# pcie-host.net
KiCad netlist of a schematic drawn in EAGLE
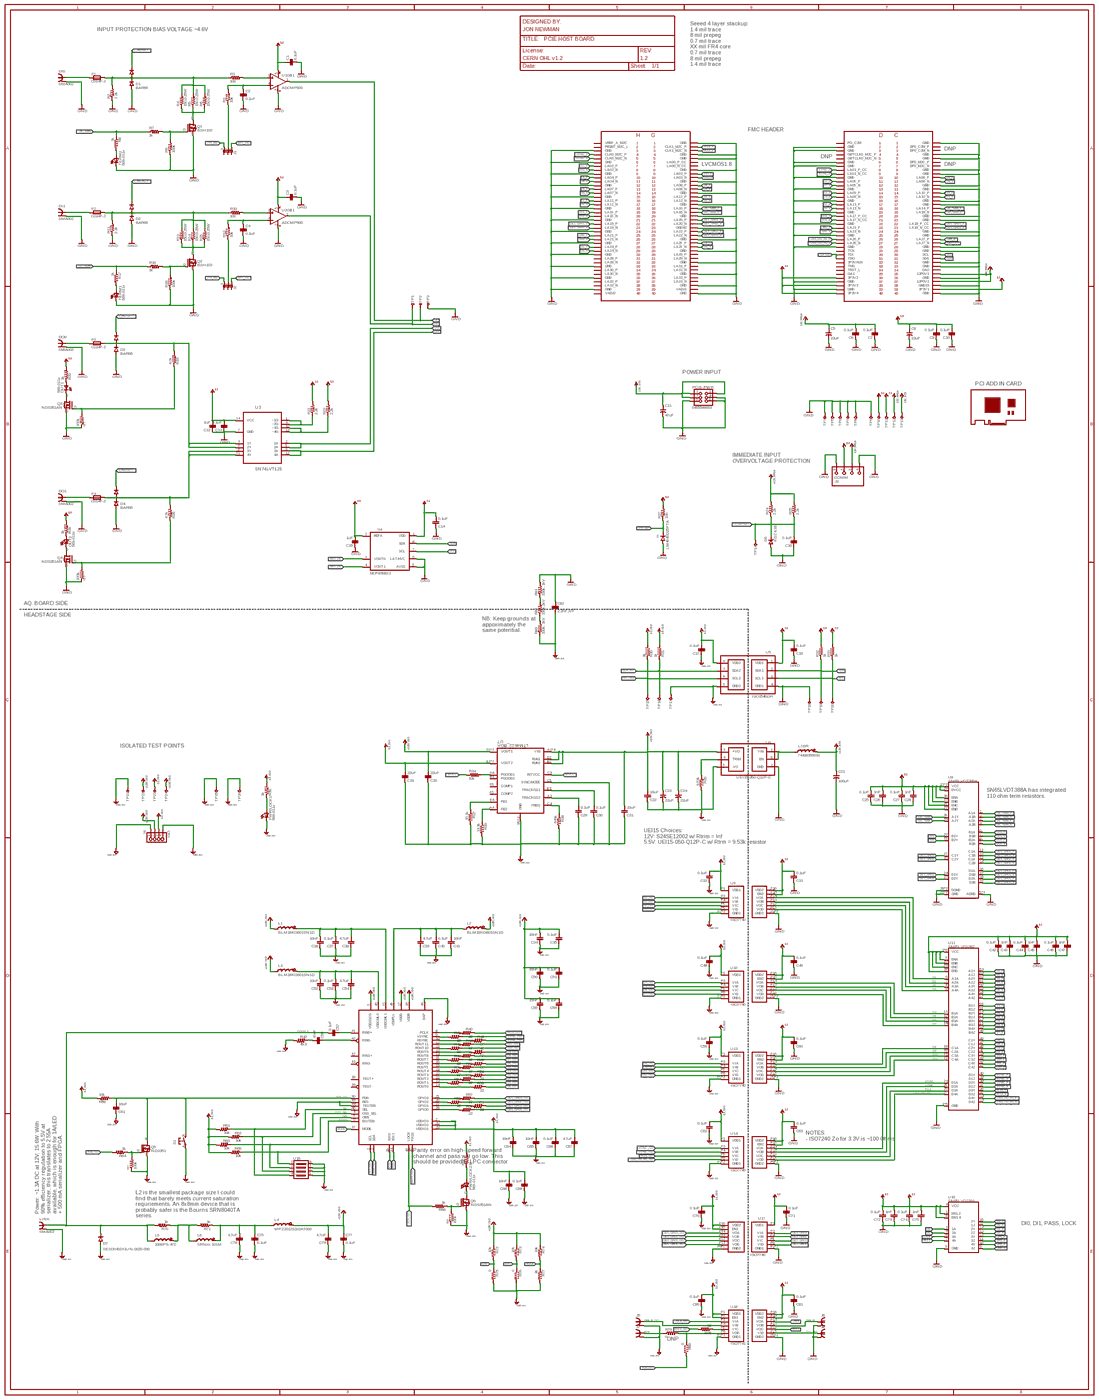
[diagram p0: schematic, sheet 1, overview]
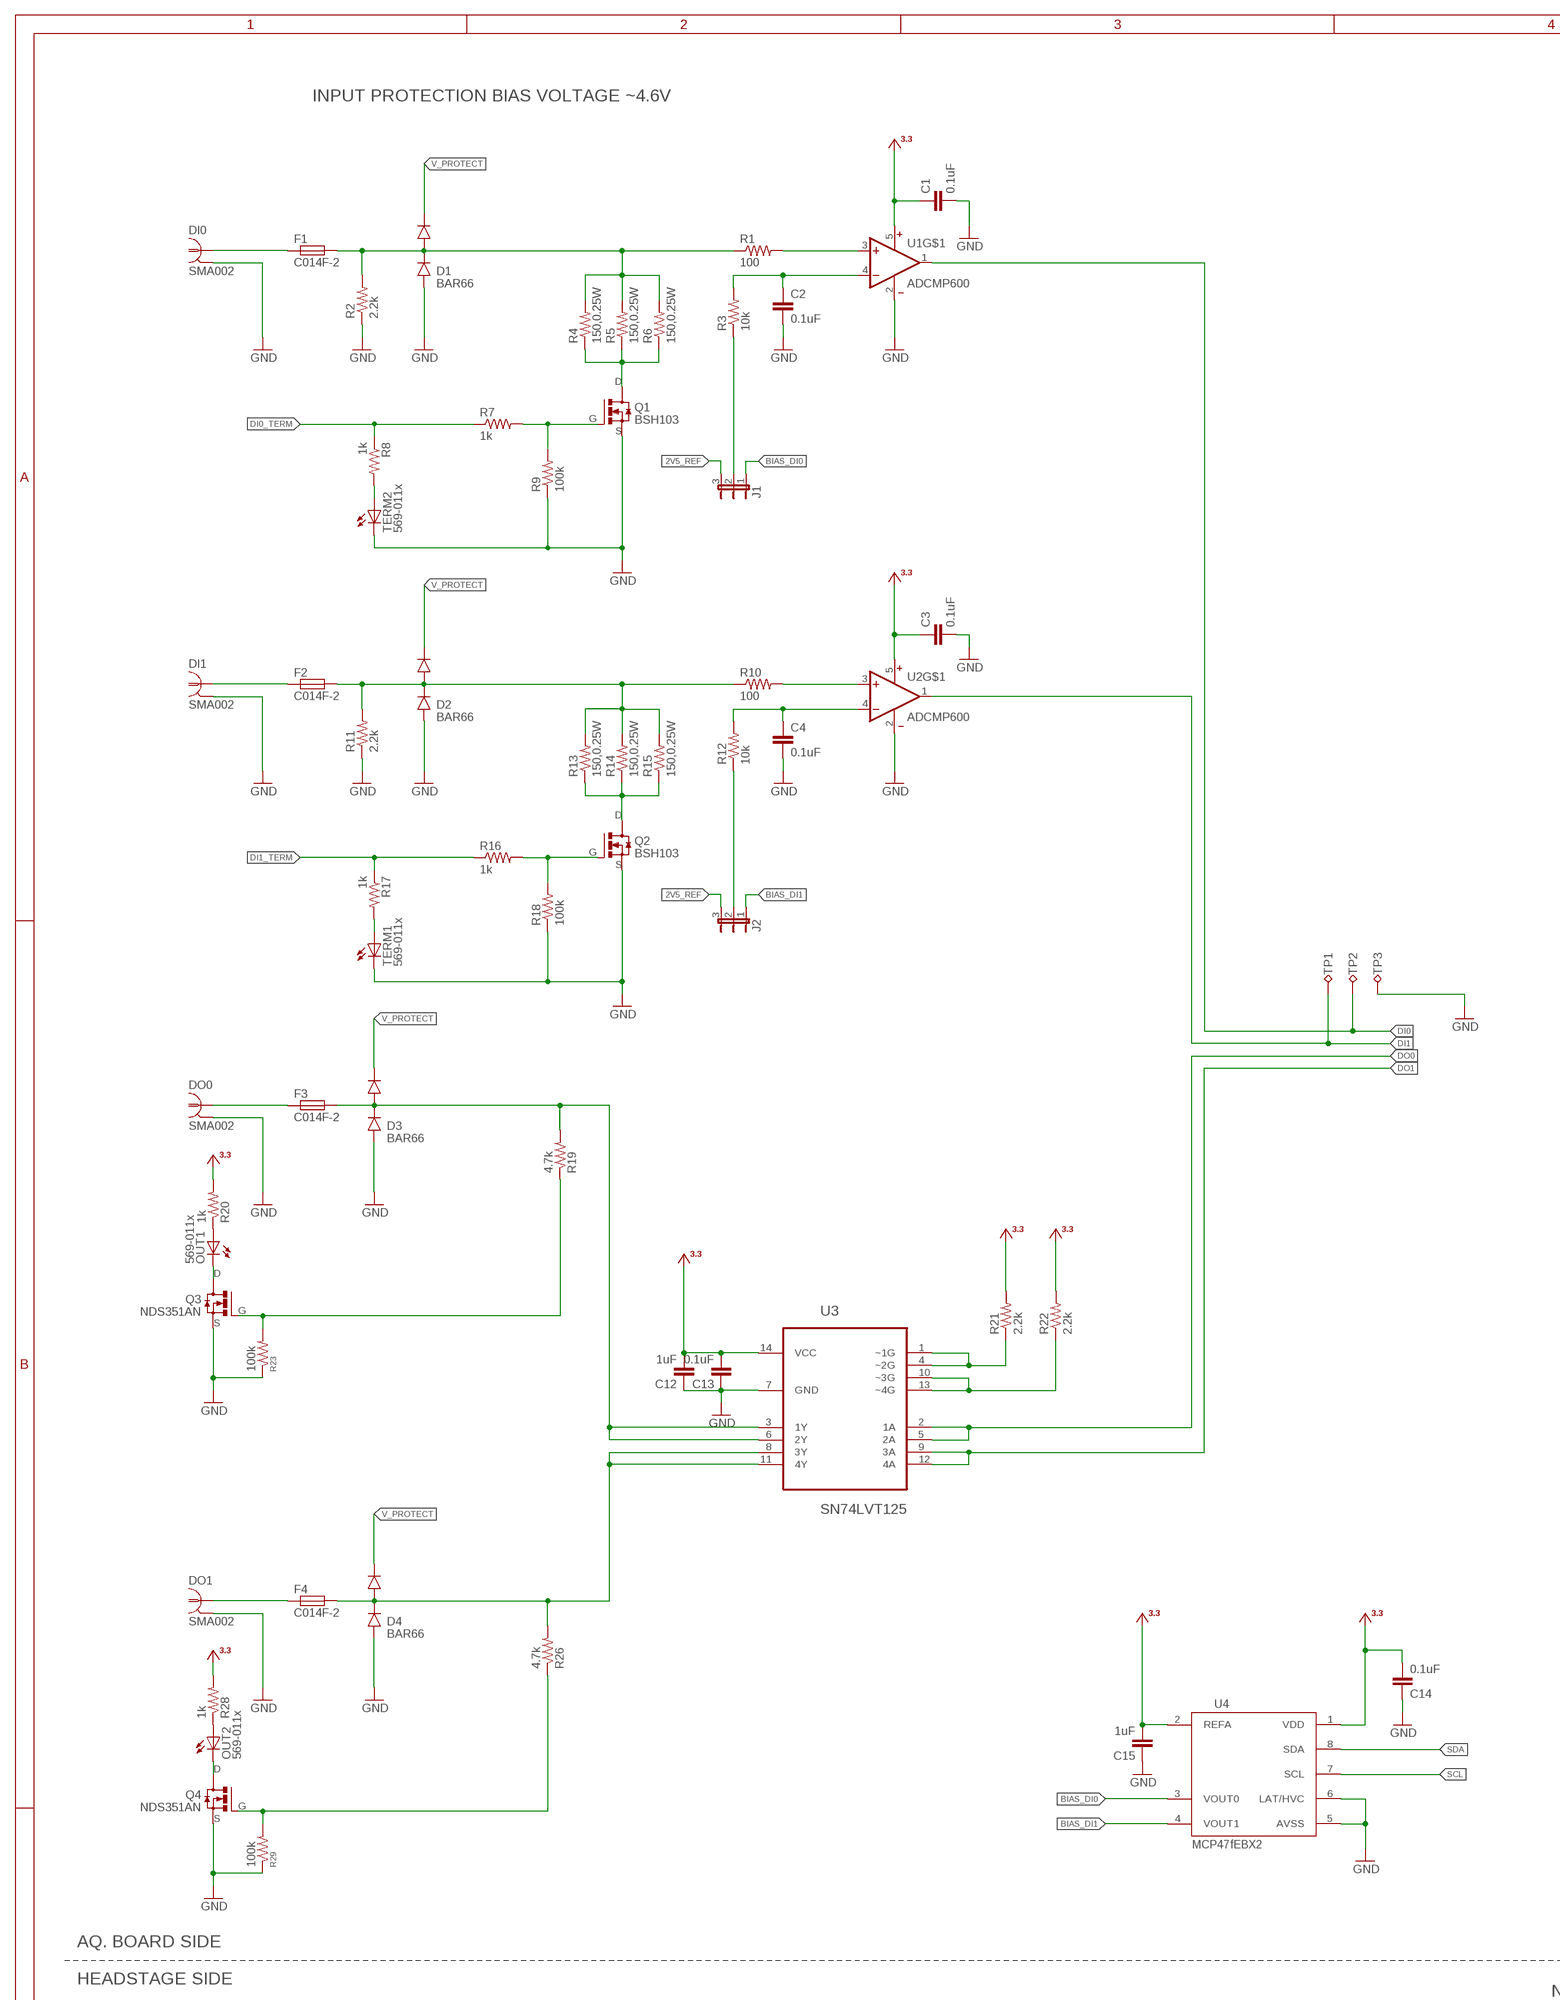
[diagram p1: schematic, sheet 1, part 1 of 4]
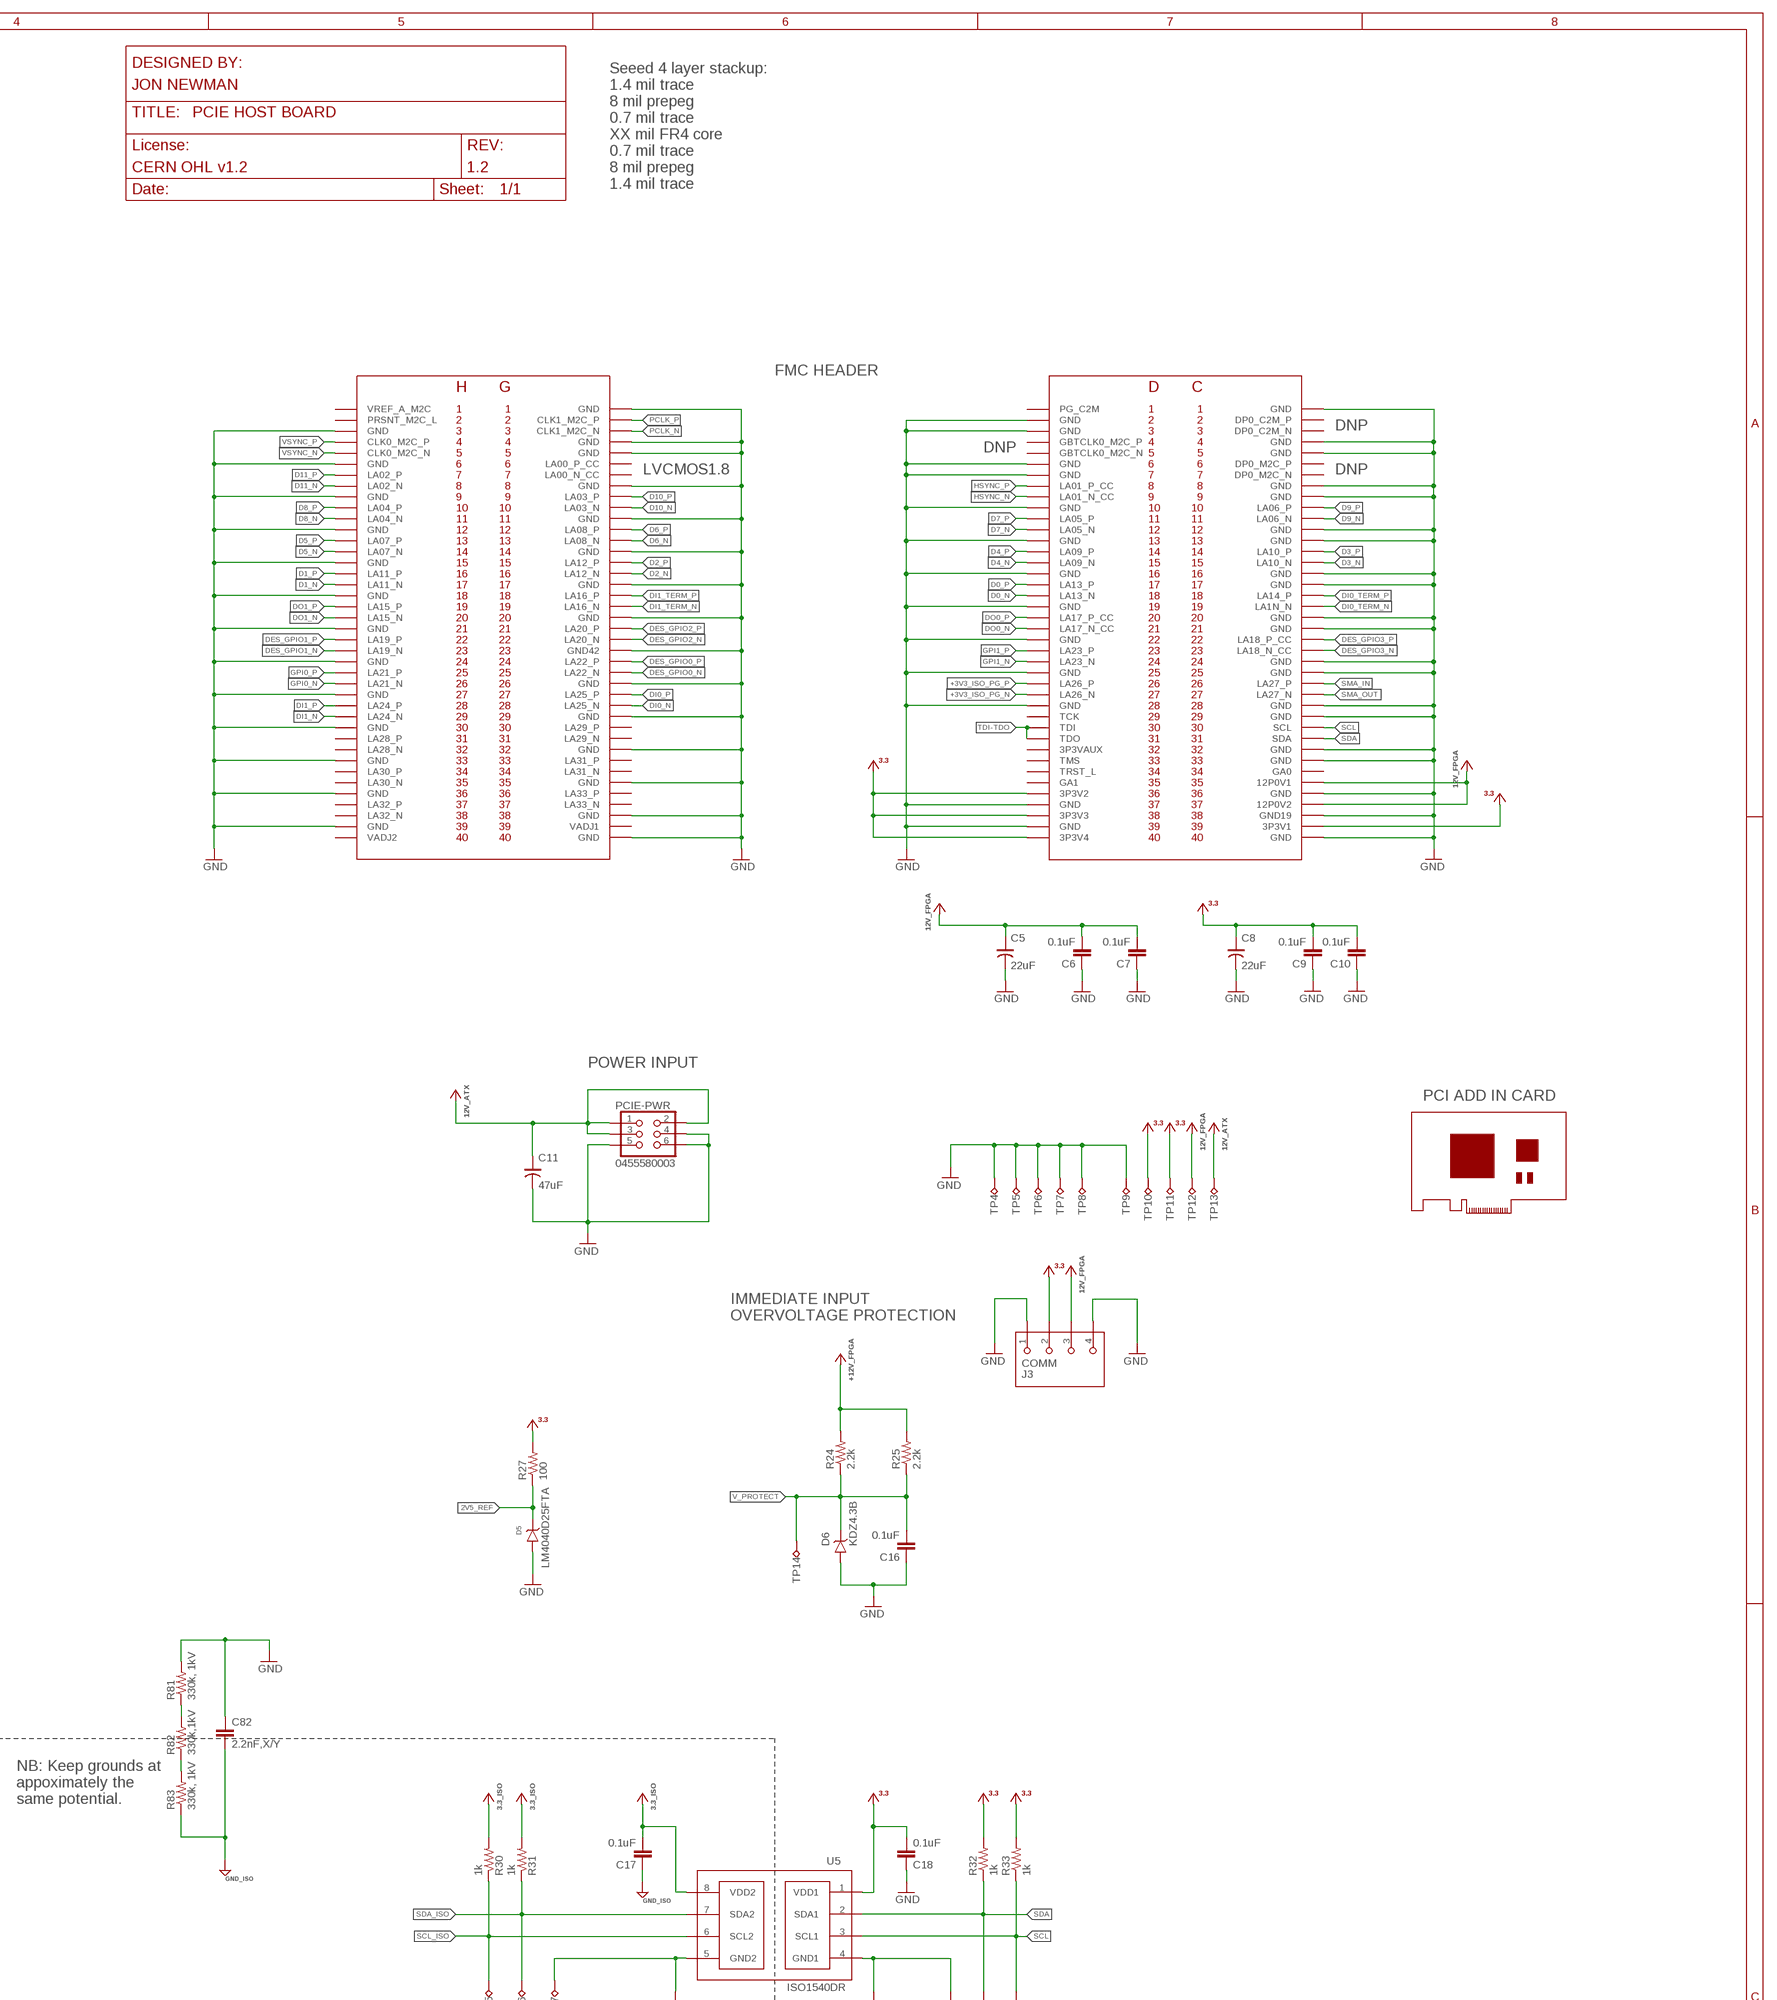
[diagram p2: schematic, sheet 1, part 2 of 4]
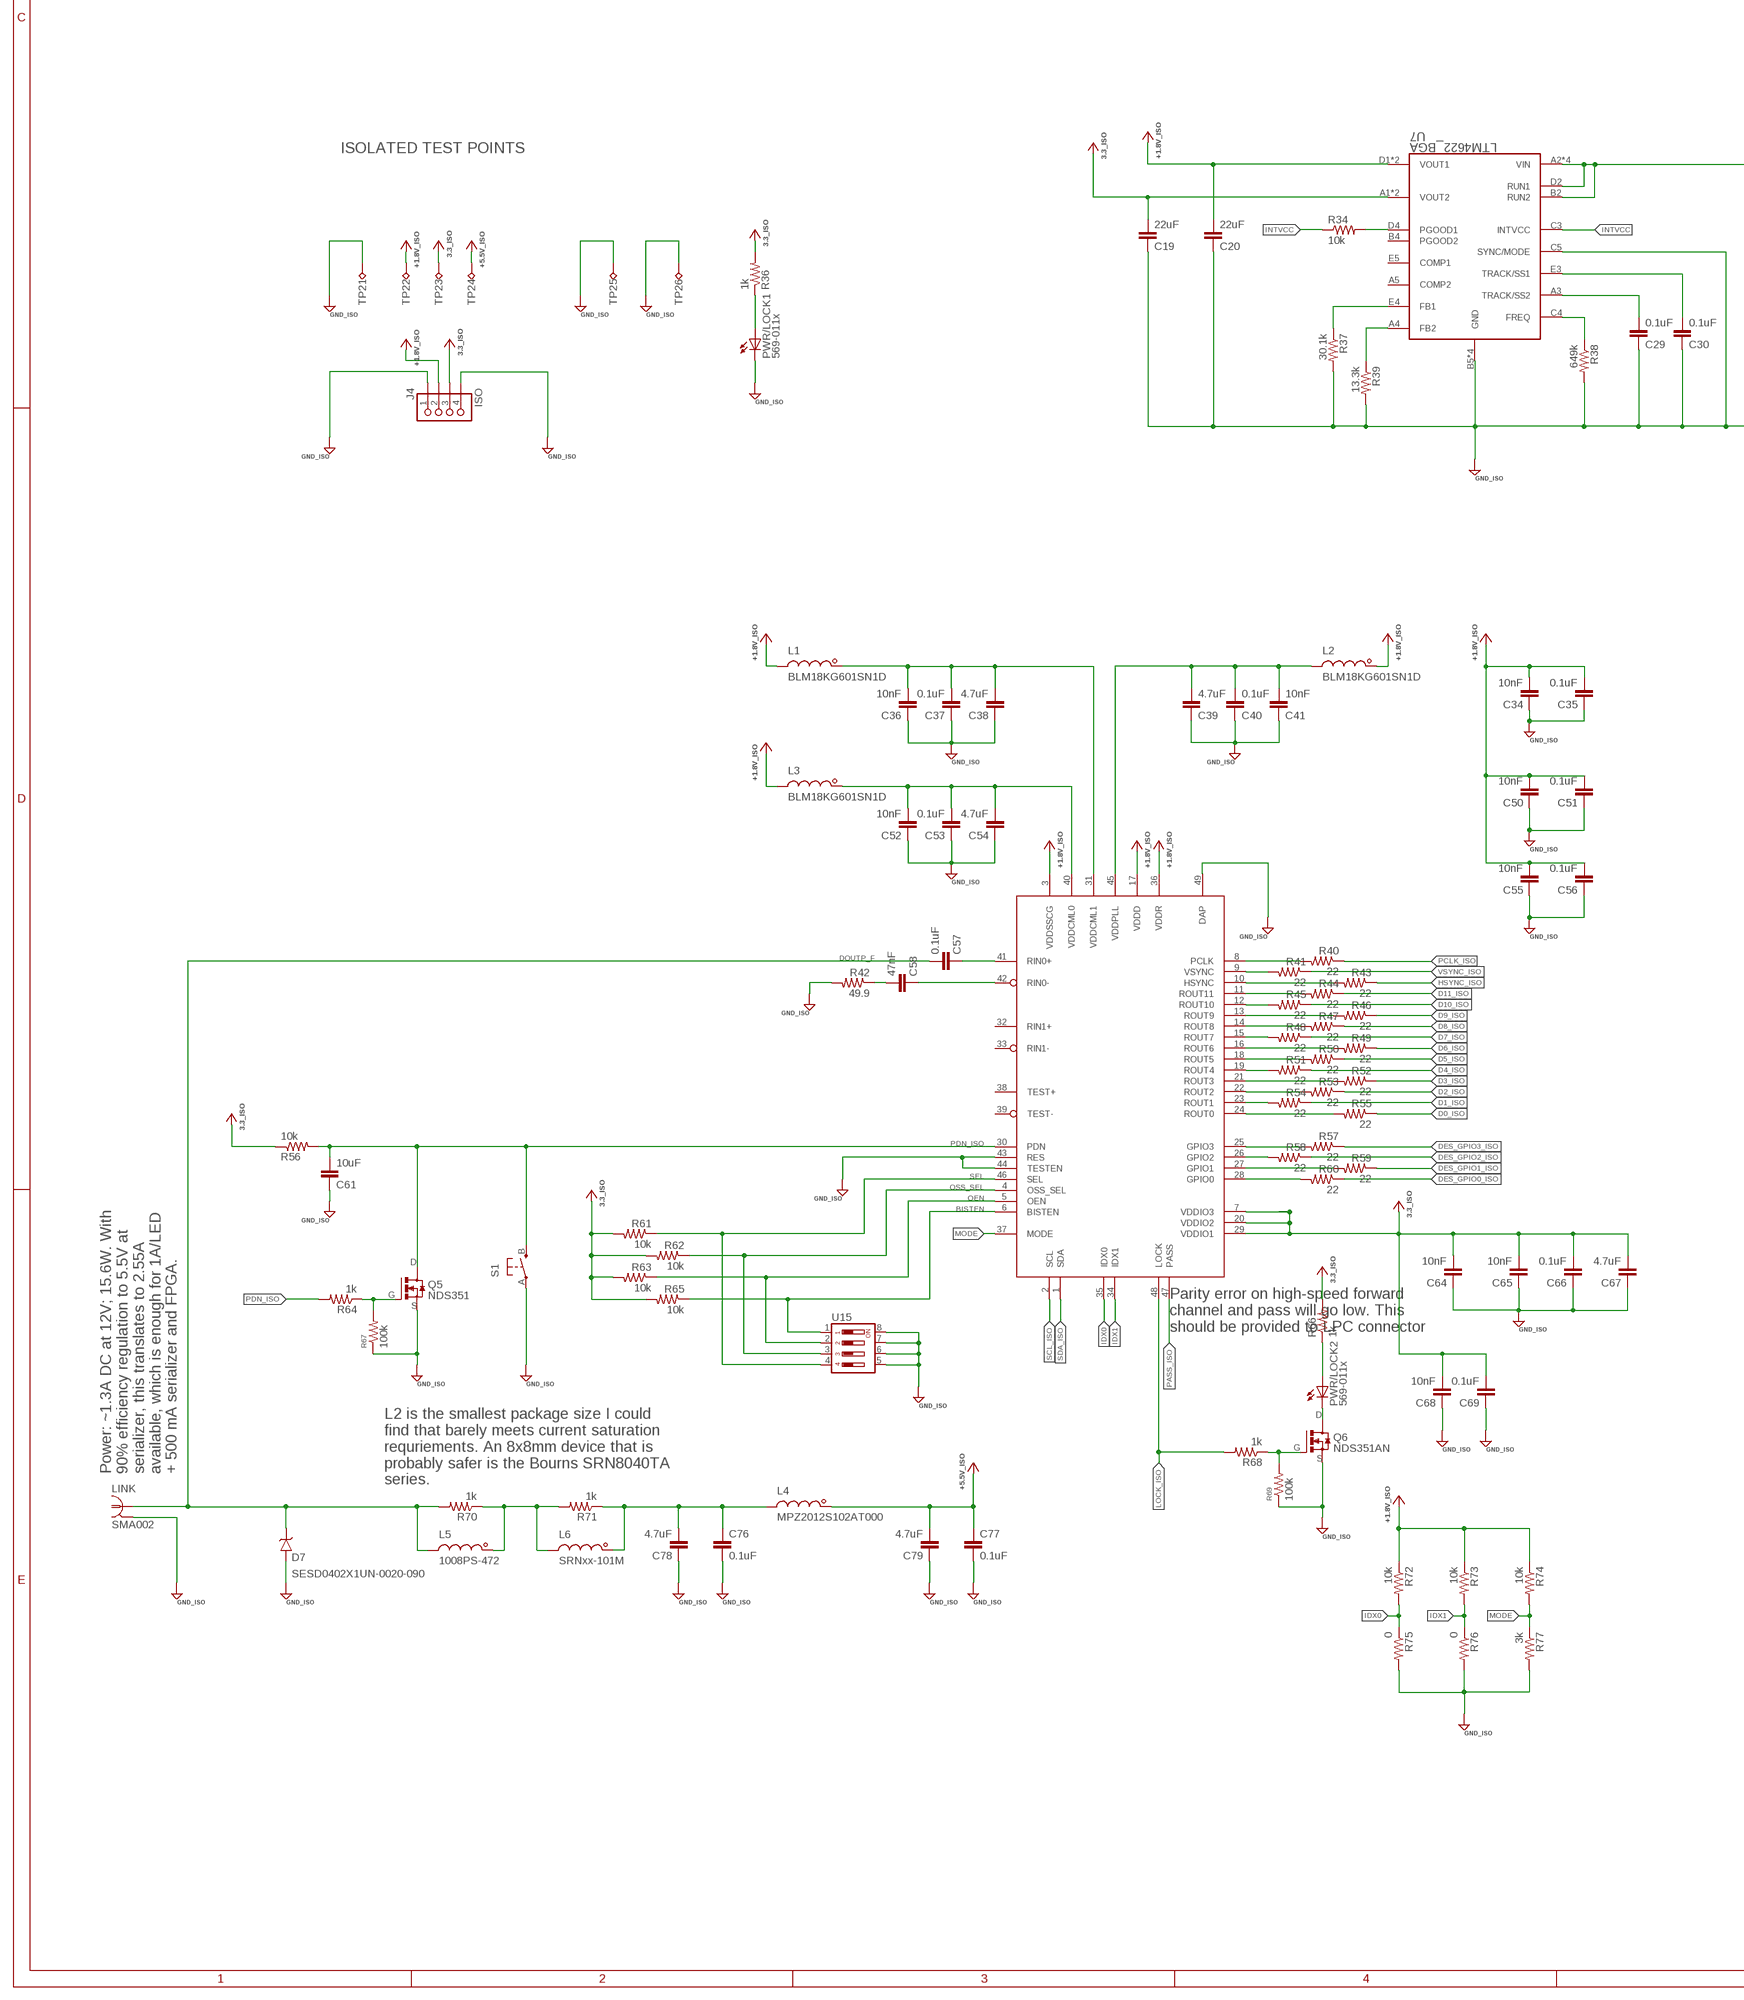
[diagram p3: schematic, sheet 1, part 3 of 4]
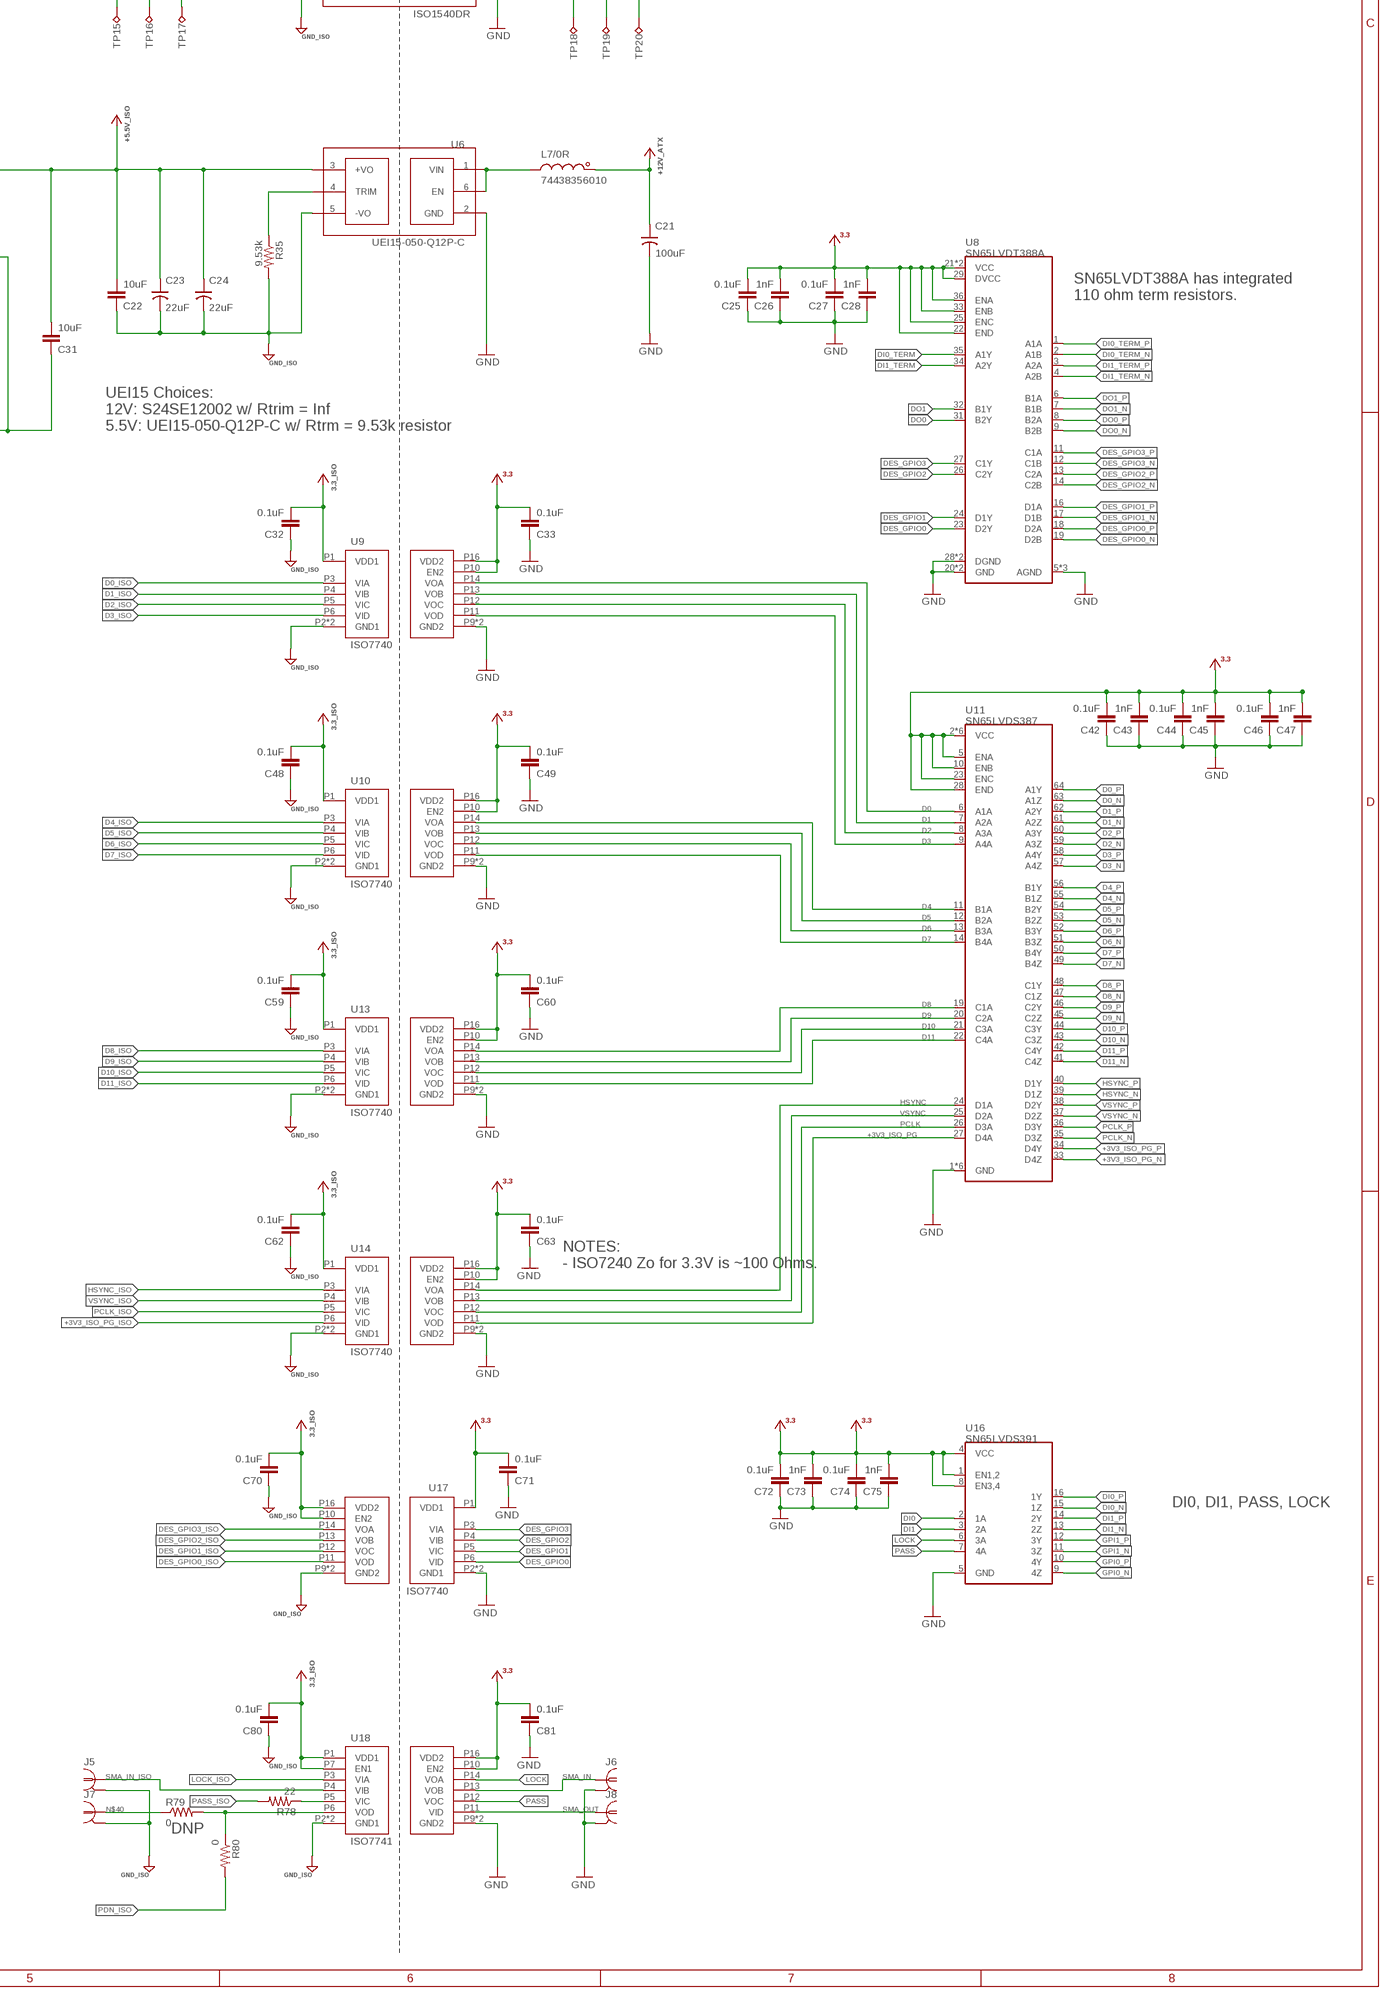
[diagram p4: schematic, sheet 1, part 4 of 4]

(export (version "E")
  (design (tool "Eeschema 10.0.6"))
  (components
    (comp (ref "C1")
      (value "0.1uF")
      (footprint "eagle-import:0603")
      (libsource (lib "eagle-import") (part "jonnew_C_0603"))
    )
    (comp (ref "C2")
      (value "0.1uF")
      (footprint "eagle-import:0603")
      (libsource (lib "eagle-import") (part "jonnew_C_0603"))
    )
    (comp (ref "C3")
      (value "0.1uF")
      (footprint "eagle-import:0603")
      (libsource (lib "eagle-import") (part "jonnew_C_0603"))
    )
    (comp (ref "C4")
      (value "0.1uF")
      (footprint "eagle-import:0603")
      (libsource (lib "eagle-import") (part "jonnew_C_0603"))
    )
    (comp (ref "C5")
      (value "22uF")
      (footprint "eagle-import:1210-POL")
      (libsource (lib "eagle-import") (part "C-POL_1210"))
    )
    (comp (ref "C6")
      (value "0.1uF")
      (footprint "eagle-import:0603")
      (libsource (lib "eagle-import") (part "jonnew_C_0603"))
    )
    (comp (ref "C7")
      (value "0.1uF")
      (footprint "eagle-import:0603")
      (libsource (lib "eagle-import") (part "jonnew_C_0603"))
    )
    (comp (ref "C8")
      (value "22uF")
      (footprint "eagle-import:1210-POL")
      (libsource (lib "eagle-import") (part "C-POL_1210"))
    )
    (comp (ref "C9")
      (value "0.1uF")
      (footprint "eagle-import:0603")
      (libsource (lib "eagle-import") (part "jonnew_C_0603"))
    )
    (comp (ref "C10")
      (value "0.1uF")
      (footprint "eagle-import:0603")
      (libsource (lib "eagle-import") (part "jonnew_C_0603"))
    )
    (comp (ref "C11")
      (value "47uF")
      (footprint "eagle-import:153CLV-0807")
      (libsource (lib "eagle-import") (part "C-POL_0807"))
    )
    (comp (ref "C12")
      (value "1uF")
      (footprint "eagle-import:0805")
      (fields (field (name "PARTNO") "C2012X5R1Cxxxxxxx"))
      (libsource (lib "eagle-import") (part "jonnew_C_0805"))
    )
    (comp (ref "C13")
      (value "0.1uF")
      (footprint "eagle-import:0603")
      (libsource (lib "eagle-import") (part "C_0603"))
    )
    (comp (ref "C14")
      (value "0.1uF")
      (footprint "eagle-import:0603")
      (libsource (lib "eagle-import") (part "C_0603"))
    )
    (comp (ref "C15")
      (value "1uF")
      (footprint "eagle-import:0805")
      (fields (field (name "PARTNO") "C2012X5R1Cxxxxxxx"))
      (libsource (lib "eagle-import") (part "jonnew_C_0805"))
    )
    (comp (ref "C16")
      (value "0.1uF")
      (footprint "eagle-import:0603")
      (libsource (lib "eagle-import") (part "jonnew_C_0603"))
    )
    (comp (ref "C17")
      (value "0.1uF")
      (footprint "eagle-import:0603")
      (libsource (lib "eagle-import") (part "jonnew_C_0603"))
    )
    (comp (ref "C18")
      (value "0.1uF")
      (footprint "eagle-import:0603")
      (libsource (lib "eagle-import") (part "jonnew_C_0603"))
    )
    (comp (ref "C19")
      (value "22uF")
      (footprint "eagle-import:1206")
      (libsource (lib "eagle-import") (part "jonnew_C_1206"))
    )
    (comp (ref "C20")
      (value "22uF")
      (footprint "eagle-import:1206")
      (libsource (lib "eagle-import") (part "jonnew_C_1206"))
    )
    (comp (ref "C21")
      (value "100uF")
      (footprint "eagle-import:153CLV-0807")
      (libsource (lib "eagle-import") (part "C-POL_0807"))
    )
    (comp (ref "C22")
      (value "10uF")
      (footprint "eagle-import:1206")
      (libsource (lib "eagle-import") (part "jonnew_C_1206"))
    )
    (comp (ref "C23")
      (value "22uF")
      (footprint "eagle-import:1210-POL")
      (libsource (lib "eagle-import") (part "C-POL_1210"))
    )
    (comp (ref "C24")
      (value "22uF")
      (footprint "eagle-import:1210-POL")
      (libsource (lib "eagle-import") (part "C-POL_1210"))
    )
    (comp (ref "C25")
      (value "0.1uF")
      (footprint "eagle-import:0603")
      (libsource (lib "eagle-import") (part "jonnew_C_0603"))
    )
    (comp (ref "C26")
      (value "1nF")
      (footprint "eagle-import:0402")
      (libsource (lib "eagle-import") (part "jonnew_C_0402"))
    )
    (comp (ref "C27")
      (value "0.1uF")
      (footprint "eagle-import:0603")
      (libsource (lib "eagle-import") (part "jonnew_C_0603"))
    )
    (comp (ref "C28")
      (value "1nF")
      (footprint "eagle-import:0402")
      (libsource (lib "eagle-import") (part "jonnew_C_0402"))
    )
    (comp (ref "C29")
      (value "0.1uF")
      (footprint "eagle-import:0603")
      (libsource (lib "eagle-import") (part "jonnew_C_0603"))
    )
    (comp (ref "C30")
      (value "0.1uF")
      (footprint "eagle-import:0603")
      (libsource (lib "eagle-import") (part "jonnew_C_0603"))
    )
    (comp (ref "C31")
      (value "10uF")
      (footprint "eagle-import:1206")
      (libsource (lib "eagle-import") (part "jonnew_C_1206"))
    )
    (comp (ref "C32")
      (value "0.1uF")
      (footprint "eagle-import:0603")
      (libsource (lib "eagle-import") (part "jonnew_C_0603"))
    )
    (comp (ref "C33")
      (value "0.1uF")
      (footprint "eagle-import:0603")
      (libsource (lib "eagle-import") (part "jonnew_C_0603"))
    )
    (comp (ref "C34")
      (value "10nF")
      (footprint "eagle-import:0402")
      (libsource (lib "eagle-import") (part "jonnew_C_0402"))
    )
    (comp (ref "C35")
      (value "0.1uF")
      (footprint "eagle-import:0402")
      (libsource (lib "eagle-import") (part "jonnew_C_0402"))
    )
    (comp (ref "C36")
      (value "10nF")
      (footprint "eagle-import:0402")
      (libsource (lib "eagle-import") (part "jonnew_C_0402"))
    )
    (comp (ref "C37")
      (value "0.1uF")
      (footprint "eagle-import:0402")
      (libsource (lib "eagle-import") (part "jonnew_C_0402"))
    )
    (comp (ref "C38")
      (value "4.7uF")
      (footprint "eagle-import:1206")
      (libsource (lib "eagle-import") (part "jonnew_C_1206"))
    )
    (comp (ref "C39")
      (value "4.7uF")
      (footprint "eagle-import:1206")
      (libsource (lib "eagle-import") (part "jonnew_C_1206"))
    )
    (comp (ref "C40")
      (value "0.1uF")
      (footprint "eagle-import:0402")
      (libsource (lib "eagle-import") (part "jonnew_C_0402"))
    )
    (comp (ref "C41")
      (value "10nF")
      (footprint "eagle-import:0402")
      (libsource (lib "eagle-import") (part "jonnew_C_0402"))
    )
    (comp (ref "C42")
      (value "0.1uF")
      (footprint "eagle-import:0603")
      (libsource (lib "eagle-import") (part "jonnew_C_0603"))
    )
    (comp (ref "C43")
      (value "1nF")
      (footprint "eagle-import:0402")
      (libsource (lib "eagle-import") (part "jonnew_C_0402"))
    )
    (comp (ref "C44")
      (value "0.1uF")
      (footprint "eagle-import:0603")
      (libsource (lib "eagle-import") (part "jonnew_C_0603"))
    )
    (comp (ref "C45")
      (value "1nF")
      (footprint "eagle-import:0402")
      (libsource (lib "eagle-import") (part "jonnew_C_0402"))
    )
    (comp (ref "C46")
      (value "0.1uF")
      (footprint "eagle-import:0603")
      (libsource (lib "eagle-import") (part "jonnew_C_0603"))
    )
    (comp (ref "C47")
      (value "1nF")
      (footprint "eagle-import:0402")
      (libsource (lib "eagle-import") (part "jonnew_C_0402"))
    )
    (comp (ref "C48")
      (value "0.1uF")
      (footprint "eagle-import:0603")
      (libsource (lib "eagle-import") (part "jonnew_C_0603"))
    )
    (comp (ref "C49")
      (value "0.1uF")
      (footprint "eagle-import:0603")
      (libsource (lib "eagle-import") (part "jonnew_C_0603"))
    )
    (comp (ref "C50")
      (value "10nF")
      (footprint "eagle-import:0402")
      (libsource (lib "eagle-import") (part "jonnew_C_0402"))
    )
    (comp (ref "C51")
      (value "0.1uF")
      (footprint "eagle-import:0402")
      (libsource (lib "eagle-import") (part "jonnew_C_0402"))
    )
    (comp (ref "C52")
      (value "10nF")
      (footprint "eagle-import:0402")
      (libsource (lib "eagle-import") (part "jonnew_C_0402"))
    )
    (comp (ref "C53")
      (value "0.1uF")
      (footprint "eagle-import:0402")
      (libsource (lib "eagle-import") (part "jonnew_C_0402"))
    )
    (comp (ref "C54")
      (value "4.7uF")
      (footprint "eagle-import:1206")
      (libsource (lib "eagle-import") (part "jonnew_C_1206"))
    )
    (comp (ref "C55")
      (value "10nF")
      (footprint "eagle-import:0402")
      (libsource (lib "eagle-import") (part "jonnew_C_0402"))
    )
    (comp (ref "C56")
      (value "0.1uF")
      (footprint "eagle-import:0402")
      (libsource (lib "eagle-import") (part "jonnew_C_0402"))
    )
    (comp (ref "C57")
      (value "0.1uF")
      (footprint "eagle-import:0402")
      (libsource (lib "eagle-import") (part "jonnew_C_0402"))
    )
    (comp (ref "C58")
      (value "47nF")
      (footprint "eagle-import:0402")
      (libsource (lib "eagle-import") (part "jonnew_C_0402"))
    )
    (comp (ref "C59")
      (value "0.1uF")
      (footprint "eagle-import:0603")
      (libsource (lib "eagle-import") (part "jonnew_C_0603"))
    )
    (comp (ref "C60")
      (value "0.1uF")
      (footprint "eagle-import:0603")
      (libsource (lib "eagle-import") (part "jonnew_C_0603"))
    )
    (comp (ref "C61")
      (value "10uF")
      (footprint "eagle-import:1206")
      (libsource (lib "eagle-import") (part "jonnew_C_1206"))
    )
    (comp (ref "C62")
      (value "0.1uF")
      (footprint "eagle-import:0603")
      (libsource (lib "eagle-import") (part "jonnew_C_0603"))
    )
    (comp (ref "C63")
      (value "0.1uF")
      (footprint "eagle-import:0603")
      (libsource (lib "eagle-import") (part "jonnew_C_0603"))
    )
    (comp (ref "C64")
      (value "10nF")
      (footprint "eagle-import:0402")
      (libsource (lib "eagle-import") (part "jonnew_C_0402"))
    )
    (comp (ref "C65")
      (value "10nF")
      (footprint "eagle-import:0402")
      (libsource (lib "eagle-import") (part "jonnew_C_0402"))
    )
    (comp (ref "C66")
      (value "0.1uF")
      (footprint "eagle-import:0402")
      (libsource (lib "eagle-import") (part "jonnew_C_0402"))
    )
    (comp (ref "C67")
      (value "4.7uF")
      (footprint "eagle-import:1206")
      (libsource (lib "eagle-import") (part "jonnew_C_1206"))
    )
    (comp (ref "C68")
      (value "10nF")
      (footprint "eagle-import:0402")
      (libsource (lib "eagle-import") (part "jonnew_C_0402"))
    )
    (comp (ref "C69")
      (value "0.1uF")
      (footprint "eagle-import:0402")
      (libsource (lib "eagle-import") (part "jonnew_C_0402"))
    )
    (comp (ref "C70")
      (value "0.1uF")
      (footprint "eagle-import:0603")
      (libsource (lib "eagle-import") (part "jonnew_C_0603"))
    )
    (comp (ref "C71")
      (value "0.1uF")
      (footprint "eagle-import:0603")
      (libsource (lib "eagle-import") (part "jonnew_C_0603"))
    )
    (comp (ref "C72")
      (value "0.1uF")
      (footprint "eagle-import:0603")
      (libsource (lib "eagle-import") (part "jonnew_C_0603"))
    )
    (comp (ref "C73")
      (value "1nF")
      (footprint "eagle-import:0402")
      (libsource (lib "eagle-import") (part "jonnew_C_0402"))
    )
    (comp (ref "C74")
      (value "0.1uF")
      (footprint "eagle-import:0603")
      (libsource (lib "eagle-import") (part "jonnew_C_0603"))
    )
    (comp (ref "C75")
      (value "1nF")
      (footprint "eagle-import:0402")
      (libsource (lib "eagle-import") (part "jonnew_C_0402"))
    )
    (comp (ref "C76")
      (value "0.1uF")
      (footprint "eagle-import:0603")
      (libsource (lib "eagle-import") (part "jonnew_C_0603"))
    )
    (comp (ref "C77")
      (value "0.1uF")
      (footprint "eagle-import:0603")
      (libsource (lib "eagle-import") (part "jonnew_C_0603"))
    )
    (comp (ref "C78")
      (value "4.7uF")
      (footprint "eagle-import:1206")
      (libsource (lib "eagle-import") (part "jonnew_C_1206"))
    )
    (comp (ref "C79")
      (value "4.7uF")
      (footprint "eagle-import:1206")
      (libsource (lib "eagle-import") (part "jonnew_C_1206"))
    )
    (comp (ref "C80")
      (value "0.1uF")
      (footprint "eagle-import:0603")
      (libsource (lib "eagle-import") (part "jonnew_C_0603"))
    )
    (comp (ref "C81")
      (value "0.1uF")
      (footprint "eagle-import:0603")
      (libsource (lib "eagle-import") (part "jonnew_C_0603"))
    )
    (comp (ref "C82")
      (value "2.2nF,X/Y")
      (footprint "eagle-import:C900")
      (libsource (lib "eagle-import") (part "C_C900"))
    )
    (comp (ref "D1")
      (value "BAR66")
      (footprint "eagle-import:SOT23")
      (libsource (lib "eagle-import") (part "DIODE2_SOT23"))
    )
    (comp (ref "D2")
      (value "BAR66")
      (footprint "eagle-import:SOT23")
      (libsource (lib "eagle-import") (part "DIODE2_SOT23"))
    )
    (comp (ref "D3")
      (value "BAR66")
      (footprint "eagle-import:SOT23")
      (libsource (lib "eagle-import") (part "DIODE2_SOT23"))
    )
    (comp (ref "D4")
      (value "BAR66")
      (footprint "eagle-import:SOT23")
      (libsource (lib "eagle-import") (part "DIODE2_SOT23"))
    )
    (comp (ref "D5")
      (value "LM4040D25FTA")
      (footprint "eagle-import:SOT23")
      (libsource (lib "eagle-import") (part "Z-DIODE_SOT23"))
    )
    (comp (ref "D6")
      (value "KDZ4.3B")
      (footprint "eagle-import:SOD123")
      (libsource (lib "eagle-import") (part "Z-DIODE_SOD123"))
    )
    (comp (ref "D7")
      (value "SESD0402X1UN-0020-090")
      (footprint "eagle-import:0402P-DFN")
      (libsource (lib "eagle-import") (part "Z-DIODE_0402P-DFN"))
    )
    (comp (ref "DI0")
      (value "SMA002")
      (footprint "eagle-import:SMA_JACK_CONREVSMA002-G")
      (libsource (lib "eagle-import") (part "COAX_CONREVSMA002-G"))
    )
    (comp (ref "DI1")
      (value "SMA002")
      (footprint "eagle-import:SMA_JACK_CONREVSMA002-G")
      (libsource (lib "eagle-import") (part "COAX_CONREVSMA002-G"))
    )
    (comp (ref "DO0")
      (value "SMA002")
      (footprint "eagle-import:SMA_JACK_CONREVSMA002-G")
      (libsource (lib "eagle-import") (part "COAX_CONREVSMA002-G"))
    )
    (comp (ref "DO1")
      (value "SMA002")
      (footprint "eagle-import:SMA_JACK_CONREVSMA002-G")
      (libsource (lib "eagle-import") (part "COAX_CONREVSMA002-G"))
    )
    (comp (ref "F1")
      (value "C014F-2")
      (footprint "eagle-import:1812")
      (libsource (lib "eagle-import") (part "FUSE_1812"))
    )
    (comp (ref "F2")
      (value "C014F-2")
      (footprint "eagle-import:1812")
      (libsource (lib "eagle-import") (part "FUSE_1812"))
    )
    (comp (ref "F3")
      (value "C014F-2")
      (footprint "eagle-import:1812")
      (libsource (lib "eagle-import") (part "FUSE_1812"))
    )
    (comp (ref "F4")
      (value "C014F-2")
      (footprint "eagle-import:1812")
      (libsource (lib "eagle-import") (part "FUSE_1812"))
    )
    (comp (ref "FMC_LPC")
      (value "FMC_LPC_160_PIN")
      (footprint "eagle-import:FMC_LPC_MALE_WITH_SP601_BSILK")
      (libsource (lib "eagle-import") (part "FMC_LPC_160_PIN"))
    )
    (comp (ref "J1")
      (value "JP3E")
      (footprint "eagle-import:JP3")
      (libsource (lib "eagle-import") (part "JP3E"))
    )
    (comp (ref "J2")
      (value "JP3E")
      (footprint "eagle-import:JP3")
      (libsource (lib "eagle-import") (part "JP3E"))
    )
    (comp (ref "J3")
      (value "COMM")
      (footprint "eagle-import:SCREW4")
      (libsource (lib "eagle-import") (part "SCREW4"))
    )
    (comp (ref "J4")
      (value "ISO")
      (footprint "eagle-import:1X04")
      (libsource (lib "eagle-import") (part "PINHD-1X4"))
    )
    (comp (ref "J5")
      (value "COAX_SMA-VERT-SMA")
      (footprint "eagle-import:SMA_VERT")
      (libsource (lib "eagle-import") (part "COAX_SMA-VERT-SMA"))
    )
    (comp (ref "J6")
      (value "COAX_SMA-VERT-SMA")
      (footprint "eagle-import:SMA_VERT")
      (libsource (lib "eagle-import") (part "COAX_SMA-VERT-SMA"))
    )
    (comp (ref "J7")
      (value "COAX_SMA-VERT-SMA")
      (footprint "eagle-import:SMA_VERT")
      (libsource (lib "eagle-import") (part "COAX_SMA-VERT-SMA"))
    )
    (comp (ref "J8")
      (value "COAX_SMA-VERT-SMA")
      (footprint "eagle-import:SMA_VERT")
      (libsource (lib "eagle-import") (part "COAX_SMA-VERT-SMA"))
    )
    (comp (ref "L1")
      (value "BLM18KG601SN1D")
      (footprint "eagle-import:0603")
      (libsource (lib "eagle-import") (part "L_0603"))
    )
    (comp (ref "L2")
      (value "BLM18KG601SN1D")
      (footprint "eagle-import:0603")
      (libsource (lib "eagle-import") (part "L_0603"))
    )
    (comp (ref "L3")
      (value "BLM18KG601SN1D")
      (footprint "eagle-import:0603")
      (libsource (lib "eagle-import") (part "L_0603"))
    )
    (comp (ref "L4")
      (value "MPZ2012S102AT000")
      (footprint "eagle-import:0805")
      (libsource (lib "eagle-import") (part "L_0805"))
    )
    (comp (ref "L5")
      (value "1008PS-472")
      (footprint "eagle-import:1008PS")
      (libsource (lib "eagle-import") (part "L_1008PS"))
    )
    (comp (ref "L6")
      (value "SRNxx-101M")
      (footprint "eagle-import:SRN6045TA")
      (libsource (lib "eagle-import") (part "L_SRN6045TA"))
    )
    (comp (ref "L7/0R")
      (value "74438356010")
      (footprint "eagle-import:4020")
      (libsource (lib "eagle-import") (part "L_4020"))
    )
    (comp (ref "LINK")
      (value "SMA002")
      (footprint "eagle-import:SMA_JACK_CONREVSMA002-G")
      (libsource (lib "eagle-import") (part "COAX_CONREVSMA002-G"))
    )
    (comp (ref "OUT")
      (value "569-011x")
      (footprint "eagle-import:569-011X-X00_LED_ARRAY")
      (libsource (lib "eagle-import") (part "LED_2X_VERTICAL"))
    )
    (comp (ref "PCIE-PWR")
      (value "0455580003")
      (footprint "eagle-import:PCIE-POWER-6PIN")
      (libsource (lib "eagle-import") (part "PINHD-2X3_PCIE-PWR"))
    )
    (comp (ref "PWR/LOCK")
      (value "569-011x")
      (footprint "eagle-import:569-011X-X00_LED_ARRAY")
      (libsource (lib "eagle-import") (part "LED_2X_VERTICAL"))
    )
    (comp (ref "Q1")
      (value "BSH103")
      (footprint "eagle-import:SOT23-GSD")
      (libsource (lib "eagle-import") (part "N-MOSFET_SOT23-GSD"))
    )
    (comp (ref "Q2")
      (value "BSH103")
      (footprint "eagle-import:SOT23-GSD")
      (libsource (lib "eagle-import") (part "N-MOSFET_SOT23-GSD"))
    )
    (comp (ref "Q3")
      (value "NDS351AN")
      (footprint "eagle-import:SOT23-GSD")
      (libsource (lib "eagle-import") (part "N-MOSFET_SOT23-GSD"))
    )
    (comp (ref "Q4")
      (value "NDS351AN")
      (footprint "eagle-import:SOT23-GSD")
      (libsource (lib "eagle-import") (part "N-MOSFET_SOT23-GSD"))
    )
    (comp (ref "Q5")
      (value "NDS351")
      (footprint "eagle-import:SOT23-GSD")
      (libsource (lib "eagle-import") (part "N-MOSFET_SOT23-GSD"))
    )
    (comp (ref "Q6")
      (value "NDS351AN")
      (footprint "eagle-import:SOT23-GSD")
      (libsource (lib "eagle-import") (part "N-MOSFET_SOT23-GSD"))
    )
    (comp (ref "R1")
      (value "100")
      (footprint "eagle-import:0603")
      (fields (field (name "MPN") "ERJ-3EKFxxxxV"))
      (libsource (lib "eagle-import") (part "jonnew_R_0603"))
    )
    (comp (ref "R2")
      (value "2.2k")
      (footprint "eagle-import:0603")
      (fields (field (name "MPN") "ERJ-3EKFxxxxV"))
      (libsource (lib "eagle-import") (part "jonnew_R_0603"))
    )
    (comp (ref "R3")
      (value "10k")
      (footprint "eagle-import:0603")
      (fields (field (name "MPN") "ERJ-3EKFxxxxV"))
      (libsource (lib "eagle-import") (part "jonnew_R_0603"))
    )
    (comp (ref "R4")
      (value "150,0.25W")
      (footprint "eagle-import:1206")
      (libsource (lib "eagle-import") (part "jonnew_R_1206"))
    )
    (comp (ref "R5")
      (value "150,0.25W")
      (footprint "eagle-import:1206")
      (libsource (lib "eagle-import") (part "jonnew_R_1206"))
    )
    (comp (ref "R6")
      (value "150,0.25W")
      (footprint "eagle-import:1206")
      (libsource (lib "eagle-import") (part "jonnew_R_1206"))
    )
    (comp (ref "R7")
      (value "1k")
      (footprint "eagle-import:0603")
      (fields (field (name "MPN") "ERJ-3EKFxxxxV"))
      (libsource (lib "eagle-import") (part "jonnew_R_0603"))
    )
    (comp (ref "R8")
      (value "1k")
      (footprint "eagle-import:0603")
      (fields (field (name "MPN") "ERJ-3EKFxxxxV"))
      (libsource (lib "eagle-import") (part "jonnew_R_0603"))
    )
    (comp (ref "R9")
      (value "100k")
      (footprint "eagle-import:0603")
      (fields (field (name "MPN") "ERJ-3EKFxxxxV"))
      (libsource (lib "eagle-import") (part "jonnew_R_0603"))
    )
    (comp (ref "R10")
      (value "100")
      (footprint "eagle-import:0603")
      (fields (field (name "MPN") "ERJ-3EKFxxxxV"))
      (libsource (lib "eagle-import") (part "jonnew_R_0603"))
    )
    (comp (ref "R11")
      (value "2.2k")
      (footprint "eagle-import:0603")
      (fields (field (name "MPN") "ERJ-3EKFxxxxV"))
      (libsource (lib "eagle-import") (part "jonnew_R_0603"))
    )
    (comp (ref "R12")
      (value "10k")
      (footprint "eagle-import:0603")
      (fields (field (name "MPN") "ERJ-3EKFxxxxV"))
      (libsource (lib "eagle-import") (part "jonnew_R_0603"))
    )
    (comp (ref "R13")
      (value "150,0.25W")
      (footprint "eagle-import:1206")
      (libsource (lib "eagle-import") (part "jonnew_R_1206"))
    )
    (comp (ref "R14")
      (value "150,0.25W")
      (footprint "eagle-import:1206")
      (libsource (lib "eagle-import") (part "jonnew_R_1206"))
    )
    (comp (ref "R15")
      (value "150,0.25W")
      (footprint "eagle-import:1206")
      (libsource (lib "eagle-import") (part "jonnew_R_1206"))
    )
    (comp (ref "R16")
      (value "1k")
      (footprint "eagle-import:0603")
      (fields (field (name "MPN") "ERJ-3EKFxxxxV"))
      (libsource (lib "eagle-import") (part "jonnew_R_0603"))
    )
    (comp (ref "R17")
      (value "1k")
      (footprint "eagle-import:0603")
      (libsource (lib "eagle-import") (part "R_0603"))
    )
    (comp (ref "R18")
      (value "100k")
      (footprint "eagle-import:0603")
      (fields (field (name "MPN") "ERJ-3EKFxxxxV"))
      (libsource (lib "eagle-import") (part "jonnew_R_0603"))
    )
    (comp (ref "R19")
      (value "4.7k")
      (footprint "eagle-import:0603")
      (fields (field (name "MPN") "ERJ-3EKFxxxxV"))
      (libsource (lib "eagle-import") (part "cyclops_R_0603"))
    )
    (comp (ref "R20")
      (value "1k")
      (footprint "eagle-import:0603")
      (fields (field (name "MPN") "ERJ-3EKFxxxxV"))
      (libsource (lib "eagle-import") (part "cyclops_R_0603"))
    )
    (comp (ref "R21")
      (value "2.2k")
      (footprint "eagle-import:0603")
      (fields (field (name "MPN") "ERJ-3EKFxxxxV"))
      (libsource (lib "eagle-import") (part "jonnew_R_0603"))
    )
    (comp (ref "R22")
      (value "2.2k")
      (footprint "eagle-import:0603")
      (fields (field (name "MPN") "ERJ-3EKFxxxxV"))
      (libsource (lib "eagle-import") (part "jonnew_R_0603"))
    )
    (comp (ref "R23")
      (value "100k")
      (footprint "eagle-import:0603")
      (fields (field (name "MPN") "ERJ-3EKFxxxxV"))
      (libsource (lib "eagle-import") (part "cyclops_R_0603"))
    )
    (comp (ref "R24")
      (value "2.2k")
      (footprint "eagle-import:0603")
      (fields (field (name "MPN") "ERJ-3EKFxxxxV"))
      (libsource (lib "eagle-import") (part "jonnew_R_0603"))
    )
    (comp (ref "R25")
      (value "2.2k")
      (footprint "eagle-import:0603")
      (fields (field (name "MPN") "ERJ-3EKFxxxxV"))
      (libsource (lib "eagle-import") (part "jonnew_R_0603"))
    )
    (comp (ref "R26")
      (value "4.7k")
      (footprint "eagle-import:0603")
      (fields (field (name "MPN") "ERJ-3EKFxxxxV"))
      (libsource (lib "eagle-import") (part "cyclops_R_0603"))
    )
    (comp (ref "R27")
      (value "100")
      (footprint "eagle-import:0603")
      (fields (field (name "MPN") "ERJ-3EKFxxxxV"))
      (libsource (lib "eagle-import") (part "jonnew_R_0603"))
    )
    (comp (ref "R28")
      (value "1k")
      (footprint "eagle-import:0603")
      (fields (field (name "MPN") "ERJ-3EKFxxxxV"))
      (libsource (lib "eagle-import") (part "cyclops_R_0603"))
    )
    (comp (ref "R29")
      (value "100k")
      (footprint "eagle-import:0603")
      (fields (field (name "MPN") "ERJ-3EKFxxxxV"))
      (libsource (lib "eagle-import") (part "cyclops_R_0603"))
    )
    (comp (ref "R30")
      (value "1k")
      (footprint "eagle-import:0603")
      (fields (field (name "MPN") "ERJ-3EKFxxxxV"))
      (libsource (lib "eagle-import") (part "jonnew_R_0603"))
    )
    (comp (ref "R31")
      (value "1k")
      (footprint "eagle-import:0603")
      (fields (field (name "MPN") "ERJ-3EKFxxxxV"))
      (libsource (lib "eagle-import") (part "jonnew_R_0603"))
    )
    (comp (ref "R32")
      (value "1k")
      (footprint "eagle-import:0603")
      (fields (field (name "MPN") "ERJ-3EKFxxxxV"))
      (libsource (lib "eagle-import") (part "jonnew_R_0603"))
    )
    (comp (ref "R33")
      (value "1k")
      (footprint "eagle-import:0603")
      (fields (field (name "MPN") "ERJ-3EKFxxxxV"))
      (libsource (lib "eagle-import") (part "jonnew_R_0603"))
    )
    (comp (ref "R34")
      (value "10k")
      (footprint "eagle-import:0603")
      (fields (field (name "MPN") "ERJ-3EKFxxxxV"))
      (libsource (lib "eagle-import") (part "jonnew_R_0603"))
    )
    (comp (ref "R35")
      (value "9.53k")
      (footprint "eagle-import:0603")
      (fields (field (name "MPN") "ERJ-3EKFxxxxV"))
      (libsource (lib "eagle-import") (part "jonnew_R_0603"))
    )
    (comp (ref "R36")
      (value "1k")
      (footprint "eagle-import:0603")
      (fields (field (name "MPN") "ERJ-3EKFxxxxV"))
      (libsource (lib "eagle-import") (part "cyclops_R_0603"))
    )
    (comp (ref "R37")
      (value "30.1k")
      (footprint "eagle-import:0603")
      (fields (field (name "MPN") "ERJ-3EKFxxxxV"))
      (libsource (lib "eagle-import") (part "jonnew_R_0603"))
    )
    (comp (ref "R38")
      (value "649k")
      (footprint "eagle-import:0603")
      (fields (field (name "MPN") "ERJ-3EKFxxxxV"))
      (libsource (lib "eagle-import") (part "jonnew_R_0603"))
    )
    (comp (ref "R39")
      (value "13.3k")
      (footprint "eagle-import:0603")
      (fields (field (name "MPN") "ERJ-3EKFxxxxV"))
      (libsource (lib "eagle-import") (part "jonnew_R_0603"))
    )
    (comp (ref "R40")
      (value "22")
      (footprint "eagle-import:0402")
      (libsource (lib "eagle-import") (part "jonnew_R_0402"))
    )
    (comp (ref "R41")
      (value "22")
      (footprint "eagle-import:0402")
      (libsource (lib "eagle-import") (part "jonnew_R_0402"))
    )
    (comp (ref "R42")
      (value "49.9")
      (footprint "eagle-import:0402")
      (libsource (lib "eagle-import") (part "jonnew_R_0402"))
    )
    (comp (ref "R43")
      (value "22")
      (footprint "eagle-import:0402")
      (libsource (lib "eagle-import") (part "jonnew_R_0402"))
    )
    (comp (ref "R44")
      (value "22")
      (footprint "eagle-import:0402")
      (libsource (lib "eagle-import") (part "jonnew_R_0402"))
    )
    (comp (ref "R45")
      (value "22")
      (footprint "eagle-import:0402")
      (libsource (lib "eagle-import") (part "jonnew_R_0402"))
    )
    (comp (ref "R46")
      (value "22")
      (footprint "eagle-import:0402")
      (libsource (lib "eagle-import") (part "jonnew_R_0402"))
    )
    (comp (ref "R47")
      (value "22")
      (footprint "eagle-import:0402")
      (libsource (lib "eagle-import") (part "jonnew_R_0402"))
    )
    (comp (ref "R48")
      (value "22")
      (footprint "eagle-import:0402")
      (libsource (lib "eagle-import") (part "jonnew_R_0402"))
    )
    (comp (ref "R49")
      (value "22")
      (footprint "eagle-import:0402")
      (libsource (lib "eagle-import") (part "jonnew_R_0402"))
    )
    (comp (ref "R50")
      (value "22")
      (footprint "eagle-import:0402")
      (libsource (lib "eagle-import") (part "jonnew_R_0402"))
    )
    (comp (ref "R51")
      (value "22")
      (footprint "eagle-import:0402")
      (libsource (lib "eagle-import") (part "jonnew_R_0402"))
    )
    (comp (ref "R52")
      (value "22")
      (footprint "eagle-import:0402")
      (libsource (lib "eagle-import") (part "jonnew_R_0402"))
    )
    (comp (ref "R53")
      (value "22")
      (footprint "eagle-import:0402")
      (libsource (lib "eagle-import") (part "jonnew_R_0402"))
    )
    (comp (ref "R54")
      (value "22")
      (footprint "eagle-import:0402")
      (libsource (lib "eagle-import") (part "jonnew_R_0402"))
    )
    (comp (ref "R55")
      (value "22")
      (footprint "eagle-import:0402")
      (libsource (lib "eagle-import") (part "jonnew_R_0402"))
    )
    (comp (ref "R56")
      (value "10k")
      (footprint "eagle-import:0402")
      (libsource (lib "eagle-import") (part "jonnew_R_0402"))
    )
    (comp (ref "R57")
      (value "22")
      (footprint "eagle-import:0402")
      (libsource (lib "eagle-import") (part "jonnew_R_0402"))
    )
    (comp (ref "R58")
      (value "22")
      (footprint "eagle-import:0402")
      (libsource (lib "eagle-import") (part "jonnew_R_0402"))
    )
    (comp (ref "R59")
      (value "22")
      (footprint "eagle-import:0402")
      (libsource (lib "eagle-import") (part "jonnew_R_0402"))
    )
    (comp (ref "R60")
      (value "22")
      (footprint "eagle-import:0402")
      (libsource (lib "eagle-import") (part "jonnew_R_0402"))
    )
    (comp (ref "R61")
      (value "10k")
      (footprint "eagle-import:0402")
      (libsource (lib "eagle-import") (part "jonnew_R_0402"))
    )
    (comp (ref "R62")
      (value "10k")
      (footprint "eagle-import:0402")
      (libsource (lib "eagle-import") (part "jonnew_R_0402"))
    )
    (comp (ref "R63")
      (value "10k")
      (footprint "eagle-import:0402")
      (libsource (lib "eagle-import") (part "jonnew_R_0402"))
    )
    (comp (ref "R64")
      (value "1k")
      (footprint "eagle-import:0603")
      (fields (field (name "MPN") "ERJ-3EKFxxxxV"))
      (libsource (lib "eagle-import") (part "jonnew_R_0603"))
    )
    (comp (ref "R65")
      (value "10k")
      (footprint "eagle-import:0402")
      (libsource (lib "eagle-import") (part "jonnew_R_0402"))
    )
    (comp (ref "R66")
      (value "1k")
      (footprint "eagle-import:0603")
      (fields (field (name "MPN") "ERJ-3EKFxxxxV"))
      (libsource (lib "eagle-import") (part "cyclops_R_0603"))
    )
    (comp (ref "R67")
      (value "100k")
      (footprint "eagle-import:0603")
      (fields (field (name "MPN") "ERJ-3EKFxxxxV"))
      (libsource (lib "eagle-import") (part "jonnew_R_0603"))
    )
    (comp (ref "R68")
      (value "1k")
      (footprint "eagle-import:0603")
      (fields (field (name "MPN") "ERJ-3EKFxxxxV"))
      (libsource (lib "eagle-import") (part "cyclops_R_0603"))
    )
    (comp (ref "R69")
      (value "100k")
      (footprint "eagle-import:0603")
      (fields (field (name "MPN") "ERJ-3EKFxxxxV"))
      (libsource (lib "eagle-import") (part "cyclops_R_0603"))
    )
    (comp (ref "R70")
      (value "1k")
      (footprint "eagle-import:0603")
      (fields (field (name "MPN") "ERJ-3EKFxxxxV"))
      (libsource (lib "eagle-import") (part "jonnew_R_0603"))
    )
    (comp (ref "R71")
      (value "1k")
      (footprint "eagle-import:0603")
      (fields (field (name "MPN") "ERJ-3EKFxxxxV"))
      (libsource (lib "eagle-import") (part "jonnew_R_0603"))
    )
    (comp (ref "R72")
      (value "10k")
      (footprint "eagle-import:0402")
      (libsource (lib "eagle-import") (part "jonnew_R_0402"))
    )
    (comp (ref "R73")
      (value "10k")
      (footprint "eagle-import:0402")
      (libsource (lib "eagle-import") (part "jonnew_R_0402"))
    )
    (comp (ref "R74")
      (value "10k")
      (footprint "eagle-import:0402")
      (libsource (lib "eagle-import") (part "jonnew_R_0402"))
    )
    (comp (ref "R75")
      (value "0")
      (footprint "eagle-import:0402")
      (libsource (lib "eagle-import") (part "jonnew_R_0402"))
    )
    (comp (ref "R76")
      (value "0")
      (footprint "eagle-import:0402")
      (libsource (lib "eagle-import") (part "jonnew_R_0402"))
    )
    (comp (ref "R77")
      (value "3k")
      (footprint "eagle-import:0402")
      (libsource (lib "eagle-import") (part "jonnew_R_0402"))
    )
    (comp (ref "R78")
      (value "22")
      (footprint "eagle-import:0402")
      (libsource (lib "eagle-import") (part "jonnew_R_0402"))
    )
    (comp (ref "R79")
      (value "0")
      (footprint "eagle-import:0402")
      (libsource (lib "eagle-import") (part "jonnew_R_0402"))
    )
    (comp (ref "R80")
      (value "0")
      (footprint "eagle-import:0402")
      (libsource (lib "eagle-import") (part "jonnew_R_0402"))
    )
    (comp (ref "R81")
      (value "330k, 1kV")
      (footprint "eagle-import:1206")
      (libsource (lib "eagle-import") (part "jonnew_R_1206"))
    )
    (comp (ref "R82")
      (value "330k,1kV")
      (footprint "eagle-import:1206")
      (libsource (lib "eagle-import") (part "jonnew_R_1206"))
    )
    (comp (ref "R83")
      (value "330k, 1kV")
      (footprint "eagle-import:1206")
      (libsource (lib "eagle-import") (part "jonnew_R_1206"))
    )
    (comp (ref "S1")
      (value "SPST_TACT2_EVQPF")
      (footprint "eagle-import:EVQPF")
      (libsource (lib "eagle-import") (part "SPST_TACT2_EVQPF"))
    )
    (comp (ref "TERM")
      (value "569-011x")
      (footprint "eagle-import:569-011X-X00_LED_ARRAY")
      (libsource (lib "eagle-import") (part "LED_2X_VERTICAL"))
    )
    (comp (ref "TP1")
      (value "DI1")
      (footprint "eagle-import:TP09SQ")
      (libsource (lib "eagle-import") (part "TPTP09SQ"))
    )
    (comp (ref "TP2")
      (value "DI0")
      (footprint "eagle-import:TP09SQ")
      (libsource (lib "eagle-import") (part "TPTP09SQ"))
    )
    (comp (ref "TP3")
      (value "GND")
      (footprint "eagle-import:TESTPOINT_0.035IN")
      (libsource (lib "eagle-import") (part "TP_0.035IN"))
    )
    (comp (ref "TP4")
      (value "GND")
      (footprint "eagle-import:TESTPOINT_2MM")
      (libsource (lib "eagle-import") (part "TP_2MM"))
    )
    (comp (ref "TP5")
      (value "GND")
      (footprint "eagle-import:TESTPOINT_2MM")
      (libsource (lib "eagle-import") (part "TP_2MM"))
    )
    (comp (ref "TP6")
      (value "GND")
      (footprint "eagle-import:TESTPOINT_2MM")
      (libsource (lib "eagle-import") (part "TP_2MM"))
    )
    (comp (ref "TP7")
      (value "GND")
      (footprint "eagle-import:TESTPOINT_2MM")
      (libsource (lib "eagle-import") (part "TP_2MM"))
    )
    (comp (ref "TP8")
      (value "GND")
      (footprint "eagle-import:TESTPOINT_2MM")
      (libsource (lib "eagle-import") (part "TP_2MM"))
    )
    (comp (ref "TP9")
      (value "GND")
      (footprint "eagle-import:TESTPOINT_2MM")
      (libsource (lib "eagle-import") (part "TP_2MM"))
    )
    (comp (ref "TP10")
      (value "+3.3V")
      (footprint "eagle-import:TESTPOINT_2MM")
      (libsource (lib "eagle-import") (part "TP_2MM"))
    )
    (comp (ref "TP11")
      (value "+3.3V")
      (footprint "eagle-import:TESTPOINT_2MM")
      (libsource (lib "eagle-import") (part "TP_2MM"))
    )
    (comp (ref "TP12")
      (value "+12V(FPGA)")
      (footprint "eagle-import:TESTPOINT_2MM")
      (libsource (lib "eagle-import") (part "TP_2MM"))
    )
    (comp (ref "TP13")
      (value "+12V(ATX)")
      (footprint "eagle-import:TESTPOINT_2MM")
      (libsource (lib "eagle-import") (part "TP_2MM"))
    )
    (comp (ref "TP14")
      (value "VPROTECT(+4.3V)")
      (footprint "eagle-import:TESTPOINT_0.035IN")
      (libsource (lib "eagle-import") (part "TP_0.035IN"))
    )
    (comp (ref "TP15")
      (value "SCL(ISO)")
      (footprint "eagle-import:TESTPOINT_1MM")
      (libsource (lib "eagle-import") (part "TP_1MM"))
    )
    (comp (ref "TP16")
      (value "SDA(ISO)")
      (footprint "eagle-import:TESTPOINT_1MM")
      (libsource (lib "eagle-import") (part "TP_1MM"))
    )
    (comp (ref "TP17")
      (value "GND(ISO)")
      (footprint "eagle-import:TESTPOINT_1MM")
      (libsource (lib "eagle-import") (part "TP_1MM"))
    )
    (comp (ref "TP18")
      (value "GND")
      (footprint "eagle-import:TESTPOINT_1MM")
      (libsource (lib "eagle-import") (part "TP_1MM"))
    )
    (comp (ref "TP19")
      (value "SDA")
      (footprint "eagle-import:TESTPOINT_1MM")
      (libsource (lib "eagle-import") (part "TP_1MM"))
    )
    (comp (ref "TP20")
      (value "SCL")
      (footprint "eagle-import:TESTPOINT_1MM")
      (libsource (lib "eagle-import") (part "TP_1MM"))
    )
    (comp (ref "TP21")
      (value "GND(ISO)")
      (footprint "eagle-import:TESTPOINT_1MM")
      (libsource (lib "eagle-import") (part "TP_1MM"))
    )
    (comp (ref "TP22")
      (value "+1.8V(ISO)")
      (footprint "eagle-import:TESTPOINT_1MM")
      (libsource (lib "eagle-import") (part "TP_1MM"))
    )
    (comp (ref "TP23")
      (value "+3.3V(ISO)")
      (footprint "eagle-import:TESTPOINT_2MM")
      (libsource (lib "eagle-import") (part "TP_2MM"))
    )
    (comp (ref "TP24")
      (value "+5.5V(ISO)")
      (footprint "eagle-import:TESTPOINT_2MM")
      (libsource (lib "eagle-import") (part "TP_2MM"))
    )
    (comp (ref "TP25")
      (value "GND(ISO)")
      (footprint "eagle-import:TESTPOINT_1MM")
      (libsource (lib "eagle-import") (part "TP_1MM"))
    )
    (comp (ref "TP26")
      (value "GND(ISO)")
      (footprint "eagle-import:TESTPOINT_1MM")
      (libsource (lib "eagle-import") (part "TP_1MM"))
    )
    (comp (ref "U1")
      (value "ADCMP600")
      (footprint "eagle-import:SOT-23-5")
      (libsource (lib "eagle-import") (part "COMPARITOR_ADCMP600"))
    )
    (comp (ref "U2")
      (value "ADCMP600")
      (footprint "eagle-import:SOT-23-5")
      (libsource (lib "eagle-import") (part "COMPARITOR_ADCMP600"))
    )
    (comp (ref "U3")
      (value "SN74LVT125")
      (footprint "eagle-import:SO14")
      (libsource (lib "eagle-import") (part "QUAD-LINE-DRIVER_SOIC"))
    )
    (comp (ref "U4")
      (value "MCP47FEBX2")
      (footprint "eagle-import:TSSOP-8")
      (libsource (lib "eagle-import") (part "MCP47FEBX2"))
    )
    (comp (ref "U5")
      (value "ISO1540DR")
      (footprint "eagle-import:SOIC127P500X400-8N")
      (libsource (lib "eagle-import") (part "DIGISO-I2C_SOIC"))
    )
    (comp (ref "U6")
      (value "UEI15-050-Q12P-C")
      (footprint "eagle-import:UEI15")
      (libsource (lib "eagle-import") (part "DC-DC-CONVERTER-ADJ_UEI15"))
    )
    (comp (ref "U7")
      (value "LTM4622_BGA")
      (footprint "eagle-import:BGA_5X5_625X625")
      (libsource (lib "eagle-import") (part "LTM4622_BGA"))
    )
    (comp (ref "U8")
      (value "SN65LVDT388A")
      (footprint "eagle-import:TSSOP-38")
      (libsource (lib "eagle-import") (part "SN65LVDS388A"))
    )
    (comp (ref "U9")
      (value "ISO7740")
      (footprint "eagle-import:SOIC_WIDE_16")
      (libsource (lib "eagle-import") (part "DIGISO-4-0"))
    )
    (comp (ref "U10")
      (value "ISO7740")
      (footprint "eagle-import:SOIC_WIDE_16")
      (libsource (lib "eagle-import") (part "DIGISO-4-0"))
    )
    (comp (ref "U11")
      (value "SN65LVDS387")
      (footprint "eagle-import:TSSOP-64")
      (libsource (lib "eagle-import") (part "SN65LVDS387_TSSOP"))
    )
    (comp (ref "U12")
      (value "DS90UB914A-Q1")
      (footprint "eagle-import:WQFN48")
      (libsource (lib "eagle-import") (part "DS90UB914A-Q1"))
    )
    (comp (ref "U13")
      (value "ISO7740")
      (footprint "eagle-import:SOIC_WIDE_16")
      (libsource (lib "eagle-import") (part "DIGISO-4-0"))
    )
    (comp (ref "U14")
      (value "ISO7740")
      (footprint "eagle-import:SOIC_WIDE_16")
      (libsource (lib "eagle-import") (part "DIGISO-4-0"))
    )
    (comp (ref "U15")
      (value "DIPSW-004_SMD-0.05IN")
      (footprint "eagle-import:DIP04-SMD")
      (libsource (lib "eagle-import") (part "DIPSW-004_SMD-0.05IN"))
    )
    (comp (ref "U16")
      (value "SN65LVDS391")
      (footprint "eagle-import:TSSOP-16")
      (libsource (lib "eagle-import") (part "SN65LVDS391"))
    )
    (comp (ref "U17")
      (value "ISO7740")
      (footprint "eagle-import:SOIC_WIDE_16")
      (libsource (lib "eagle-import") (part "DIGISO-4-0"))
    )
    (comp (ref "U18")
      (value "ISO7741")
      (footprint "eagle-import:SOIC_WIDE_16")
      (libsource (lib "eagle-import") (part "DIGISO-3-1"))
    )
    (comp (ref "X1")
      (value "PCI-MECH_STD-H_HALF-W_FMC-STRAIN")
      (footprint "eagle-import:PCI-ADDIN_STD-H_HALF-L_FMC-STRAIN")
      (libsource (lib "eagle-import") (part "PCI-MECH_STD-H_HALF-W_FMC-STRAIN"))
    )
  )
  (nets
    (net (code "1") (name "+3V3") (class "Default")
      (node (ref "C1") (pin "1") (pinfunction "1_1") (pintype "passive"))
      (node (ref "C10") (pin "2") (pinfunction "2_2") (pintype "passive"))
      (node (ref "C12") (pin "2") (pinfunction "2_2") (pintype "passive"))
      (node (ref "C13") (pin "2") (pinfunction "2_2") (pintype "passive"))
      (node (ref "C14") (pin "2") (pinfunction "2_2") (pintype "passive"))
      (node (ref "C15") (pin "2") (pinfunction "2_2") (pintype "passive"))
      (node (ref "C18") (pin "2") (pinfunction "2_2") (pintype "passive"))
      (node (ref "C25") (pin "2") (pinfunction "2_2") (pintype "passive"))
      (node (ref "C26") (pin "2") (pinfunction "2_2") (pintype "passive"))
      (node (ref "C27") (pin "2") (pinfunction "2_2") (pintype "passive"))
      (node (ref "C28") (pin "2") (pinfunction "2_2") (pintype "passive"))
      (node (ref "C3") (pin "1") (pinfunction "1_1") (pintype "passive"))
      (node (ref "C33") (pin "2") (pinfunction "2_2") (pintype "passive"))
      (node (ref "C42") (pin "2") (pinfunction "2_2") (pintype "passive"))
      (node (ref "C43") (pin "2") (pinfunction "2_2") (pintype "passive"))
      (node (ref "C44") (pin "2") (pinfunction "2_2") (pintype "passive"))
      (node (ref "C45") (pin "2") (pinfunction "2_2") (pintype "passive"))
      (node (ref "C46") (pin "2") (pinfunction "2_2") (pintype "passive"))
      (node (ref "C47") (pin "2") (pinfunction "2_2") (pintype "passive"))
      (node (ref "C49") (pin "2") (pinfunction "2_2") (pintype "passive"))
      (node (ref "C60") (pin "2") (pinfunction "2_2") (pintype "passive"))
      (node (ref "C63") (pin "2") (pinfunction "2_2") (pintype "passive"))
      (node (ref "C71") (pin "2") (pinfunction "2_2") (pintype "passive"))
      (node (ref "C72") (pin "2") (pinfunction "2_2") (pintype "passive"))
      (node (ref "C73") (pin "2") (pinfunction "2_2") (pintype "passive"))
      (node (ref "C74") (pin "2") (pinfunction "2_2") (pintype "passive"))
      (node (ref "C75") (pin "2") (pinfunction "2_2") (pintype "passive"))
      (node (ref "C8") (pin "+") (pinfunction "+_+") (pintype "passive"))
      (node (ref "C81") (pin "2") (pinfunction "2_2") (pintype "passive"))
      (node (ref "C9") (pin "2") (pinfunction "2_2") (pintype "passive"))
      (node (ref "FMC_LPC") (pin "P$116") (pinfunction "3P3V2_P$116") (pintype "bidirectional"))
      (node (ref "FMC_LPC") (pin "P$118") (pinfunction "3P3V3_P$118") (pintype "bidirectional"))
      (node (ref "FMC_LPC") (pin "P$120") (pinfunction "3P3V4_P$120") (pintype "bidirectional"))
      (node (ref "FMC_LPC") (pin "P$159") (pinfunction "3P3V1_P$159") (pintype "bidirectional"))
      (node (ref "J3") (pin "2") (pinfunction "2_2") (pintype "bidirectional"))
      (node (ref "R20") (pin "2") (pinfunction "2_2") (pintype "passive"))
      (node (ref "R21") (pin "2") (pinfunction "2_2") (pintype "passive"))
      (node (ref "R22") (pin "2") (pinfunction "2_2") (pintype "passive"))
      (node (ref "R27") (pin "2") (pinfunction "2_2") (pintype "passive"))
      (node (ref "R28") (pin "2") (pinfunction "2_2") (pintype "passive"))
      (node (ref "R32") (pin "2") (pinfunction "2_2") (pintype "passive"))
      (node (ref "R33") (pin "2") (pinfunction "2_2") (pintype "passive"))
      (node (ref "TP10") (pin "1") (pinfunction "TP_1") (pintype "bidirectional"))
      (node (ref "TP11") (pin "1") (pinfunction "TP_1") (pintype "bidirectional"))
      (node (ref "U1") (pin "5") (pinfunction "V+_5") (pintype "power_in"))
      (node (ref "U10") (pin "P10") (pinfunction "EN2_P10") (pintype "bidirectional"))
      (node (ref "U10") (pin "P16") (pinfunction "VDD2_P16") (pintype "power_in"))
      (node (ref "U11") (pin "10") (pinfunction "ENB_10") (pintype "input"))
      (node (ref "U11") (pin "16") (pinfunction "VCC_16") (pintype "power_in"))
      (node (ref "U11") (pin "17") (pinfunction "VCC_17") (pintype "power_in"))
      (node (ref "U11") (pin "2") (pinfunction "VCC_2") (pintype "power_in"))
      (node (ref "U11") (pin "23") (pinfunction "ENC_23") (pintype "input"))
      (node (ref "U11") (pin "28") (pinfunction "END_28") (pintype "input"))
      (node (ref "U11") (pin "3") (pinfunction "VCC_3") (pintype "power_in"))
      (node (ref "U11") (pin "30") (pinfunction "VCC_30") (pintype "power_in"))
      (node (ref "U11") (pin "31") (pinfunction "VCC_31") (pintype "power_in"))
      (node (ref "U11") (pin "5") (pinfunction "ENA_5") (pintype "input"))
      (node (ref "U13") (pin "P10") (pinfunction "EN2_P10") (pintype "bidirectional"))
      (node (ref "U13") (pin "P16") (pinfunction "VDD2_P16") (pintype "power_in"))
      (node (ref "U14") (pin "P10") (pinfunction "EN2_P10") (pintype "bidirectional"))
      (node (ref "U14") (pin "P16") (pinfunction "VDD2_P16") (pintype "power_in"))
      (node (ref "U16") (pin "1") (pinfunction "EN1,2_1") (pintype "input"))
      (node (ref "U16") (pin "4") (pinfunction "VCC_4") (pintype "power_in"))
      (node (ref "U16") (pin "8") (pinfunction "EN3,4_8") (pintype "input"))
      (node (ref "U17") (pin "P1") (pinfunction "VDD1_P1") (pintype "power_in"))
      (node (ref "U18") (pin "P10") (pinfunction "EN2_P10") (pintype "bidirectional"))
      (node (ref "U18") (pin "P16") (pinfunction "VDD2_P16") (pintype "power_in"))
      (node (ref "U2") (pin "5") (pinfunction "V+_5") (pintype "power_in"))
      (node (ref "U3") (pin "14") (pinfunction "VCC_14") (pintype "passive"))
      (node (ref "U4") (pin "1") (pinfunction "VDD_1") (pintype "power_in"))
      (node (ref "U4") (pin "2") (pinfunction "REFA_2") (pintype "input"))
      (node (ref "U5") (pin "1") (pinfunction "VDD1_1") (pintype "power_in"))
      (node (ref "U8") (pin "21") (pinfunction "VCC_21") (pintype "power_in"))
      (node (ref "U8") (pin "22") (pinfunction "END_22") (pintype "input"))
      (node (ref "U8") (pin "25") (pinfunction "ENC_25") (pintype "input"))
      (node (ref "U8") (pin "29") (pinfunction "DVCC_29") (pintype "power_in"))
      (node (ref "U8") (pin "33") (pinfunction "ENB_33") (pintype "input"))
      (node (ref "U8") (pin "36") (pinfunction "ENA_36") (pintype "input"))
      (node (ref "U8") (pin "37") (pinfunction "VCC_37") (pintype "power_in"))
      (node (ref "U9") (pin "P10") (pinfunction "EN2_P10") (pintype "bidirectional"))
      (node (ref "U9") (pin "P16") (pinfunction "VDD2_P16") (pintype "power_in"))
    )
    (net (code "2") (name "+3V3_ISO") (class "Default")
      (node (ref "C17") (pin "2") (pinfunction "2_2") (pintype "passive"))
      (node (ref "C19") (pin "2") (pinfunction "2_2") (pintype "passive"))
      (node (ref "C32") (pin "2") (pinfunction "2_2") (pintype "passive"))
      (node (ref "C48") (pin "2") (pinfunction "2_2") (pintype "passive"))
      (node (ref "C59") (pin "2") (pinfunction "2_2") (pintype "passive"))
      (node (ref "C62") (pin "2") (pinfunction "2_2") (pintype "passive"))
      (node (ref "C64") (pin "2") (pinfunction "2_2") (pintype "passive"))
      (node (ref "C65") (pin "2") (pinfunction "2_2") (pintype "passive"))
      (node (ref "C66") (pin "2") (pinfunction "2_2") (pintype "passive"))
      (node (ref "C67") (pin "2") (pinfunction "2_2") (pintype "passive"))
      (node (ref "C68") (pin "2") (pinfunction "2_2") (pintype "passive"))
      (node (ref "C69") (pin "2") (pinfunction "2_2") (pintype "passive"))
      (node (ref "C70") (pin "2") (pinfunction "2_2") (pintype "passive"))
      (node (ref "C80") (pin "2") (pinfunction "2_2") (pintype "passive"))
      (node (ref "J4") (pin "3") (pinfunction "3_3") (pintype "passive"))
      (node (ref "R30") (pin "2") (pinfunction "2_2") (pintype "passive"))
      (node (ref "R31") (pin "2") (pinfunction "2_2") (pintype "passive"))
      (node (ref "R36") (pin "2") (pinfunction "2_2") (pintype "passive"))
      (node (ref "R56") (pin "1") (pinfunction "1_1") (pintype "passive"))
      (node (ref "R61") (pin "2") (pinfunction "2_2") (pintype "passive"))
      (node (ref "R62") (pin "2") (pinfunction "2_2") (pintype "passive"))
      (node (ref "R63") (pin "2") (pinfunction "2_2") (pintype "passive"))
      (node (ref "R65") (pin "2") (pinfunction "2_2") (pintype "passive"))
      (node (ref "R66") (pin "2") (pinfunction "2_2") (pintype "passive"))
      (node (ref "TP23") (pin "1") (pinfunction "TP_1") (pintype "bidirectional"))
      (node (ref "U10") (pin "P1") (pinfunction "VDD1_P1") (pintype "power_in"))
      (node (ref "U12") (pin "20") (pinfunction "VDDIO2_20") (pintype "bidirectional"))
      (node (ref "U12") (pin "29") (pinfunction "VDDIO1_29") (pintype "bidirectional"))
      (node (ref "U12") (pin "7") (pinfunction "VDDIO3_7") (pintype "bidirectional"))
      (node (ref "U13") (pin "P1") (pinfunction "VDD1_P1") (pintype "power_in"))
      (node (ref "U14") (pin "P1") (pinfunction "VDD1_P1") (pintype "power_in"))
      (node (ref "U17") (pin "P10") (pinfunction "EN2_P10") (pintype "bidirectional"))
      (node (ref "U17") (pin "P16") (pinfunction "VDD2_P16") (pintype "power_in"))
      (node (ref "U18") (pin "P1") (pinfunction "VDD1_P1") (pintype "power_in"))
      (node (ref "U18") (pin "P7") (pinfunction "EN1_P7") (pintype "bidirectional"))
      (node (ref "U5") (pin "8") (pinfunction "VDD2_8") (pintype "power_in"))
      (node (ref "U7") (pin "A1") (pinfunction "VOUT2_A1") (pintype "power_in"))
      (node (ref "U7") (pin "B1") (pinfunction "VOUT2_B1") (pintype "power_in"))
      (node (ref "U9") (pin "P1") (pinfunction "VDD1_P1") (pintype "power_in"))
    )
    (net (code "3") (name "+3V3_ISO_PG_ISO") (class "Default")
      (node (ref "R34") (pin "2") (pinfunction "2_2") (pintype "passive"))
      (node (ref "U14") (pin "P6") (pinfunction "VID_P6") (pintype "input"))
      (node (ref "U7") (pin "D4") (pinfunction "PGOOD1_D4") (pintype "open_collector"))
    )
    (net (code "4") (name "+3V3_ISO_PG_N") (class "Default")
      (node (ref "FMC_LPC") (pin "P$107") (pinfunction "LA26_N_P$107") (pintype "bidirectional"))
      (node (ref "U11") (pin "33") (pinfunction "D4Z_33") (pintype "output"))
    )
    (net (code "5") (name "+3V3_ISO_PG_P") (class "Default")
      (node (ref "FMC_LPC") (pin "P$106") (pinfunction "LA26_P_P$106") (pintype "bidirectional"))
      (node (ref "U11") (pin "34") (pinfunction "D4Y_34") (pintype "output"))
    )
    (net (code "6") (name "/+1V8_ISO") (class "Default")
      (node (ref "C20") (pin "2") (pinfunction "2_2") (pintype "passive"))
      (node (ref "C34") (pin "2") (pinfunction "2_2") (pintype "passive"))
      (node (ref "C35") (pin "2") (pinfunction "2_2") (pintype "passive"))
      (node (ref "C50") (pin "2") (pinfunction "2_2") (pintype "passive"))
      (node (ref "C51") (pin "2") (pinfunction "2_2") (pintype "passive"))
      (node (ref "C55") (pin "2") (pinfunction "2_2") (pintype "passive"))
      (node (ref "C56") (pin "2") (pinfunction "2_2") (pintype "passive"))
      (node (ref "J4") (pin "2") (pinfunction "2_2") (pintype "passive"))
      (node (ref "L1") (pin "2") (pinfunction "2_2") (pintype "passive"))
      (node (ref "L2") (pin "1") (pinfunction "1_1") (pintype "passive"))
      (node (ref "L3") (pin "2") (pinfunction "2_2") (pintype "passive"))
      (node (ref "R72") (pin "1") (pinfunction "1_1") (pintype "passive"))
      (node (ref "R73") (pin "1") (pinfunction "1_1") (pintype "passive"))
      (node (ref "R74") (pin "1") (pinfunction "1_1") (pintype "passive"))
      (node (ref "TP22") (pin "1") (pinfunction "TP_1") (pintype "bidirectional"))
      (node (ref "U12") (pin "17") (pinfunction "VDDD_17") (pintype "power_in"))
      (node (ref "U12") (pin "3") (pinfunction "VDDSSCG_3") (pintype "power_in"))
      (node (ref "U12") (pin "36") (pinfunction "VDDR_36") (pintype "power_in"))
      (node (ref "U7") (pin "D1") (pinfunction "VOUT1_D1") (pintype "power_in"))
      (node (ref "U7") (pin "E1") (pinfunction "VOUT1_E1") (pintype "power_in"))
    )
    (net (code "7") (name "/+3V3_ISO_PG") (class "Default")
      (node (ref "U11") (pin "27") (pinfunction "D4A_27") (pintype "input"))
      (node (ref "U14") (pin "P11") (pinfunction "VOD_P11") (pintype "output"))
    )
    (net (code "8") (name "/+5.5V_ISO") (class "Default")
      (node (ref "C22") (pin "2") (pinfunction "2_2") (pintype "passive"))
      (node (ref "C23") (pin "+") (pinfunction "+_+") (pintype "passive"))
      (node (ref "C24") (pin "+") (pinfunction "+_+") (pintype "passive"))
      (node (ref "C31") (pin "2") (pinfunction "2_2") (pintype "passive"))
      (node (ref "C77") (pin "1") (pinfunction "1_1") (pintype "passive"))
      (node (ref "C79") (pin "2") (pinfunction "2_2") (pintype "passive"))
      (node (ref "L4") (pin "1") (pinfunction "1_1") (pintype "passive"))
      (node (ref "TP24") (pin "1") (pinfunction "TP_1") (pintype "bidirectional"))
      (node (ref "U6") (pin "3") (pinfunction "+VO_3") (pintype "power_in"))
      (node (ref "U7") (pin "A2") (pinfunction "VIN_A2") (pintype "power_in"))
      (node (ref "U7") (pin "B2") (pinfunction "RUN2_B2") (pintype "input"))
      (node (ref "U7") (pin "B3") (pinfunction "VIN_B3") (pintype "power_in"))
      (node (ref "U7") (pin "D2") (pinfunction "RUN1_D2") (pintype "input"))
      (node (ref "U7") (pin "D3") (pinfunction "VIN_D3") (pintype "power_in"))
      (node (ref "U7") (pin "E2") (pinfunction "VIN_E2") (pintype "power_in"))
    )
    (net (code "9") (name "/+12V_ATX") (class "Default")
      (node (ref "C11") (pin "+") (pinfunction "+_+") (pintype "passive"))
      (node (ref "C21") (pin "+") (pinfunction "+_+") (pintype "passive"))
      (node (ref "L7/0R") (pin "1") (pinfunction "1_1") (pintype "passive"))
      (node (ref "PCIE-PWR") (pin "1") (pinfunction "1_1") (pintype "passive"))
      (node (ref "PCIE-PWR") (pin "2") (pinfunction "2_2") (pintype "passive"))
      (node (ref "PCIE-PWR") (pin "3") (pinfunction "3_3") (pintype "passive"))
      (node (ref "TP13") (pin "1") (pinfunction "TP_1") (pintype "bidirectional"))
    )
    (net (code "10") (name "/+12V_FPGA") (class "Default")
      (node (ref "C5") (pin "+") (pinfunction "+_+") (pintype "passive"))
      (node (ref "C6") (pin "2") (pinfunction "2_2") (pintype "passive"))
      (node (ref "C7") (pin "2") (pinfunction "2_2") (pintype "passive"))
      (node (ref "FMC_LPC") (pin "P$155") (pinfunction "12P0V1_P$155") (pintype "bidirectional"))
      (node (ref "FMC_LPC") (pin "P$157") (pinfunction "12P0V2_P$157") (pintype "bidirectional"))
      (node (ref "J3") (pin "3") (pinfunction "3_3") (pintype "bidirectional"))
      (node (ref "R24") (pin "2") (pinfunction "2_2") (pintype "passive"))
      (node (ref "R25") (pin "2") (pinfunction "2_2") (pintype "passive"))
      (node (ref "TP12") (pin "1") (pinfunction "TP_1") (pintype "bidirectional"))
    )
    (net (code "11") (name "/BISTEN") (class "Default")
      (node (ref "R65") (pin "1") (pinfunction "1_1") (pintype "passive"))
      (node (ref "U12") (pin "6") (pinfunction "BISTEN_6") (pintype "input"))
      (node (ref "U15") (pin "1") (pinfunction "1_1") (pintype "passive"))
    )
    (net (code "12") (name "/D0") (class "Default")
      (node (ref "U11") (pin "6") (pinfunction "A1A_6") (pintype "input"))
      (node (ref "U9") (pin "P14") (pinfunction "VOA_P14") (pintype "output"))
    )
    (net (code "13") (name "/D1") (class "Default")
      (node (ref "U11") (pin "7") (pinfunction "A2A_7") (pintype "input"))
      (node (ref "U9") (pin "P13") (pinfunction "VOB_P13") (pintype "output"))
    )
    (net (code "14") (name "/D2") (class "Default")
      (node (ref "U11") (pin "8") (pinfunction "A3A_8") (pintype "input"))
      (node (ref "U9") (pin "P12") (pinfunction "VOC_P12") (pintype "output"))
    )
    (net (code "15") (name "/D3") (class "Default")
      (node (ref "U11") (pin "9") (pinfunction "A4A_9") (pintype "input"))
      (node (ref "U9") (pin "P11") (pinfunction "VOD_P11") (pintype "output"))
    )
    (net (code "16") (name "/D4") (class "Default")
      (node (ref "U10") (pin "P14") (pinfunction "VOA_P14") (pintype "output"))
      (node (ref "U11") (pin "11") (pinfunction "B1A_11") (pintype "input"))
    )
    (net (code "17") (name "/D5") (class "Default")
      (node (ref "U10") (pin "P13") (pinfunction "VOB_P13") (pintype "output"))
      (node (ref "U11") (pin "12") (pinfunction "B2A_12") (pintype "input"))
    )
    (net (code "18") (name "/D6") (class "Default")
      (node (ref "U10") (pin "P12") (pinfunction "VOC_P12") (pintype "output"))
      (node (ref "U11") (pin "13") (pinfunction "B3A_13") (pintype "input"))
    )
    (net (code "19") (name "/D7") (class "Default")
      (node (ref "U10") (pin "P11") (pinfunction "VOD_P11") (pintype "output"))
      (node (ref "U11") (pin "14") (pinfunction "B4A_14") (pintype "input"))
    )
    (net (code "20") (name "/D8") (class "Default")
      (node (ref "U11") (pin "19") (pinfunction "C1A_19") (pintype "input"))
      (node (ref "U13") (pin "P14") (pinfunction "VOA_P14") (pintype "output"))
    )
    (net (code "21") (name "/D9") (class "Default")
      (node (ref "U11") (pin "20") (pinfunction "C2A_20") (pintype "input"))
      (node (ref "U13") (pin "P13") (pinfunction "VOB_P13") (pintype "output"))
    )
    (net (code "22") (name "/D10") (class "Default")
      (node (ref "U11") (pin "21") (pinfunction "C3A_21") (pintype "input"))
      (node (ref "U13") (pin "P12") (pinfunction "VOC_P12") (pintype "output"))
    )
    (net (code "23") (name "/D11") (class "Default")
      (node (ref "U11") (pin "22") (pinfunction "C4A_22") (pintype "input"))
      (node (ref "U13") (pin "P11") (pinfunction "VOD_P11") (pintype "output"))
    )
    (net (code "24") (name "/DOUTP_F") (class "Default")
      (node (ref "C57") (pin "2") (pinfunction "2_2") (pintype "passive"))
      (node (ref "D7") (pin "C") (pinfunction "C_C") (pintype "passive"))
      (node (ref "L5") (pin "2") (pinfunction "2_2") (pintype "passive"))
      (node (ref "LINK") (pin "CLK") (pinfunction "1_CLK") (pintype "passive"))
      (node (ref "R70") (pin "2") (pinfunction "2_2") (pintype "passive"))
    )
    (net (code "25") (name "/HSYNC") (class "Default")
      (node (ref "U11") (pin "24") (pinfunction "D1A_24") (pintype "input"))
      (node (ref "U14") (pin "P14") (pinfunction "VOA_P14") (pintype "output"))
    )
    (net (code "26") (name "/N$40") (class "Default")
      (node (ref "J7") (pin "SIG") (pinfunction "1_SIG") (pintype "passive"))
      (node (ref "R79") (pin "1") (pinfunction "1_1") (pintype "passive"))
    )
    (net (code "27") (name "/OEN") (class "Default")
      (node (ref "R63") (pin "1") (pinfunction "1_1") (pintype "passive"))
      (node (ref "U12") (pin "5") (pinfunction "OEN_5") (pintype "input"))
      (node (ref "U15") (pin "2") (pinfunction "2_2") (pintype "passive"))
    )
    (net (code "28") (name "/OSS_SEL") (class "Default")
      (node (ref "R62") (pin "1") (pinfunction "1_1") (pintype "passive"))
      (node (ref "U12") (pin "4") (pinfunction "OSS_SEL_4") (pintype "input"))
      (node (ref "U15") (pin "3") (pinfunction "3_3") (pintype "passive"))
    )
    (net (code "29") (name "/PCLK") (class "Default")
      (node (ref "U11") (pin "26") (pinfunction "D3A_26") (pintype "input"))
      (node (ref "U14") (pin "P12") (pinfunction "VOC_P12") (pintype "output"))
    )
    (net (code "30") (name "/SEL") (class "Default")
      (node (ref "R61") (pin "1") (pinfunction "1_1") (pintype "passive"))
      (node (ref "U12") (pin "46") (pinfunction "SEL_46") (pintype "input"))
      (node (ref "U15") (pin "4") (pinfunction "4_4") (pintype "passive"))
    )
    (net (code "31") (name "/SMA_IN_ISO") (class "Default")
      (node (ref "J5") (pin "SIG") (pinfunction "1_SIG") (pintype "passive"))
      (node (ref "U18") (pin "P4") (pinfunction "VIB_P4") (pintype "input"))
    )
    (net (code "32") (name "/VSYNC") (class "Default")
      (node (ref "U11") (pin "25") (pinfunction "D2A_25") (pintype "input"))
      (node (ref "U14") (pin "P13") (pinfunction "VOB_P13") (pintype "output"))
    )
    (net (code "33") (name "2V5_REF") (class "Default")
      (node (ref "D5") (pin "1") (pinfunction "C_1") (pintype "passive"))
      (node (ref "J1") (pin "3") (pinfunction "3_3") (pintype "passive"))
      (node (ref "J2") (pin "3") (pinfunction "3_3") (pintype "passive"))
      (node (ref "R27") (pin "1") (pinfunction "1_1") (pintype "passive"))
    )
    (net (code "34") (name "BIAS_DI0") (class "Default")
      (node (ref "J1") (pin "1") (pinfunction "1_1") (pintype "passive"))
      (node (ref "U4") (pin "3") (pinfunction "VOUT0_3") (pintype "output"))
    )
    (net (code "35") (name "BIAS_DI1") (class "Default")
      (node (ref "J2") (pin "1") (pinfunction "1_1") (pintype "passive"))
      (node (ref "U4") (pin "4") (pinfunction "VOUT1_4") (pintype "output"))
    )
    (net (code "36") (name "D0_ISO") (class "Default")
      (node (ref "R55") (pin "1") (pinfunction "1_1") (pintype "passive"))
      (node (ref "U9") (pin "P3") (pinfunction "VIA_P3") (pintype "input"))
    )
    (net (code "37") (name "D0_N") (class "Default")
      (node (ref "FMC_LPC") (pin "P$98") (pinfunction "LA13_N_P$98") (pintype "bidirectional"))
      (node (ref "U11") (pin "63") (pinfunction "A1Z_63") (pintype "output"))
    )
    (net (code "38") (name "D0_P") (class "Default")
      (node (ref "FMC_LPC") (pin "P$97") (pinfunction "LA13_P_P$97") (pintype "bidirectional"))
      (node (ref "U11") (pin "64") (pinfunction "A1Y_64") (pintype "output"))
    )
    (net (code "39") (name "D1_ISO") (class "Default")
      (node (ref "R54") (pin "1") (pinfunction "1_1") (pintype "passive"))
      (node (ref "U9") (pin "P4") (pinfunction "VIB_P4") (pintype "input"))
    )
    (net (code "40") (name "D1_N") (class "Default")
      (node (ref "FMC_LPC") (pin "P$17") (pinfunction "LA11_N_P$17") (pintype "bidirectional"))
      (node (ref "U11") (pin "61") (pinfunction "A2Z_61") (pintype "output"))
    )
    (net (code "41") (name "D1_P") (class "Default")
      (node (ref "FMC_LPC") (pin "P$16") (pinfunction "LA11_P_P$16") (pintype "bidirectional"))
      (node (ref "U11") (pin "62") (pinfunction "A2Y_62") (pintype "output"))
    )
    (net (code "42") (name "D2_ISO") (class "Default")
      (node (ref "R53") (pin "1") (pinfunction "1_1") (pintype "passive"))
      (node (ref "U9") (pin "P5") (pinfunction "VIC_P5") (pintype "input"))
    )
    (net (code "43") (name "D2_N") (class "Default")
      (node (ref "FMC_LPC") (pin "P$56") (pinfunction "LA12_N_P$56") (pintype "bidirectional"))
      (node (ref "U11") (pin "59") (pinfunction "A3Z_59") (pintype "output"))
    )
    (net (code "44") (name "D2_P") (class "Default")
      (node (ref "FMC_LPC") (pin "P$55") (pinfunction "LA12_P_P$55") (pintype "bidirectional"))
      (node (ref "U11") (pin "60") (pinfunction "A3Y_60") (pintype "output"))
    )
    (net (code "45") (name "D3_ISO") (class "Default")
      (node (ref "R52") (pin "1") (pinfunction "1_1") (pintype "passive"))
      (node (ref "U9") (pin "P6") (pinfunction "VID_P6") (pintype "input"))
    )
    (net (code "46") (name "D3_N") (class "Default")
      (node (ref "FMC_LPC") (pin "P$135") (pinfunction "LA10_N_P$135") (pintype "bidirectional"))
      (node (ref "U11") (pin "57") (pinfunction "A4Z_57") (pintype "output"))
    )
    (net (code "47") (name "D3_P") (class "Default")
      (node (ref "FMC_LPC") (pin "P$134") (pinfunction "LA10_P_P$134") (pintype "bidirectional"))
      (node (ref "U11") (pin "58") (pinfunction "A4Y_58") (pintype "output"))
    )
    (net (code "48") (name "D4_ISO") (class "Default")
      (node (ref "R51") (pin "1") (pinfunction "1_1") (pintype "passive"))
      (node (ref "U10") (pin "P3") (pinfunction "VIA_P3") (pintype "input"))
    )
    (net (code "49") (name "D4_N") (class "Default")
      (node (ref "FMC_LPC") (pin "P$95") (pinfunction "LA09_N_P$95") (pintype "bidirectional"))
      (node (ref "U11") (pin "55") (pinfunction "B1Z_55") (pintype "output"))
    )
    (net (code "50") (name "D4_P") (class "Default")
      (node (ref "FMC_LPC") (pin "P$94") (pinfunction "LA09_P_P$94") (pintype "bidirectional"))
      (node (ref "U11") (pin "56") (pinfunction "B1Y_56") (pintype "output"))
    )
    (net (code "51") (name "D5_ISO") (class "Default")
      (node (ref "R50") (pin "1") (pinfunction "1_1") (pintype "passive"))
      (node (ref "U10") (pin "P4") (pinfunction "VIB_P4") (pintype "input"))
    )
    (net (code "52") (name "D5_N") (class "Default")
      (node (ref "FMC_LPC") (pin "P$14") (pinfunction "LA07_N_P$14") (pintype "bidirectional"))
      (node (ref "U11") (pin "53") (pinfunction "B2Z_53") (pintype "output"))
    )
    (net (code "53") (name "D5_P") (class "Default")
      (node (ref "FMC_LPC") (pin "P$13") (pinfunction "LA07_P_P$13") (pintype "bidirectional"))
      (node (ref "U11") (pin "54") (pinfunction "B2Y_54") (pintype "output"))
    )
    (net (code "54") (name "D6_ISO") (class "Default")
      (node (ref "R49") (pin "1") (pinfunction "1_1") (pintype "passive"))
      (node (ref "U10") (pin "P5") (pinfunction "VIC_P5") (pintype "input"))
    )
    (net (code "55") (name "D6_N") (class "Default")
      (node (ref "FMC_LPC") (pin "P$53") (pinfunction "LA08_N_P$53") (pintype "bidirectional"))
      (node (ref "U11") (pin "51") (pinfunction "B3Z_51") (pintype "output"))
    )
    (net (code "56") (name "D6_P") (class "Default")
      (node (ref "FMC_LPC") (pin "P$52") (pinfunction "LA08_P_P$52") (pintype "bidirectional"))
      (node (ref "U11") (pin "52") (pinfunction "B3Y_52") (pintype "output"))
    )
    (net (code "57") (name "D7_ISO") (class "Default")
      (node (ref "R48") (pin "1") (pinfunction "1_1") (pintype "passive"))
      (node (ref "U10") (pin "P6") (pinfunction "VID_P6") (pintype "input"))
    )
    (net (code "58") (name "D7_N") (class "Default")
      (node (ref "FMC_LPC") (pin "P$92") (pinfunction "LA05_N_P$92") (pintype "bidirectional"))
      (node (ref "U11") (pin "49") (pinfunction "B4Z_49") (pintype "output"))
    )
    (net (code "59") (name "D7_P") (class "Default")
      (node (ref "FMC_LPC") (pin "P$91") (pinfunction "LA05_P_P$91") (pintype "bidirectional"))
      (node (ref "U11") (pin "50") (pinfunction "B4Y_50") (pintype "output"))
    )
    (net (code "60") (name "D8_ISO") (class "Default")
      (node (ref "R47") (pin "1") (pinfunction "1_1") (pintype "passive"))
      (node (ref "U13") (pin "P3") (pinfunction "VIA_P3") (pintype "input"))
    )
    (net (code "61") (name "D8_N") (class "Default")
      (node (ref "FMC_LPC") (pin "P$11") (pinfunction "LA04_N_P$11") (pintype "bidirectional"))
      (node (ref "U11") (pin "47") (pinfunction "C1Z_47") (pintype "output"))
    )
    (net (code "62") (name "D8_P") (class "Default")
      (node (ref "FMC_LPC") (pin "P$10") (pinfunction "LA04_P_P$10") (pintype "bidirectional"))
      (node (ref "U11") (pin "48") (pinfunction "C1Y_48") (pintype "output"))
    )
    (net (code "63") (name "D9_ISO") (class "Default")
      (node (ref "R46") (pin "1") (pinfunction "1_1") (pintype "passive"))
      (node (ref "U13") (pin "P4") (pinfunction "VIB_P4") (pintype "input"))
    )
    (net (code "64") (name "D9_N") (class "Default")
      (node (ref "FMC_LPC") (pin "P$131") (pinfunction "LA06_N_P$131") (pintype "bidirectional"))
      (node (ref "U11") (pin "45") (pinfunction "C2Z_45") (pintype "output"))
    )
    (net (code "65") (name "D9_P") (class "Default")
      (node (ref "FMC_LPC") (pin "P$130") (pinfunction "LA06_P_P$130") (pintype "bidirectional"))
      (node (ref "U11") (pin "46") (pinfunction "C2Y_46") (pintype "output"))
    )
    (net (code "66") (name "D10_ISO") (class "Default")
      (node (ref "R45") (pin "1") (pinfunction "1_1") (pintype "passive"))
      (node (ref "U13") (pin "P5") (pinfunction "VIC_P5") (pintype "input"))
    )
    (net (code "67") (name "D10_N") (class "Default")
      (node (ref "FMC_LPC") (pin "P$50") (pinfunction "LA03_N_P$50") (pintype "bidirectional"))
      (node (ref "U11") (pin "43") (pinfunction "C3Z_43") (pintype "output"))
    )
    (net (code "68") (name "D10_P") (class "Default")
      (node (ref "FMC_LPC") (pin "P$49") (pinfunction "LA03_P_P$49") (pintype "bidirectional"))
      (node (ref "U11") (pin "44") (pinfunction "C3Y_44") (pintype "output"))
    )
    (net (code "69") (name "D11_ISO") (class "Default")
      (node (ref "R44") (pin "1") (pinfunction "1_1") (pintype "passive"))
      (node (ref "U13") (pin "P6") (pinfunction "VID_P6") (pintype "input"))
    )
    (net (code "70") (name "D11_N") (class "Default")
      (node (ref "FMC_LPC") (pin "P$8") (pinfunction "LA02_N_P$8") (pintype "bidirectional"))
      (node (ref "U11") (pin "41") (pinfunction "C4Z_41") (pintype "output"))
    )
    (net (code "71") (name "D11_P") (class "Default")
      (node (ref "FMC_LPC") (pin "P$7") (pinfunction "LA02_P_P$7") (pintype "bidirectional"))
      (node (ref "U11") (pin "42") (pinfunction "C4Y_42") (pintype "output"))
    )
    (net (code "72") (name "DES_GPIO0") (class "Default")
      (node (ref "U17") (pin "P6") (pinfunction "VID_P6") (pintype "input"))
      (node (ref "U8") (pin "23") (pinfunction "D2Y_23") (pintype "output"))
    )
    (net (code "73") (name "DES_GPIO0_ISO") (class "Default")
      (node (ref "R60") (pin "1") (pinfunction "1_1") (pintype "passive"))
      (node (ref "U17") (pin "P11") (pinfunction "VOD_P11") (pintype "output"))
    )
    (net (code "74") (name "DES_GPIO0_N") (class "Default")
      (node (ref "FMC_LPC") (pin "P$65") (pinfunction "LA22_N_P$65") (pintype "bidirectional"))
      (node (ref "U8") (pin "19") (pinfunction "D2B_19") (pintype "input"))
    )
    (net (code "75") (name "DES_GPIO0_P") (class "Default")
      (node (ref "FMC_LPC") (pin "P$64") (pinfunction "LA22_P_P$64") (pintype "bidirectional"))
      (node (ref "U8") (pin "18") (pinfunction "D2A_18") (pintype "input"))
    )
    (net (code "76") (name "DES_GPIO1") (class "Default")
      (node (ref "U17") (pin "P5") (pinfunction "VIC_P5") (pintype "input"))
      (node (ref "U8") (pin "24") (pinfunction "D1Y_24") (pintype "output"))
    )
    (net (code "77") (name "DES_GPIO1_ISO") (class "Default")
      (node (ref "R59") (pin "1") (pinfunction "1_1") (pintype "passive"))
      (node (ref "U17") (pin "P12") (pinfunction "VOC_P12") (pintype "output"))
    )
    (net (code "78") (name "DES_GPIO1_N") (class "Default")
      (node (ref "FMC_LPC") (pin "P$23") (pinfunction "LA19_N_P$23") (pintype "bidirectional"))
      (node (ref "U8") (pin "17") (pinfunction "D1B_17") (pintype "input"))
    )
    (net (code "79") (name "DES_GPIO1_P") (class "Default")
      (node (ref "FMC_LPC") (pin "P$22") (pinfunction "LA19_P_P$22") (pintype "bidirectional"))
      (node (ref "U8") (pin "16") (pinfunction "D1A_16") (pintype "input"))
    )
    (net (code "80") (name "DES_GPIO2") (class "Default")
      (node (ref "U17") (pin "P4") (pinfunction "VIB_P4") (pintype "input"))
      (node (ref "U8") (pin "26") (pinfunction "C2Y_26") (pintype "output"))
    )
    (net (code "81") (name "DES_GPIO2_ISO") (class "Default")
      (node (ref "R58") (pin "1") (pinfunction "1_1") (pintype "passive"))
      (node (ref "U17") (pin "P13") (pinfunction "VOB_P13") (pintype "output"))
    )
    (net (code "82") (name "DES_GPIO2_N") (class "Default")
      (node (ref "FMC_LPC") (pin "P$62") (pinfunction "LA20_N_P$62") (pintype "bidirectional"))
      (node (ref "U8") (pin "14") (pinfunction "C2B_14") (pintype "input"))
    )
    (net (code "83") (name "DES_GPIO2_P") (class "Default")
      (node (ref "FMC_LPC") (pin "P$61") (pinfunction "LA20_P_P$61") (pintype "bidirectional"))
      (node (ref "U8") (pin "13") (pinfunction "C2A_13") (pintype "input"))
    )
    (net (code "84") (name "DES_GPIO3") (class "Default")
      (node (ref "U17") (pin "P3") (pinfunction "VIA_P3") (pintype "input"))
      (node (ref "U8") (pin "27") (pinfunction "C1Y_27") (pintype "output"))
    )
    (net (code "85") (name "DES_GPIO3_ISO") (class "Default")
      (node (ref "R57") (pin "1") (pinfunction "1_1") (pintype "passive"))
      (node (ref "U17") (pin "P14") (pinfunction "VOA_P14") (pintype "output"))
    )
    (net (code "86") (name "DES_GPIO3_N") (class "Default")
      (node (ref "FMC_LPC") (pin "P$143") (pinfunction "LA18_N_CC_P$143") (pintype "bidirectional"))
      (node (ref "U8") (pin "12") (pinfunction "C1B_12") (pintype "input"))
    )
    (net (code "87") (name "DES_GPIO3_P") (class "Default")
      (node (ref "FMC_LPC") (pin "P$142") (pinfunction "LA18_P_CC_P$142") (pintype "bidirectional"))
      (node (ref "U8") (pin "11") (pinfunction "C1A_11") (pintype "input"))
    )
    (net (code "88") (name "DI0") (class "Default")
      (node (ref "TP2") (pin "TP") (pinfunction "TP_TP") (pintype "bidirectional"))
      (node (ref "U1") (pin "1") (pinfunction "OUT_1") (pintype "output"))
      (node (ref "U16") (pin "2") (pinfunction "1A_2") (pintype "input"))
    )
    (net (code "89") (name "DI0_N") (class "Default")
      (node (ref "FMC_LPC") (pin "P$68") (pinfunction "LA25_N_P$68") (pintype "bidirectional"))
      (node (ref "U16") (pin "15") (pinfunction "1Z_15") (pintype "output"))
    )
    (net (code "90") (name "DI0_P") (class "Default")
      (node (ref "FMC_LPC") (pin "P$67") (pinfunction "LA25_P_P$67") (pintype "bidirectional"))
      (node (ref "U16") (pin "16") (pinfunction "1Y_16") (pintype "output"))
    )
    (net (code "91") (name "DI0_TERM") (class "Default")
      (node (ref "R7") (pin "1") (pinfunction "1_1") (pintype "passive"))
      (node (ref "R8") (pin "1") (pinfunction "1_1") (pintype "passive"))
      (node (ref "U8") (pin "35") (pinfunction "A1Y_35") (pintype "output"))
    )
    (net (code "92") (name "DI0_TERM_N") (class "Default")
      (node (ref "FMC_LPC") (pin "P$139") (pinfunction "LA1N_N_P$139") (pintype "bidirectional"))
      (node (ref "U8") (pin "2") (pinfunction "A1B_2") (pintype "input"))
    )
    (net (code "93") (name "DI0_TERM_P") (class "Default")
      (node (ref "FMC_LPC") (pin "P$138") (pinfunction "LA14_P_P$138") (pintype "bidirectional"))
      (node (ref "U8") (pin "1") (pinfunction "A1A_1") (pintype "input"))
    )
    (net (code "94") (name "DI1") (class "Default")
      (node (ref "TP1") (pin "TP") (pinfunction "TP_TP") (pintype "bidirectional"))
      (node (ref "U16") (pin "3") (pinfunction "2A_3") (pintype "input"))
      (node (ref "U2") (pin "1") (pinfunction "OUT_1") (pintype "output"))
    )
    (net (code "95") (name "DI1_N") (class "Default")
      (node (ref "FMC_LPC") (pin "P$29") (pinfunction "LA24_N_P$29") (pintype "bidirectional"))
      (node (ref "U16") (pin "13") (pinfunction "2Z_13") (pintype "output"))
    )
    (net (code "96") (name "DI1_P") (class "Default")
      (node (ref "FMC_LPC") (pin "P$28") (pinfunction "LA24_P_P$28") (pintype "bidirectional"))
      (node (ref "U16") (pin "14") (pinfunction "2Y_14") (pintype "output"))
    )
    (net (code "97") (name "DI1_TERM") (class "Default")
      (node (ref "R16") (pin "1") (pinfunction "1_1") (pintype "passive"))
      (node (ref "R17") (pin "1") (pinfunction "1_1") (pintype "passive"))
      (node (ref "U8") (pin "34") (pinfunction "A2Y_34") (pintype "output"))
    )
    (net (code "98") (name "DI1_TERM_N") (class "Default")
      (node (ref "FMC_LPC") (pin "P$59") (pinfunction "LA16_N_P$59") (pintype "bidirectional"))
      (node (ref "U8") (pin "4") (pinfunction "A2B_4") (pintype "input"))
    )
    (net (code "99") (name "DI1_TERM_P") (class "Default")
      (node (ref "FMC_LPC") (pin "P$58") (pinfunction "LA16_P_P$58") (pintype "bidirectional"))
      (node (ref "U8") (pin "3") (pinfunction "A2A_3") (pintype "input"))
    )
    (net (code "100") (name "DO0") (class "Default")
      (node (ref "U3") (pin "2") (pinfunction "1A_2") (pintype "input"))
      (node (ref "U3") (pin "5") (pinfunction "2A_5") (pintype "input"))
      (node (ref "U8") (pin "31") (pinfunction "B2Y_31") (pintype "output"))
    )
    (net (code "101") (name "DO0_N") (class "Default")
      (node (ref "FMC_LPC") (pin "P$101") (pinfunction "LA17_N_CC_P$101") (pintype "bidirectional"))
      (node (ref "U8") (pin "9") (pinfunction "B2B_9") (pintype "input"))
    )
    (net (code "102") (name "DO0_P") (class "Default")
      (node (ref "FMC_LPC") (pin "P$100") (pinfunction "LA17_P_CC_P$100") (pintype "bidirectional"))
      (node (ref "U8") (pin "8") (pinfunction "B2A_8") (pintype "input"))
    )
    (net (code "103") (name "DO1") (class "Default")
      (node (ref "U3") (pin "12") (pinfunction "4A_12") (pintype "input"))
      (node (ref "U3") (pin "9") (pinfunction "3A_9") (pintype "input"))
      (node (ref "U8") (pin "32") (pinfunction "B1Y_32") (pintype "output"))
    )
    (net (code "104") (name "DO1_N") (class "Default")
      (node (ref "FMC_LPC") (pin "P$20") (pinfunction "LA15_N_P$20") (pintype "bidirectional"))
      (node (ref "U8") (pin "7") (pinfunction "B1B_7") (pintype "input"))
    )
    (net (code "105") (name "DO1_P") (class "Default")
      (node (ref "FMC_LPC") (pin "P$19") (pinfunction "LA15_P_P$19") (pintype "bidirectional"))
      (node (ref "U8") (pin "6") (pinfunction "B1A_6") (pintype "input"))
    )
    (net (code "106") (name "GND") (class "Default")
      (node (ref "C1") (pin "2") (pinfunction "2_2") (pintype "passive"))
      (node (ref "C10") (pin "1") (pinfunction "1_1") (pintype "passive"))
      (node (ref "C11") (pin "-") (pinfunction "-_-") (pintype "passive"))
      (node (ref "C12") (pin "1") (pinfunction "1_1") (pintype "passive"))
      (node (ref "C13") (pin "1") (pinfunction "1_1") (pintype "passive"))
      (node (ref "C14") (pin "1") (pinfunction "1_1") (pintype "passive"))
      (node (ref "C15") (pin "1") (pinfunction "1_1") (pintype "passive"))
      (node (ref "C16") (pin "1") (pinfunction "1_1") (pintype "passive"))
      (node (ref "C18") (pin "1") (pinfunction "1_1") (pintype "passive"))
      (node (ref "C2") (pin "2") (pinfunction "2_2") (pintype "passive"))
      (node (ref "C21") (pin "-") (pinfunction "-_-") (pintype "passive"))
      (node (ref "C25") (pin "1") (pinfunction "1_1") (pintype "passive"))
      (node (ref "C26") (pin "1") (pinfunction "1_1") (pintype "passive"))
      (node (ref "C27") (pin "1") (pinfunction "1_1") (pintype "passive"))
      (node (ref "C28") (pin "1") (pinfunction "1_1") (pintype "passive"))
      (node (ref "C3") (pin "2") (pinfunction "2_2") (pintype "passive"))
      (node (ref "C33") (pin "1") (pinfunction "1_1") (pintype "passive"))
      (node (ref "C4") (pin "2") (pinfunction "2_2") (pintype "passive"))
      (node (ref "C42") (pin "1") (pinfunction "1_1") (pintype "passive"))
      (node (ref "C43") (pin "1") (pinfunction "1_1") (pintype "passive"))
      (node (ref "C44") (pin "1") (pinfunction "1_1") (pintype "passive"))
      (node (ref "C45") (pin "1") (pinfunction "1_1") (pintype "passive"))
      (node (ref "C46") (pin "1") (pinfunction "1_1") (pintype "passive"))
      (node (ref "C47") (pin "1") (pinfunction "1_1") (pintype "passive"))
      (node (ref "C49") (pin "1") (pinfunction "1_1") (pintype "passive"))
      (node (ref "C5") (pin "-") (pinfunction "-_-") (pintype "passive"))
      (node (ref "C6") (pin "1") (pinfunction "1_1") (pintype "passive"))
      (node (ref "C60") (pin "1") (pinfunction "1_1") (pintype "passive"))
      (node (ref "C63") (pin "1") (pinfunction "1_1") (pintype "passive"))
      (node (ref "C7") (pin "1") (pinfunction "1_1") (pintype "passive"))
      (node (ref "C71") (pin "1") (pinfunction "1_1") (pintype "passive"))
      (node (ref "C72") (pin "1") (pinfunction "1_1") (pintype "passive"))
      (node (ref "C73") (pin "1") (pinfunction "1_1") (pintype "passive"))
      (node (ref "C74") (pin "1") (pinfunction "1_1") (pintype "passive"))
      (node (ref "C75") (pin "1") (pinfunction "1_1") (pintype "passive"))
      (node (ref "C8") (pin "-") (pinfunction "-_-") (pintype "passive"))
      (node (ref "C81") (pin "1") (pinfunction "1_1") (pintype "passive"))
      (node (ref "C82") (pin "1") (pinfunction "1_1") (pintype "passive"))
      (node (ref "C9") (pin "1") (pinfunction "1_1") (pintype "passive"))
      (node (ref "D1") (pin "1") (pinfunction "A_1") (pintype "passive"))
      (node (ref "D2") (pin "1") (pinfunction "A_1") (pintype "passive"))
      (node (ref "D3") (pin "1") (pinfunction "A_1") (pintype "passive"))
      (node (ref "D4") (pin "1") (pinfunction "A_1") (pintype "passive"))
      (node (ref "D5") (pin "2") (pinfunction "A_2") (pintype "passive"))
      (node (ref "D6") (pin "A") (pinfunction "A_A") (pintype "passive"))
      (node (ref "DI0") (pin "GND$1") (pinfunction "2_GND$1") (pintype "passive"))
      (node (ref "DI0") (pin "GND$2") (pinfunction "2_GND$2") (pintype "passive"))
      (node (ref "DI0") (pin "GND$3") (pinfunction "2_GND$3") (pintype "passive"))
      (node (ref "DI0") (pin "GND$4") (pinfunction "2_GND$4") (pintype "passive"))
      (node (ref "DI1") (pin "GND$1") (pinfunction "2_GND$1") (pintype "passive"))
      (node (ref "DI1") (pin "GND$2") (pinfunction "2_GND$2") (pintype "passive"))
      (node (ref "DI1") (pin "GND$3") (pinfunction "2_GND$3") (pintype "passive"))
      (node (ref "DI1") (pin "GND$4") (pinfunction "2_GND$4") (pintype "passive"))
      (node (ref "DO0") (pin "GND$1") (pinfunction "2_GND$1") (pintype "passive"))
      (node (ref "DO0") (pin "GND$2") (pinfunction "2_GND$2") (pintype "passive"))
      (node (ref "DO0") (pin "GND$3") (pinfunction "2_GND$3") (pintype "passive"))
      (node (ref "DO0") (pin "GND$4") (pinfunction "2_GND$4") (pintype "passive"))
      (node (ref "DO1") (pin "GND$1") (pinfunction "2_GND$1") (pintype "passive"))
      (node (ref "DO1") (pin "GND$2") (pinfunction "2_GND$2") (pintype "passive"))
      (node (ref "DO1") (pin "GND$3") (pinfunction "2_GND$3") (pintype "passive"))
      (node (ref "DO1") (pin "GND$4") (pinfunction "2_GND$4") (pintype "passive"))
      (node (ref "FMC_LPC") (pin "P$102") (pinfunction "GND_P$102") (pintype "power_in"))
      (node (ref "FMC_LPC") (pin "P$105") (pinfunction "GND_P$105") (pintype "power_in"))
      (node (ref "FMC_LPC") (pin "P$108") (pinfunction "GND_P$108") (pintype "power_in"))
      (node (ref "FMC_LPC") (pin "P$117") (pinfunction "GND_P$117") (pintype "power_in"))
      (node (ref "FMC_LPC") (pin "P$119") (pinfunction "GND_P$119") (pintype "power_in"))
      (node (ref "FMC_LPC") (pin "P$12") (pinfunction "GND_P$12") (pintype "power_in"))
      (node (ref "FMC_LPC") (pin "P$121") (pinfunction "GND_P$121") (pintype "power_in"))
      (node (ref "FMC_LPC") (pin "P$124") (pinfunction "GND_P$124") (pintype "power_in"))
      (node (ref "FMC_LPC") (pin "P$125") (pinfunction "GND_P$125") (pintype "power_in"))
      (node (ref "FMC_LPC") (pin "P$128") (pinfunction "GND_P$128") (pintype "power_in"))
      (node (ref "FMC_LPC") (pin "P$129") (pinfunction "GND_P$129") (pintype "power_in"))
      (node (ref "FMC_LPC") (pin "P$132") (pinfunction "GND_P$132") (pintype "power_in"))
      (node (ref "FMC_LPC") (pin "P$133") (pinfunction "GND_P$133") (pintype "power_in"))
      (node (ref "FMC_LPC") (pin "P$136") (pinfunction "GND_P$136") (pintype "power_in"))
      (node (ref "FMC_LPC") (pin "P$137") (pinfunction "GND_P$137") (pintype "power_in"))
      (node (ref "FMC_LPC") (pin "P$140") (pinfunction "GND_P$140") (pintype "power_in"))
      (node (ref "FMC_LPC") (pin "P$141") (pinfunction "GND_P$141") (pintype "power_in"))
      (node (ref "FMC_LPC") (pin "P$144") (pinfunction "GND_P$144") (pintype "power_in"))
      (node (ref "FMC_LPC") (pin "P$145") (pinfunction "GND_P$145") (pintype "power_in"))
      (node (ref "FMC_LPC") (pin "P$148") (pinfunction "GND_P$148") (pintype "power_in"))
      (node (ref "FMC_LPC") (pin "P$149") (pinfunction "GND_P$149") (pintype "power_in"))
      (node (ref "FMC_LPC") (pin "P$15") (pinfunction "GND_P$15") (pintype "power_in"))
      (node (ref "FMC_LPC") (pin "P$152") (pinfunction "GND_P$152") (pintype "power_in"))
      (node (ref "FMC_LPC") (pin "P$153") (pinfunction "GND_P$153") (pintype "power_in"))
      (node (ref "FMC_LPC") (pin "P$156") (pinfunction "GND_P$156") (pintype "power_in"))
      (node (ref "FMC_LPC") (pin "P$158") (pinfunction "GND19_P$158") (pintype "bidirectional"))
      (node (ref "FMC_LPC") (pin "P$160") (pinfunction "GND_P$160") (pintype "power_in"))
      (node (ref "FMC_LPC") (pin "P$18") (pinfunction "GND_P$18") (pintype "power_in"))
      (node (ref "FMC_LPC") (pin "P$21") (pinfunction "GND_P$21") (pintype "power_in"))
      (node (ref "FMC_LPC") (pin "P$24") (pinfunction "GND_P$24") (pintype "power_in"))
      (node (ref "FMC_LPC") (pin "P$27") (pinfunction "GND_P$27") (pintype "power_in"))
      (node (ref "FMC_LPC") (pin "P$3") (pinfunction "GND_P$3") (pintype "power_in"))
      (node (ref "FMC_LPC") (pin "P$30") (pinfunction "GND_P$30") (pintype "power_in"))
      (node (ref "FMC_LPC") (pin "P$33") (pinfunction "GND_P$33") (pintype "power_in"))
      (node (ref "FMC_LPC") (pin "P$36") (pinfunction "GND_P$36") (pintype "power_in"))
      (node (ref "FMC_LPC") (pin "P$39") (pinfunction "GND_P$39") (pintype "power_in"))
      (node (ref "FMC_LPC") (pin "P$41") (pinfunction "GND_P$41") (pintype "power_in"))
      (node (ref "FMC_LPC") (pin "P$44") (pinfunction "GND_P$44") (pintype "power_in"))
      (node (ref "FMC_LPC") (pin "P$45") (pinfunction "GND_P$45") (pintype "power_in"))
      (node (ref "FMC_LPC") (pin "P$48") (pinfunction "GND_P$48") (pintype "power_in"))
      (node (ref "FMC_LPC") (pin "P$51") (pinfunction "GND_P$51") (pintype "power_in"))
      (node (ref "FMC_LPC") (pin "P$54") (pinfunction "GND_P$54") (pintype "power_in"))
      (node (ref "FMC_LPC") (pin "P$57") (pinfunction "GND_P$57") (pintype "power_in"))
      (node (ref "FMC_LPC") (pin "P$6") (pinfunction "GND_P$6") (pintype "power_in"))
      (node (ref "FMC_LPC") (pin "P$60") (pinfunction "GND_P$60") (pintype "power_in"))
      (node (ref "FMC_LPC") (pin "P$63") (pinfunction "GND42_P$63") (pintype "bidirectional"))
      (node (ref "FMC_LPC") (pin "P$66") (pinfunction "GND_P$66") (pintype "power_in"))
      (node (ref "FMC_LPC") (pin "P$69") (pinfunction "GND_P$69") (pintype "power_in"))
      (node (ref "FMC_LPC") (pin "P$72") (pinfunction "GND_P$72") (pintype "power_in"))
      (node (ref "FMC_LPC") (pin "P$75") (pinfunction "GND_P$75") (pintype "power_in"))
      (node (ref "FMC_LPC") (pin "P$78") (pinfunction "GND_P$78") (pintype "power_in"))
      (node (ref "FMC_LPC") (pin "P$80") (pinfunction "GND_P$80") (pintype "power_in"))
      (node (ref "FMC_LPC") (pin "P$82") (pinfunction "GND_P$82") (pintype "power_in"))
      (node (ref "FMC_LPC") (pin "P$83") (pinfunction "GND_P$83") (pintype "power_in"))
      (node (ref "FMC_LPC") (pin "P$86") (pinfunction "GND_P$86") (pintype "power_in"))
      (node (ref "FMC_LPC") (pin "P$87") (pinfunction "GND_P$87") (pintype "power_in"))
      (node (ref "FMC_LPC") (pin "P$9") (pinfunction "GND_P$9") (pintype "power_in"))
      (node (ref "FMC_LPC") (pin "P$90") (pinfunction "GND_P$90") (pintype "power_in"))
      (node (ref "FMC_LPC") (pin "P$93") (pinfunction "GND_P$93") (pintype "power_in"))
      (node (ref "FMC_LPC") (pin "P$96") (pinfunction "GND_P$96") (pintype "power_in"))
      (node (ref "FMC_LPC") (pin "P$99") (pinfunction "GND_P$99") (pintype "power_in"))
      (node (ref "J3") (pin "1") (pinfunction "1_1") (pintype "bidirectional"))
      (node (ref "J3") (pin "4") (pinfunction "4_4") (pintype "bidirectional"))
      (node (ref "J6") (pin "G1") (pinfunction "2_G1") (pintype "passive"))
      (node (ref "J6") (pin "G2") (pinfunction "2_G2") (pintype "passive"))
      (node (ref "J6") (pin "G3") (pinfunction "2_G3") (pintype "passive"))
      (node (ref "J6") (pin "G4") (pinfunction "2_G4") (pintype "passive"))
      (node (ref "J8") (pin "G1") (pinfunction "2_G1") (pintype "passive"))
      (node (ref "J8") (pin "G2") (pinfunction "2_G2") (pintype "passive"))
      (node (ref "J8") (pin "G3") (pinfunction "2_G3") (pintype "passive"))
      (node (ref "J8") (pin "G4") (pinfunction "2_G4") (pintype "passive"))
      (node (ref "PCIE-PWR") (pin "4") (pinfunction "4_4") (pintype "passive"))
      (node (ref "PCIE-PWR") (pin "5") (pinfunction "5_5") (pintype "passive"))
      (node (ref "PCIE-PWR") (pin "6") (pinfunction "6_6") (pintype "passive"))
      (node (ref "Q1") (pin "S") (pinfunction "S_S") (pintype "bidirectional"))
      (node (ref "Q2") (pin "S") (pinfunction "S_S") (pintype "bidirectional"))
      (node (ref "Q3") (pin "S") (pinfunction "S_S") (pintype "bidirectional"))
      (node (ref "Q4") (pin "S") (pinfunction "S_S") (pintype "bidirectional"))
      (node (ref "R11") (pin "1") (pinfunction "1_1") (pintype "passive"))
      (node (ref "R18") (pin "1") (pinfunction "1_1") (pintype "passive"))
      (node (ref "R2") (pin "1") (pinfunction "1_1") (pintype "passive"))
      (node (ref "R23") (pin "1") (pinfunction "1_1") (pintype "passive"))
      (node (ref "R29") (pin "1") (pinfunction "1_1") (pintype "passive"))
      (node (ref "R81") (pin "2") (pinfunction "2_2") (pintype "passive"))
      (node (ref "R9") (pin "1") (pinfunction "1_1") (pintype "passive"))
      (node (ref "TERM") (pin "C1") (pinfunction "C_C1") (pintype "passive"))
      (node (ref "TERM") (pin "C2") (pinfunction "C_C2") (pintype "passive"))
      (node (ref "TP18") (pin "1") (pinfunction "TP_1") (pintype "bidirectional"))
      (node (ref "TP3") (pin "1") (pinfunction "TP_1") (pintype "bidirectional"))
      (node (ref "TP4") (pin "1") (pinfunction "TP_1") (pintype "bidirectional"))
      (node (ref "TP5") (pin "1") (pinfunction "TP_1") (pintype "bidirectional"))
      (node (ref "TP6") (pin "1") (pinfunction "TP_1") (pintype "bidirectional"))
      (node (ref "TP7") (pin "1") (pinfunction "TP_1") (pintype "bidirectional"))
      (node (ref "TP8") (pin "1") (pinfunction "TP_1") (pintype "bidirectional"))
      (node (ref "TP9") (pin "1") (pinfunction "TP_1") (pintype "bidirectional"))
      (node (ref "U1") (pin "2") (pinfunction "V-_2") (pintype "power_in"))
      (node (ref "U10") (pin "P15") (pinfunction "GND2_P15") (pintype "power_in"))
      (node (ref "U10") (pin "P9") (pinfunction "GND2_P9") (pintype "power_in"))
      (node (ref "U11") (pin "1") (pinfunction "GND_1") (pintype "power_in"))
      (node (ref "U11") (pin "15") (pinfunction "GND_15") (pintype "power_in"))
      (node (ref "U11") (pin "18") (pinfunction "GND_18") (pintype "power_in"))
      (node (ref "U11") (pin "29") (pinfunction "GND_29") (pintype "power_in"))
      (node (ref "U11") (pin "32") (pinfunction "GND_32") (pintype "power_in"))
      (node (ref "U11") (pin "4") (pinfunction "GND_4") (pintype "power_in"))
      (node (ref "U13") (pin "P15") (pinfunction "GND2_P15") (pintype "power_in"))
      (node (ref "U13") (pin "P9") (pinfunction "GND2_P9") (pintype "power_in"))
      (node (ref "U14") (pin "P15") (pinfunction "GND2_P15") (pintype "power_in"))
      (node (ref "U14") (pin "P9") (pinfunction "GND2_P9") (pintype "power_in"))
      (node (ref "U16") (pin "5") (pinfunction "GND_5") (pintype "power_in"))
      (node (ref "U17") (pin "P2") (pinfunction "GND1_P2") (pintype "power_in"))
      (node (ref "U17") (pin "P8") (pinfunction "GND1_P8") (pintype "power_in"))
      (node (ref "U18") (pin "P15") (pinfunction "GND2_P15") (pintype "power_in"))
      (node (ref "U18") (pin "P9") (pinfunction "GND2_P9") (pintype "power_in"))
      (node (ref "U2") (pin "2") (pinfunction "V-_2") (pintype "power_in"))
      (node (ref "U3") (pin "7") (pinfunction "GND_7") (pintype "passive"))
      (node (ref "U4") (pin "5") (pinfunction "AVSS_5") (pintype "power_in"))
      (node (ref "U4") (pin "6") (pinfunction "LAT/HVC_6") (pintype "input"))
      (node (ref "U5") (pin "4") (pinfunction "GND1_4") (pintype "power_in"))
      (node (ref "U6") (pin "2") (pinfunction "GND_2") (pintype "power_in"))
      (node (ref "U8") (pin "10") (pinfunction "AGND_10") (pintype "power_in"))
      (node (ref "U8") (pin "15") (pinfunction "AGND_15") (pintype "power_in"))
      (node (ref "U8") (pin "20") (pinfunction "GND_20") (pintype "power_in"))
      (node (ref "U8") (pin "28") (pinfunction "DGND_28") (pintype "power_in"))
      (node (ref "U8") (pin "30") (pinfunction "DGND_30") (pintype "power_in"))
      (node (ref "U8") (pin "38") (pinfunction "GND_38") (pintype "power_in"))
      (node (ref "U8") (pin "5") (pinfunction "AGND_5") (pintype "power_in"))
      (node (ref "U9") (pin "P15") (pinfunction "GND2_P15") (pintype "power_in"))
      (node (ref "U9") (pin "P9") (pinfunction "GND2_P9") (pintype "power_in"))
    )
    (net (code "107") (name "GND_ISO") (class "Default")
      (node (ref "C17") (pin "1") (pinfunction "1_1") (pintype "passive"))
      (node (ref "C19") (pin "1") (pinfunction "1_1") (pintype "passive"))
      (node (ref "C20") (pin "1") (pinfunction "1_1") (pintype "passive"))
      (node (ref "C22") (pin "1") (pinfunction "1_1") (pintype "passive"))
      (node (ref "C23") (pin "-") (pinfunction "-_-") (pintype "passive"))
      (node (ref "C24") (pin "-") (pinfunction "-_-") (pintype "passive"))
      (node (ref "C29") (pin "1") (pinfunction "1_1") (pintype "passive"))
      (node (ref "C30") (pin "1") (pinfunction "1_1") (pintype "passive"))
      (node (ref "C31") (pin "1") (pinfunction "1_1") (pintype "passive"))
      (node (ref "C32") (pin "1") (pinfunction "1_1") (pintype "passive"))
      (node (ref "C34") (pin "1") (pinfunction "1_1") (pintype "passive"))
      (node (ref "C35") (pin "1") (pinfunction "1_1") (pintype "passive"))
      (node (ref "C36") (pin "1") (pinfunction "1_1") (pintype "passive"))
      (node (ref "C37") (pin "1") (pinfunction "1_1") (pintype "passive"))
      (node (ref "C38") (pin "1") (pinfunction "1_1") (pintype "passive"))
      (node (ref "C39") (pin "1") (pinfunction "1_1") (pintype "passive"))
      (node (ref "C40") (pin "1") (pinfunction "1_1") (pintype "passive"))
      (node (ref "C41") (pin "1") (pinfunction "1_1") (pintype "passive"))
      (node (ref "C48") (pin "1") (pinfunction "1_1") (pintype "passive"))
      (node (ref "C50") (pin "1") (pinfunction "1_1") (pintype "passive"))
      (node (ref "C51") (pin "1") (pinfunction "1_1") (pintype "passive"))
      (node (ref "C52") (pin "1") (pinfunction "1_1") (pintype "passive"))
      (node (ref "C53") (pin "1") (pinfunction "1_1") (pintype "passive"))
      (node (ref "C54") (pin "1") (pinfunction "1_1") (pintype "passive"))
      (node (ref "C55") (pin "1") (pinfunction "1_1") (pintype "passive"))
      (node (ref "C56") (pin "1") (pinfunction "1_1") (pintype "passive"))
      (node (ref "C59") (pin "1") (pinfunction "1_1") (pintype "passive"))
      (node (ref "C61") (pin "1") (pinfunction "1_1") (pintype "passive"))
      (node (ref "C62") (pin "1") (pinfunction "1_1") (pintype "passive"))
      (node (ref "C64") (pin "1") (pinfunction "1_1") (pintype "passive"))
      (node (ref "C65") (pin "1") (pinfunction "1_1") (pintype "passive"))
      (node (ref "C66") (pin "1") (pinfunction "1_1") (pintype "passive"))
      (node (ref "C67") (pin "1") (pinfunction "1_1") (pintype "passive"))
      (node (ref "C68") (pin "1") (pinfunction "1_1") (pintype "passive"))
      (node (ref "C69") (pin "1") (pinfunction "1_1") (pintype "passive"))
      (node (ref "C70") (pin "1") (pinfunction "1_1") (pintype "passive"))
      (node (ref "C76") (pin "2") (pinfunction "2_2") (pintype "passive"))
      (node (ref "C77") (pin "2") (pinfunction "2_2") (pintype "passive"))
      (node (ref "C78") (pin "1") (pinfunction "1_1") (pintype "passive"))
      (node (ref "C79") (pin "1") (pinfunction "1_1") (pintype "passive"))
      (node (ref "C80") (pin "1") (pinfunction "1_1") (pintype "passive"))
      (node (ref "C82") (pin "2") (pinfunction "2_2") (pintype "passive"))
      (node (ref "D7") (pin "A") (pinfunction "A_A") (pintype "passive"))
      (node (ref "J4") (pin "1") (pinfunction "1_1") (pintype "passive"))
      (node (ref "J4") (pin "4") (pinfunction "4_4") (pintype "passive"))
      (node (ref "J5") (pin "G1") (pinfunction "2_G1") (pintype "passive"))
      (node (ref "J5") (pin "G2") (pinfunction "2_G2") (pintype "passive"))
      (node (ref "J5") (pin "G3") (pinfunction "2_G3") (pintype "passive"))
      (node (ref "J5") (pin "G4") (pinfunction "2_G4") (pintype "passive"))
      (node (ref "J7") (pin "G1") (pinfunction "2_G1") (pintype "passive"))
      (node (ref "J7") (pin "G2") (pinfunction "2_G2") (pintype "passive"))
      (node (ref "J7") (pin "G3") (pinfunction "2_G3") (pintype "passive"))
      (node (ref "J7") (pin "G4") (pinfunction "2_G4") (pintype "passive"))
      (node (ref "LINK") (pin "GND$1") (pinfunction "2_GND$1") (pintype "passive"))
      (node (ref "LINK") (pin "GND$2") (pinfunction "2_GND$2") (pintype "passive"))
      (node (ref "LINK") (pin "GND$3") (pinfunction "2_GND$3") (pintype "passive"))
      (node (ref "LINK") (pin "GND$4") (pinfunction "2_GND$4") (pintype "passive"))
      (node (ref "PWR/LOCK") (pin "C1") (pinfunction "C_C1") (pintype "passive"))
      (node (ref "Q5") (pin "S") (pinfunction "S_S") (pintype "bidirectional"))
      (node (ref "Q6") (pin "S") (pinfunction "S_S") (pintype "bidirectional"))
      (node (ref "R35") (pin "2") (pinfunction "2_2") (pintype "passive"))
      (node (ref "R37") (pin "2") (pinfunction "2_2") (pintype "passive"))
      (node (ref "R38") (pin "2") (pinfunction "2_2") (pintype "passive"))
      (node (ref "R39") (pin "2") (pinfunction "2_2") (pintype "passive"))
      (node (ref "R42") (pin "2") (pinfunction "2_2") (pintype "passive"))
      (node (ref "R67") (pin "1") (pinfunction "1_1") (pintype "passive"))
      (node (ref "R69") (pin "1") (pinfunction "1_1") (pintype "passive"))
      (node (ref "R75") (pin "2") (pinfunction "2_2") (pintype "passive"))
      (node (ref "R76") (pin "2") (pinfunction "2_2") (pintype "passive"))
      (node (ref "R77") (pin "2") (pinfunction "2_2") (pintype "passive"))
      (node (ref "R83") (pin "1") (pinfunction "1_1") (pintype "passive"))
      (node (ref "S1") (pin "A") (pinfunction "P_A") (pintype "passive"))
      (node (ref "TP17") (pin "1") (pinfunction "TP_1") (pintype "bidirectional"))
      (node (ref "TP21") (pin "1") (pinfunction "TP_1") (pintype "bidirectional"))
      (node (ref "TP25") (pin "1") (pinfunction "TP_1") (pintype "bidirectional"))
      (node (ref "TP26") (pin "1") (pinfunction "TP_1") (pintype "bidirectional"))
      (node (ref "U10") (pin "P2") (pinfunction "GND1_P2") (pintype "power_in"))
      (node (ref "U10") (pin "P8") (pinfunction "GND1_P8") (pintype "power_in"))
      (node (ref "U12") (pin "43") (pinfunction "RES_43") (pintype "input"))
      (node (ref "U12") (pin "44") (pinfunction "TESTEN_44") (pintype "input"))
      (node (ref "U12") (pin "49") (pinfunction "DAP_49") (pintype "input"))
      (node (ref "U13") (pin "P2") (pinfunction "GND1_P2") (pintype "power_in"))
      (node (ref "U13") (pin "P8") (pinfunction "GND1_P8") (pintype "power_in"))
      (node (ref "U14") (pin "P2") (pinfunction "GND1_P2") (pintype "power_in"))
      (node (ref "U14") (pin "P8") (pinfunction "GND1_P8") (pintype "power_in"))
      (node (ref "U15") (pin "5") (pinfunction "5_5") (pintype "passive"))
      (node (ref "U15") (pin "6") (pinfunction "6_6") (pintype "passive"))
      (node (ref "U15") (pin "7") (pinfunction "7_7") (pintype "passive"))
      (node (ref "U15") (pin "8") (pinfunction "8_8") (pintype "passive"))
      (node (ref "U17") (pin "P15") (pinfunction "GND2_P15") (pintype "power_in"))
      (node (ref "U17") (pin "P9") (pinfunction "GND2_P9") (pintype "power_in"))
      (node (ref "U18") (pin "P2") (pinfunction "GND1_P2") (pintype "power_in"))
      (node (ref "U18") (pin "P8") (pinfunction "GND1_P8") (pintype "power_in"))
      (node (ref "U5") (pin "5") (pinfunction "GND2_5") (pintype "power_in"))
      (node (ref "U6") (pin "5") (pinfunction "-VO_5") (pintype "power_in"))
      (node (ref "U7") (pin "B5") (pinfunction "GND_B5") (pintype "power_in"))
      (node (ref "U7") (pin "C1") (pinfunction "GND_C1") (pintype "power_in"))
      (node (ref "U7") (pin "C2") (pinfunction "GND_C2") (pintype "power_in"))
      (node (ref "U7") (pin "C5") (pinfunction "SYNC/MODE_C5") (pintype "input"))
      (node (ref "U7") (pin "D5") (pinfunction "GND_D5") (pintype "power_in"))
      (node (ref "U9") (pin "P2") (pinfunction "GND1_P2") (pintype "power_in"))
      (node (ref "U9") (pin "P8") (pinfunction "GND1_P8") (pintype "power_in"))
    )
    (net (code "108") (name "GPI0_N") (class "Default")
      (node (ref "FMC_LPC") (pin "P$26") (pinfunction "LA21_N_P$26") (pintype "bidirectional"))
      (node (ref "U16") (pin "9") (pinfunction "4Z_9") (pintype "output"))
    )
    (net (code "109") (name "GPI0_P") (class "Default")
      (node (ref "FMC_LPC") (pin "P$25") (pinfunction "LA21_P_P$25") (pintype "bidirectional"))
      (node (ref "U16") (pin "10") (pinfunction "4Y_10") (pintype "output"))
    )
    (net (code "110") (name "GPI1_N") (class "Default")
      (node (ref "FMC_LPC") (pin "P$104") (pinfunction "LA23_N_P$104") (pintype "bidirectional"))
      (node (ref "U16") (pin "11") (pinfunction "3Z_11") (pintype "output"))
    )
    (net (code "111") (name "GPI1_P") (class "Default")
      (node (ref "FMC_LPC") (pin "P$103") (pinfunction "LA23_P_P$103") (pintype "bidirectional"))
      (node (ref "U16") (pin "12") (pinfunction "3Y_12") (pintype "output"))
    )
    (net (code "112") (name "HSYNC_ISO") (class "Default")
      (node (ref "R43") (pin "1") (pinfunction "1_1") (pintype "passive"))
      (node (ref "U14") (pin "P3") (pinfunction "VIA_P3") (pintype "input"))
    )
    (net (code "113") (name "HSYNC_N") (class "Default")
      (node (ref "FMC_LPC") (pin "P$89") (pinfunction "LA01_N_CC_P$89") (pintype "bidirectional"))
      (node (ref "U11") (pin "39") (pinfunction "D1Z_39") (pintype "output"))
    )
    (net (code "114") (name "HSYNC_P") (class "Default")
      (node (ref "FMC_LPC") (pin "P$88") (pinfunction "LA01_P_CC_P$88") (pintype "bidirectional"))
      (node (ref "U11") (pin "40") (pinfunction "D1Y_40") (pintype "output"))
    )
    (net (code "115") (name "IDX0") (class "Default")
      (node (ref "R72") (pin "2") (pinfunction "2_2") (pintype "passive"))
      (node (ref "R75") (pin "1") (pinfunction "1_1") (pintype "passive"))
      (node (ref "U12") (pin "35") (pinfunction "IDX0_35") (pintype "input"))
    )
    (net (code "116") (name "IDX1") (class "Default")
      (node (ref "R73") (pin "2") (pinfunction "2_2") (pintype "passive"))
      (node (ref "R76") (pin "1") (pinfunction "1_1") (pintype "passive"))
      (node (ref "U12") (pin "34") (pinfunction "IDX1_34") (pintype "input"))
    )
    (net (code "117") (name "INTVCC") (class "Default")
      (node (ref "R34") (pin "1") (pinfunction "1_1") (pintype "passive"))
      (node (ref "U7") (pin "C3") (pinfunction "INTVCC_C3") (pintype "power_in"))
    )
    (net (code "118") (name "LOCK") (class "Default")
      (node (ref "U16") (pin "6") (pinfunction "3A_6") (pintype "input"))
      (node (ref "U18") (pin "P14") (pinfunction "VOA_P14") (pintype "output"))
    )
    (net (code "119") (name "LOCK_ISO") (class "Default")
      (node (ref "R68") (pin "2") (pinfunction "2_2") (pintype "passive"))
      (node (ref "U12") (pin "48") (pinfunction "LOCK_48") (pintype "input"))
      (node (ref "U18") (pin "P3") (pinfunction "VIA_P3") (pintype "input"))
    )
    (net (code "120") (name "MODE") (class "Default")
      (node (ref "R74") (pin "2") (pinfunction "2_2") (pintype "passive"))
      (node (ref "R77") (pin "1") (pinfunction "1_1") (pintype "passive"))
      (node (ref "U12") (pin "37") (pinfunction "MODE_37") (pintype "input"))
    )
    (net (code "121") (name "Net-(C58-Pad2)") (class "Default")
      (node (ref "C58") (pin "2") (pinfunction "2_2") (pintype "passive"))
      (node (ref "R42") (pin "1") (pinfunction "1_1") (pintype "passive"))
    )
    (net (code "122") (name "Net-(C76-Pad1)") (class "Default")
      (node (ref "C76") (pin "1") (pinfunction "1_1") (pintype "passive"))
      (node (ref "C78") (pin "2") (pinfunction "2_2") (pintype "passive"))
      (node (ref "L4") (pin "2") (pinfunction "2_2") (pintype "passive"))
      (node (ref "L6") (pin "1") (pinfunction "1_1") (pintype "passive"))
      (node (ref "R71") (pin "1") (pinfunction "1_1") (pintype "passive"))
    )
    (net (code "123") (name "Net-(D1-COMM)") (class "Default")
      (node (ref "D1") (pin "3") (pinfunction "COMM_3") (pintype "passive"))
      (node (ref "F1") (pin "2") (pinfunction "2_2") (pintype "passive"))
      (node (ref "R1") (pin "1") (pinfunction "1_1") (pintype "passive"))
      (node (ref "R2") (pin "2") (pinfunction "2_2") (pintype "passive"))
      (node (ref "R4") (pin "2") (pinfunction "2_2") (pintype "passive"))
      (node (ref "R5") (pin "2") (pinfunction "2_2") (pintype "passive"))
      (node (ref "R6") (pin "2") (pinfunction "2_2") (pintype "passive"))
    )
    (net (code "124") (name "Net-(D2-COMM)") (class "Default")
      (node (ref "D2") (pin "3") (pinfunction "COMM_3") (pintype "passive"))
      (node (ref "F2") (pin "2") (pinfunction "2_2") (pintype "passive"))
      (node (ref "R10") (pin "1") (pinfunction "1_1") (pintype "passive"))
      (node (ref "R11") (pin "2") (pinfunction "2_2") (pintype "passive"))
      (node (ref "R13") (pin "2") (pinfunction "2_2") (pintype "passive"))
      (node (ref "R14") (pin "2") (pinfunction "2_2") (pintype "passive"))
      (node (ref "R15") (pin "2") (pinfunction "2_2") (pintype "passive"))
    )
    (net (code "125") (name "Net-(D3-COMM)") (class "Default")
      (node (ref "D3") (pin "3") (pinfunction "COMM_3") (pintype "passive"))
      (node (ref "F3") (pin "2") (pinfunction "2_2") (pintype "passive"))
      (node (ref "R19") (pin "2") (pinfunction "2_2") (pintype "passive"))
      (node (ref "U3") (pin "3") (pinfunction "1Y_3") (pintype "input"))
      (node (ref "U3") (pin "6") (pinfunction "2Y_6") (pintype "input"))
    )
    (net (code "126") (name "Net-(D4-COMM)") (class "Default")
      (node (ref "D4") (pin "3") (pinfunction "COMM_3") (pintype "passive"))
      (node (ref "F4") (pin "2") (pinfunction "2_2") (pintype "passive"))
      (node (ref "R26") (pin "2") (pinfunction "2_2") (pintype "passive"))
      (node (ref "U3") (pin "11") (pinfunction "4Y_11") (pintype "passive"))
      (node (ref "U3") (pin "8") (pinfunction "3Y_8") (pintype "input"))
    )
    (net (code "127") (name "Net-(DI0-1)") (class "Default")
      (node (ref "DI0") (pin "CLK") (pinfunction "1_CLK") (pintype "passive"))
      (node (ref "F1") (pin "1") (pinfunction "1_1") (pintype "passive"))
    )
    (net (code "128") (name "Net-(DI1-1)") (class "Default")
      (node (ref "DI1") (pin "CLK") (pinfunction "1_CLK") (pintype "passive"))
      (node (ref "F2") (pin "1") (pinfunction "1_1") (pintype "passive"))
    )
    (net (code "129") (name "Net-(DO0-1)") (class "Default")
      (node (ref "DO0") (pin "CLK") (pinfunction "1_CLK") (pintype "passive"))
      (node (ref "F3") (pin "1") (pinfunction "1_1") (pintype "passive"))
    )
    (net (code "130") (name "Net-(DO1-1)") (class "Default")
      (node (ref "DO1") (pin "CLK") (pinfunction "1_CLK") (pintype "passive"))
      (node (ref "F4") (pin "1") (pinfunction "1_1") (pintype "passive"))
    )
    (net (code "131") (name "Net-(J1-Pad2)") (class "Default")
      (node (ref "J1") (pin "2") (pinfunction "2_2") (pintype "passive"))
      (node (ref "R3") (pin "1") (pinfunction "1_1") (pintype "passive"))
    )
    (net (code "132") (name "Net-(J2-Pad2)") (class "Default")
      (node (ref "J2") (pin "2") (pinfunction "2_2") (pintype "passive"))
      (node (ref "R12") (pin "1") (pinfunction "1_1") (pintype "passive"))
    )
    (net (code "133") (name "Net-(L5-Pad1)") (class "Default")
      (node (ref "L5") (pin "1") (pinfunction "1_1") (pintype "passive"))
      (node (ref "L6") (pin "2") (pinfunction "2_2") (pintype "passive"))
      (node (ref "R70") (pin "1") (pinfunction "1_1") (pintype "passive"))
      (node (ref "R71") (pin "2") (pinfunction "2_2") (pintype "passive"))
    )
    (net (code "134") (name "Net-(OUTA-A)") (class "Default")
      (node (ref "OUT") (pin "A1") (pinfunction "A_A1") (pintype "passive"))
      (node (ref "R20") (pin "1") (pinfunction "1_1") (pintype "passive"))
    )
    (net (code "135") (name "Net-(OUTA-C)") (class "Default")
      (node (ref "OUT") (pin "C1") (pinfunction "C_C1") (pintype "passive"))
      (node (ref "Q3") (pin "D") (pinfunction "D_D") (pintype "bidirectional"))
    )
    (net (code "136") (name "Net-(OUTB-A)") (class "Default")
      (node (ref "OUT") (pin "A2") (pinfunction "A_A2") (pintype "passive"))
      (node (ref "R28") (pin "1") (pinfunction "1_1") (pintype "passive"))
    )
    (net (code "137") (name "Net-(OUTB-C)") (class "Default")
      (node (ref "OUT") (pin "C2") (pinfunction "C_C2") (pintype "passive"))
      (node (ref "Q4") (pin "D") (pinfunction "D_D") (pintype "bidirectional"))
    )
    (net (code "138") (name "Net-(PWR/LOCKA-A)") (class "Default")
      (node (ref "PWR/LOCK") (pin "A1") (pinfunction "A_A1") (pintype "passive"))
      (node (ref "R36") (pin "1") (pinfunction "1_1") (pintype "passive"))
    )
    (net (code "139") (name "Net-(PWR/LOCKB-A)") (class "Default")
      (node (ref "PWR/LOCK") (pin "A2") (pinfunction "A_A2") (pintype "passive"))
      (node (ref "R66") (pin "1") (pinfunction "1_1") (pintype "passive"))
    )
    (net (code "140") (name "Net-(PWR/LOCKB-C)") (class "Default")
      (node (ref "PWR/LOCK") (pin "C2") (pinfunction "C_C2") (pintype "passive"))
      (node (ref "Q6") (pin "D") (pinfunction "D_D") (pintype "bidirectional"))
    )
    (net (code "141") (name "Net-(Q1-PadD)") (class "Default")
      (node (ref "Q1") (pin "D") (pinfunction "D_D") (pintype "bidirectional"))
      (node (ref "R4") (pin "1") (pinfunction "1_1") (pintype "passive"))
      (node (ref "R5") (pin "1") (pinfunction "1_1") (pintype "passive"))
      (node (ref "R6") (pin "1") (pinfunction "1_1") (pintype "passive"))
    )
    (net (code "142") (name "Net-(Q1-PadG)") (class "Default")
      (node (ref "Q1") (pin "G") (pinfunction "G_G") (pintype "bidirectional"))
      (node (ref "R7") (pin "2") (pinfunction "2_2") (pintype "passive"))
      (node (ref "R9") (pin "2") (pinfunction "2_2") (pintype "passive"))
    )
    (net (code "143") (name "Net-(Q2-PadD)") (class "Default")
      (node (ref "Q2") (pin "D") (pinfunction "D_D") (pintype "bidirectional"))
      (node (ref "R13") (pin "1") (pinfunction "1_1") (pintype "passive"))
      (node (ref "R14") (pin "1") (pinfunction "1_1") (pintype "passive"))
      (node (ref "R15") (pin "1") (pinfunction "1_1") (pintype "passive"))
    )
    (net (code "144") (name "Net-(Q2-PadG)") (class "Default")
      (node (ref "Q2") (pin "G") (pinfunction "G_G") (pintype "bidirectional"))
      (node (ref "R16") (pin "2") (pinfunction "2_2") (pintype "passive"))
      (node (ref "R18") (pin "2") (pinfunction "2_2") (pintype "passive"))
    )
    (net (code "145") (name "Net-(Q3-PadG)") (class "Default")
      (node (ref "Q3") (pin "G") (pinfunction "G_G") (pintype "bidirectional"))
      (node (ref "R19") (pin "1") (pinfunction "1_1") (pintype "passive"))
      (node (ref "R23") (pin "2") (pinfunction "2_2") (pintype "passive"))
    )
    (net (code "146") (name "Net-(Q4-PadG)") (class "Default")
      (node (ref "Q4") (pin "G") (pinfunction "G_G") (pintype "bidirectional"))
      (node (ref "R26") (pin "1") (pinfunction "1_1") (pintype "passive"))
      (node (ref "R29") (pin "2") (pinfunction "2_2") (pintype "passive"))
    )
    (net (code "147") (name "Net-(Q5-PadG)") (class "Default")
      (node (ref "Q5") (pin "G") (pinfunction "G_G") (pintype "bidirectional"))
      (node (ref "R64") (pin "1") (pinfunction "1_1") (pintype "passive"))
      (node (ref "R67") (pin "2") (pinfunction "2_2") (pintype "passive"))
    )
    (net (code "148") (name "Net-(Q6-PadG)") (class "Default")
      (node (ref "Q6") (pin "G") (pinfunction "G_G") (pintype "bidirectional"))
      (node (ref "R68") (pin "1") (pinfunction "1_1") (pintype "passive"))
      (node (ref "R69") (pin "2") (pinfunction "2_2") (pintype "passive"))
    )
    (net (code "149") (name "Net-(R81-Pad1)") (class "Default")
      (node (ref "R81") (pin "1") (pinfunction "1_1") (pintype "passive"))
      (node (ref "R82") (pin "2") (pinfunction "2_2") (pintype "passive"))
    )
    (net (code "150") (name "Net-(R82-Pad1)") (class "Default")
      (node (ref "R82") (pin "1") (pinfunction "1_1") (pintype "passive"))
      (node (ref "R83") (pin "2") (pinfunction "2_2") (pintype "passive"))
    )
    (net (code "151") (name "Net-(TERMA-A)") (class "Default")
      (node (ref "R17") (pin "2") (pinfunction "2_2") (pintype "passive"))
      (node (ref "TERM") (pin "A1") (pinfunction "A_A1") (pintype "passive"))
    )
    (net (code "152") (name "Net-(TERMB-A)") (class "Default")
      (node (ref "R8") (pin "2") (pinfunction "2_2") (pintype "passive"))
      (node (ref "TERM") (pin "A2") (pinfunction "A_A2") (pintype "passive"))
    )
    (net (code "153") (name "Net-(U1A-+IN)") (class "Default")
      (node (ref "R1") (pin "2") (pinfunction "2_2") (pintype "passive"))
      (node (ref "U1") (pin "3") (pinfunction "+IN_3") (pintype "input"))
    )
    (net (code "154") (name "Net-(U1A--IN)") (class "Default")
      (node (ref "C2") (pin "1") (pinfunction "1_1") (pintype "passive"))
      (node (ref "R3") (pin "2") (pinfunction "2_2") (pintype "passive"))
      (node (ref "U1") (pin "4") (pinfunction "-IN_4") (pintype "input"))
    )
    (net (code "155") (name "Net-(U2A-+IN)") (class "Default")
      (node (ref "R10") (pin "2") (pinfunction "2_2") (pintype "passive"))
      (node (ref "U2") (pin "3") (pinfunction "+IN_3") (pintype "input"))
    )
    (net (code "156") (name "Net-(U2A--IN)") (class "Default")
      (node (ref "C4") (pin "1") (pinfunction "1_1") (pintype "passive"))
      (node (ref "R12") (pin "2") (pinfunction "2_2") (pintype "passive"))
      (node (ref "U2") (pin "4") (pinfunction "-IN_4") (pintype "input"))
    )
    (net (code "157") (name "Net-(U3-~{1G})") (class "Default")
      (node (ref "R21") (pin "1") (pinfunction "1_1") (pintype "passive"))
      (node (ref "U3") (pin "1") (pinfunction "~{1G}_1") (pintype "input"))
      (node (ref "U3") (pin "4") (pinfunction "~{2G}_4") (pintype "input"))
    )
    (net (code "158") (name "Net-(U3-~{3G})") (class "Default")
      (node (ref "R22") (pin "1") (pinfunction "1_1") (pintype "passive"))
      (node (ref "U3") (pin "10") (pinfunction "~{3G}_10") (pintype "input"))
      (node (ref "U3") (pin "13") (pinfunction "~{4G}_13") (pintype "input"))
    )
    (net (code "159") (name "Net-(U6-EN)") (class "Default")
      (node (ref "L7/0R") (pin "2") (pinfunction "2_2") (pintype "passive"))
      (node (ref "U6") (pin "1") (pinfunction "VIN_1") (pintype "power_in"))
      (node (ref "U6") (pin "6") (pinfunction "EN_6") (pintype "input"))
    )
    (net (code "160") (name "Net-(U6-TRIM)") (class "Default")
      (node (ref "R35") (pin "1") (pinfunction "1_1") (pintype "passive"))
      (node (ref "U6") (pin "4") (pinfunction "TRIM_4") (pintype "passive"))
    )
    (net (code "161") (name "Net-(U7-FB1)") (class "Default")
      (node (ref "R37") (pin "1") (pinfunction "1_1") (pintype "passive"))
      (node (ref "U7") (pin "E4") (pinfunction "FB1_E4") (pintype "input"))
    )
    (net (code "162") (name "Net-(U7-FB2)") (class "Default")
      (node (ref "R39") (pin "1") (pinfunction "1_1") (pintype "passive"))
      (node (ref "U7") (pin "A4") (pinfunction "FB2_A4") (pintype "input"))
    )
    (net (code "163") (name "Net-(U7-FREQ)") (class "Default")
      (node (ref "R38") (pin "1") (pinfunction "1_1") (pintype "passive"))
      (node (ref "U7") (pin "C4") (pinfunction "FREQ_C4") (pintype "input"))
    )
    (net (code "164") (name "Net-(U7-TRACK{slash}SS1)") (class "Default")
      (node (ref "C30") (pin "2") (pinfunction "2_2") (pintype "passive"))
      (node (ref "U7") (pin "E3") (pinfunction "TRACK/SS1_E3") (pintype "input"))
    )
    (net (code "165") (name "Net-(U7-TRACK{slash}SS2)") (class "Default")
      (node (ref "C29") (pin "2") (pinfunction "2_2") (pintype "passive"))
      (node (ref "U7") (pin "A3") (pinfunction "TRACK/SS2_A3") (pintype "input"))
    )
    (net (code "166") (name "Net-(U12-GPIO0)") (class "Default")
      (node (ref "R60") (pin "2") (pinfunction "2_2") (pintype "passive"))
      (node (ref "U12") (pin "28") (pinfunction "GPIO0_28") (pintype "bidirectional"))
    )
    (net (code "167") (name "Net-(U12-GPIO1)") (class "Default")
      (node (ref "R59") (pin "2") (pinfunction "2_2") (pintype "passive"))
      (node (ref "U12") (pin "27") (pinfunction "GPIO1_27") (pintype "bidirectional"))
    )
    (net (code "168") (name "Net-(U12-GPIO2)") (class "Default")
      (node (ref "R58") (pin "2") (pinfunction "2_2") (pintype "passive"))
      (node (ref "U12") (pin "26") (pinfunction "GPIO2_26") (pintype "bidirectional"))
    )
    (net (code "169") (name "Net-(U12-GPIO3)") (class "Default")
      (node (ref "R57") (pin "2") (pinfunction "2_2") (pintype "passive"))
      (node (ref "U12") (pin "25") (pinfunction "GPIO3_25") (pintype "bidirectional"))
    )
    (net (code "170") (name "Net-(U12-HSYNC)") (class "Default")
      (node (ref "R43") (pin "2") (pinfunction "2_2") (pintype "passive"))
      (node (ref "U12") (pin "10") (pinfunction "HSYNC_10") (pintype "output"))
    )
    (net (code "171") (name "Net-(U12-PCLK)") (class "Default")
      (node (ref "R40") (pin "2") (pinfunction "2_2") (pintype "passive"))
      (node (ref "U12") (pin "8") (pinfunction "PCLK_8") (pintype "output"))
    )
    (net (code "172") (name "Net-(U12-RIN0+)") (class "Default")
      (node (ref "C57") (pin "1") (pinfunction "1_1") (pintype "passive"))
      (node (ref "U12") (pin "41") (pinfunction "RIN0+_41") (pintype "input"))
    )
    (net (code "173") (name "Net-(U12-RIN0-)") (class "Default")
      (node (ref "C58") (pin "1") (pinfunction "1_1") (pintype "passive"))
      (node (ref "U12") (pin "42") (pinfunction "RIN0-_42") (pintype "input"))
    )
    (net (code "174") (name "Net-(U12-ROUT0)") (class "Default")
      (node (ref "R55") (pin "2") (pinfunction "2_2") (pintype "passive"))
      (node (ref "U12") (pin "24") (pinfunction "ROUT0_24") (pintype "output"))
    )
    (net (code "175") (name "Net-(U12-ROUT1)") (class "Default")
      (node (ref "R54") (pin "2") (pinfunction "2_2") (pintype "passive"))
      (node (ref "U12") (pin "23") (pinfunction "ROUT1_23") (pintype "output"))
    )
    (net (code "176") (name "Net-(U12-ROUT2)") (class "Default")
      (node (ref "R53") (pin "2") (pinfunction "2_2") (pintype "passive"))
      (node (ref "U12") (pin "22") (pinfunction "ROUT2_22") (pintype "output"))
    )
    (net (code "177") (name "Net-(U12-ROUT3)") (class "Default")
      (node (ref "R52") (pin "2") (pinfunction "2_2") (pintype "passive"))
      (node (ref "U12") (pin "21") (pinfunction "ROUT3_21") (pintype "output"))
    )
    (net (code "178") (name "Net-(U12-ROUT4)") (class "Default")
      (node (ref "R51") (pin "2") (pinfunction "2_2") (pintype "passive"))
      (node (ref "U12") (pin "19") (pinfunction "ROUT4_19") (pintype "output"))
    )
    (net (code "179") (name "Net-(U12-ROUT5)") (class "Default")
      (node (ref "R50") (pin "2") (pinfunction "2_2") (pintype "passive"))
      (node (ref "U12") (pin "18") (pinfunction "ROUT5_18") (pintype "output"))
    )
    (net (code "180") (name "Net-(U12-ROUT6)") (class "Default")
      (node (ref "R49") (pin "2") (pinfunction "2_2") (pintype "passive"))
      (node (ref "U12") (pin "16") (pinfunction "ROUT6_16") (pintype "output"))
    )
    (net (code "181") (name "Net-(U12-ROUT7)") (class "Default")
      (node (ref "R48") (pin "2") (pinfunction "2_2") (pintype "passive"))
      (node (ref "U12") (pin "15") (pinfunction "ROUT7_15") (pintype "output"))
    )
    (net (code "182") (name "Net-(U12-ROUT8)") (class "Default")
      (node (ref "R47") (pin "2") (pinfunction "2_2") (pintype "passive"))
      (node (ref "U12") (pin "14") (pinfunction "ROUT8_14") (pintype "output"))
    )
    (net (code "183") (name "Net-(U12-ROUT9)") (class "Default")
      (node (ref "R46") (pin "2") (pinfunction "2_2") (pintype "passive"))
      (node (ref "U12") (pin "13") (pinfunction "ROUT9_13") (pintype "output"))
    )
    (net (code "184") (name "Net-(U12-ROUT10)") (class "Default")
      (node (ref "R45") (pin "2") (pinfunction "2_2") (pintype "passive"))
      (node (ref "U12") (pin "12") (pinfunction "ROUT10_12") (pintype "output"))
    )
    (net (code "185") (name "Net-(U12-ROUT11)") (class "Default")
      (node (ref "R44") (pin "2") (pinfunction "2_2") (pintype "passive"))
      (node (ref "U12") (pin "11") (pinfunction "ROUT11_11") (pintype "output"))
    )
    (net (code "186") (name "Net-(U12-VDDCML0)") (class "Default")
      (node (ref "C52") (pin "2") (pinfunction "2_2") (pintype "passive"))
      (node (ref "C53") (pin "2") (pinfunction "2_2") (pintype "passive"))
      (node (ref "C54") (pin "2") (pinfunction "2_2") (pintype "passive"))
      (node (ref "L3") (pin "1") (pinfunction "1_1") (pintype "passive"))
      (node (ref "U12") (pin "40") (pinfunction "VDDCML0_40") (pintype "power_in"))
    )
    (net (code "187") (name "Net-(U12-VDDCML1)") (class "Default")
      (node (ref "C36") (pin "2") (pinfunction "2_2") (pintype "passive"))
      (node (ref "C37") (pin "2") (pinfunction "2_2") (pintype "passive"))
      (node (ref "C38") (pin "2") (pinfunction "2_2") (pintype "passive"))
      (node (ref "L1") (pin "1") (pinfunction "1_1") (pintype "passive"))
      (node (ref "U12") (pin "31") (pinfunction "VDDCML1_31") (pintype "power_in"))
    )
    (net (code "188") (name "Net-(U12-VDDPLL)") (class "Default")
      (node (ref "C39") (pin "2") (pinfunction "2_2") (pintype "passive"))
      (node (ref "C40") (pin "2") (pinfunction "2_2") (pintype "passive"))
      (node (ref "C41") (pin "2") (pinfunction "2_2") (pintype "passive"))
      (node (ref "L2") (pin "2") (pinfunction "2_2") (pintype "passive"))
      (node (ref "U12") (pin "45") (pinfunction "VDDPLL_45") (pintype "power_in"))
    )
    (net (code "189") (name "Net-(U12-VSYNC)") (class "Default")
      (node (ref "R41") (pin "2") (pinfunction "2_2") (pintype "passive"))
      (node (ref "U12") (pin "9") (pinfunction "VSYNC_9") (pintype "output"))
    )
    (net (code "190") (name "Net-(U18-VIC)") (class "Default")
      (node (ref "R78") (pin "1") (pinfunction "1_1") (pintype "passive"))
      (node (ref "U18") (pin "P5") (pinfunction "VIC_P5") (pintype "input"))
    )
    (net (code "191") (name "Net-(U18-VOD)") (class "Default")
      (node (ref "R79") (pin "2") (pinfunction "2_2") (pintype "passive"))
      (node (ref "R80") (pin "1") (pinfunction "1_1") (pintype "passive"))
      (node (ref "U18") (pin "P6") (pinfunction "VOD_P6") (pintype "output"))
    )
    (net (code "192") (name "PASS") (class "Default")
      (node (ref "U16") (pin "7") (pinfunction "4A_7") (pintype "input"))
      (node (ref "U18") (pin "P12") (pinfunction "VOC_P12") (pintype "output"))
    )
    (net (code "193") (name "PASS_ISO") (class "Default")
      (node (ref "R78") (pin "2") (pinfunction "2_2") (pintype "passive"))
      (node (ref "U12") (pin "47") (pinfunction "PASS_47") (pintype "input"))
    )
    (net (code "194") (name "PCLK_ISO") (class "Default")
      (node (ref "R40") (pin "1") (pinfunction "1_1") (pintype "passive"))
      (node (ref "U14") (pin "P5") (pinfunction "VIC_P5") (pintype "input"))
    )
    (net (code "195") (name "PCLK_N") (class "Default")
      (node (ref "FMC_LPC") (pin "P$43") (pinfunction "CLK1_M2C_N_P$43") (pintype "bidirectional"))
      (node (ref "U11") (pin "35") (pinfunction "D3Z_35") (pintype "output"))
    )
    (net (code "196") (name "PCLK_P") (class "Default")
      (node (ref "FMC_LPC") (pin "P$42") (pinfunction "CLK1_M2C_P_P$42") (pintype "bidirectional"))
      (node (ref "U11") (pin "36") (pinfunction "D3Y_36") (pintype "output"))
    )
    (net (code "197") (name "PDN_ISO") (class "Default")
      (node (ref "C61") (pin "2") (pinfunction "2_2") (pintype "passive"))
      (node (ref "Q5") (pin "D") (pinfunction "D_D") (pintype "bidirectional"))
      (node (ref "R56") (pin "2") (pinfunction "2_2") (pintype "passive"))
      (node (ref "R64") (pin "2") (pinfunction "2_2") (pintype "passive"))
      (node (ref "R80") (pin "2") (pinfunction "2_2") (pintype "passive"))
      (node (ref "S1") (pin "B") (pinfunction "S_B") (pintype "passive"))
      (node (ref "U12") (pin "30") (pinfunction "PDN_30") (pintype "input"))
    )
    (net (code "198") (name "SCL") (class "Default")
      (node (ref "FMC_LPC") (pin "P$150") (pinfunction "SCL_P$150") (pintype "bidirectional"))
      (node (ref "R33") (pin "1") (pinfunction "1_1") (pintype "passive"))
      (node (ref "TP20") (pin "1") (pinfunction "TP_1") (pintype "bidirectional"))
      (node (ref "U4") (pin "7") (pinfunction "SCL_7") (pintype "input"))
      (node (ref "U5") (pin "3") (pinfunction "SCL1_3") (pintype "input"))
    )
    (net (code "199") (name "SCL_ISO") (class "Default")
      (node (ref "R30") (pin "1") (pinfunction "1_1") (pintype "passive"))
      (node (ref "TP15") (pin "1") (pinfunction "TP_1") (pintype "bidirectional"))
      (node (ref "U12") (pin "2") (pinfunction "SCL_2") (pintype "input"))
      (node (ref "U5") (pin "6") (pinfunction "SCL2_6") (pintype "output"))
    )
    (net (code "200") (name "SDA") (class "Default")
      (node (ref "FMC_LPC") (pin "P$151") (pinfunction "SDA_P$151") (pintype "bidirectional"))
      (node (ref "R32") (pin "1") (pinfunction "1_1") (pintype "passive"))
      (node (ref "TP19") (pin "1") (pinfunction "TP_1") (pintype "bidirectional"))
      (node (ref "U4") (pin "8") (pinfunction "SDA_8") (pintype "input"))
      (node (ref "U5") (pin "2") (pinfunction "SDA1_2") (pintype "input"))
    )
    (net (code "201") (name "SDA_ISO") (class "Default")
      (node (ref "R31") (pin "1") (pinfunction "1_1") (pintype "passive"))
      (node (ref "TP16") (pin "1") (pinfunction "TP_1") (pintype "bidirectional"))
      (node (ref "U12") (pin "1") (pinfunction "SDA_1") (pintype "bidirectional"))
      (node (ref "U5") (pin "7") (pinfunction "SDA2_7") (pintype "output"))
    )
    (net (code "202") (name "SMA_IN") (class "Default")
      (node (ref "FMC_LPC") (pin "P$146") (pinfunction "LA27_P_P$146") (pintype "bidirectional"))
      (node (ref "J6") (pin "SIG") (pinfunction "1_SIG") (pintype "passive"))
      (node (ref "U18") (pin "P13") (pinfunction "VOB_P13") (pintype "output"))
    )
    (net (code "203") (name "SMA_OUT") (class "Default")
      (node (ref "FMC_LPC") (pin "P$147") (pinfunction "LA27_N_P$147") (pintype "bidirectional"))
      (node (ref "J8") (pin "SIG") (pinfunction "1_SIG") (pintype "passive"))
      (node (ref "U18") (pin "P11") (pinfunction "VID_P11") (pintype "input"))
    )
    (net (code "204") (name "TDI-TDO") (class "Default")
      (node (ref "FMC_LPC") (pin "P$110") (pinfunction "TDI_P$110") (pintype "bidirectional"))
      (node (ref "FMC_LPC") (pin "P$111") (pinfunction "TDO_P$111") (pintype "bidirectional"))
    )
    (net (code "205") (name "VSYNC_ISO") (class "Default")
      (node (ref "R41") (pin "1") (pinfunction "1_1") (pintype "passive"))
      (node (ref "U14") (pin "P4") (pinfunction "VIB_P4") (pintype "input"))
    )
    (net (code "206") (name "VSYNC_N") (class "Default")
      (node (ref "FMC_LPC") (pin "P$5") (pinfunction "CLK0_M2C_N_P$5") (pintype "bidirectional"))
      (node (ref "U11") (pin "37") (pinfunction "D2Z_37") (pintype "output"))
    )
    (net (code "207") (name "VSYNC_P") (class "Default")
      (node (ref "FMC_LPC") (pin "P$4") (pinfunction "CLK0_M2C_P_P$4") (pintype "bidirectional"))
      (node (ref "U11") (pin "38") (pinfunction "D2Y_38") (pintype "output"))
    )
    (net (code "208") (name "V_PROTECT") (class "Default")
      (node (ref "C16") (pin "2") (pinfunction "2_2") (pintype "passive"))
      (node (ref "D1") (pin "2") (pinfunction "C_2") (pintype "passive"))
      (node (ref "D2") (pin "2") (pinfunction "C_2") (pintype "passive"))
      (node (ref "D3") (pin "2") (pinfunction "C_2") (pintype "passive"))
      (node (ref "D4") (pin "2") (pinfunction "C_2") (pintype "passive"))
      (node (ref "D6") (pin "C") (pinfunction "C_C") (pintype "passive"))
      (node (ref "R24") (pin "1") (pinfunction "1_1") (pintype "passive"))
      (node (ref "R25") (pin "1") (pinfunction "1_1") (pintype "passive"))
      (node (ref "TP14") (pin "1") (pinfunction "TP_1") (pintype "bidirectional"))
    )
    (net (code "209") (name "unconnected-(FMC_LPCA-3P3VAUX-PadP$112)") (class "Default")
      (node (ref "FMC_LPC") (pin "P$112") (pinfunction "3P3VAUX_P$112") (pintype "bidirectional"))
    )
    (net (code "210") (name "unconnected-(FMC_LPCA-DP0_C2M_N-PadP$123)") (class "Default")
      (node (ref "FMC_LPC") (pin "P$123") (pinfunction "DP0_C2M_N_P$123") (pintype "bidirectional"))
    )
    (net (code "211") (name "unconnected-(FMC_LPCA-DP0_C2M_P-PadP$122)") (class "Default")
      (node (ref "FMC_LPC") (pin "P$122") (pinfunction "DP0_C2M_P_P$122") (pintype "bidirectional"))
    )
    (net (code "212") (name "unconnected-(FMC_LPCA-DP0_M2C_N-PadP$127)") (class "Default")
      (node (ref "FMC_LPC") (pin "P$127") (pinfunction "DP0_M2C_N_P$127") (pintype "bidirectional"))
    )
    (net (code "213") (name "unconnected-(FMC_LPCA-DP0_M2C_P-PadP$126)") (class "Default")
      (node (ref "FMC_LPC") (pin "P$126") (pinfunction "DP0_M2C_P_P$126") (pintype "bidirectional"))
    )
    (net (code "214") (name "unconnected-(FMC_LPCA-GA0-PadP$154)") (class "Default")
      (node (ref "FMC_LPC") (pin "P$154") (pinfunction "GA0_P$154") (pintype "bidirectional"))
    )
    (net (code "215") (name "unconnected-(FMC_LPCA-GA1-PadP$115)") (class "Default")
      (node (ref "FMC_LPC") (pin "P$115") (pinfunction "GA1_P$115") (pintype "bidirectional"))
    )
    (net (code "216") (name "unconnected-(FMC_LPCA-GBTCLK0_M2C_N-PadP$85)") (class "Default")
      (node (ref "FMC_LPC") (pin "P$85") (pinfunction "GBTCLK0_M2C_N_P$85") (pintype "bidirectional"))
    )
    (net (code "217") (name "unconnected-(FMC_LPCA-GBTCLK0_M2C_P-PadP$84)") (class "Default")
      (node (ref "FMC_LPC") (pin "P$84") (pinfunction "GBTCLK0_M2C_P_P$84") (pintype "bidirectional"))
    )
    (net (code "218") (name "unconnected-(FMC_LPCA-LA00_N_CC-PadP$47)") (class "Default")
      (node (ref "FMC_LPC") (pin "P$47") (pinfunction "LA00_N_CC_P$47") (pintype "bidirectional"))
    )
    (net (code "219") (name "unconnected-(FMC_LPCA-LA00_P_CC-PadP$46)") (class "Default")
      (node (ref "FMC_LPC") (pin "P$46") (pinfunction "LA00_P_CC_P$46") (pintype "bidirectional"))
    )
    (net (code "220") (name "unconnected-(FMC_LPCA-LA28_N-PadP$32)") (class "Default")
      (node (ref "FMC_LPC") (pin "P$32") (pinfunction "LA28_N_P$32") (pintype "bidirectional"))
    )
    (net (code "221") (name "unconnected-(FMC_LPCA-LA28_P-PadP$31)") (class "Default")
      (node (ref "FMC_LPC") (pin "P$31") (pinfunction "LA28_P_P$31") (pintype "bidirectional"))
    )
    (net (code "222") (name "unconnected-(FMC_LPCA-LA29_N-PadP$71)") (class "Default")
      (node (ref "FMC_LPC") (pin "P$71") (pinfunction "LA29_N_P$71") (pintype "bidirectional"))
    )
    (net (code "223") (name "unconnected-(FMC_LPCA-LA29_P-PadP$70)") (class "Default")
      (node (ref "FMC_LPC") (pin "P$70") (pinfunction "LA29_P_P$70") (pintype "bidirectional"))
    )
    (net (code "224") (name "unconnected-(FMC_LPCA-LA30_N-PadP$35)") (class "Default")
      (node (ref "FMC_LPC") (pin "P$35") (pinfunction "LA30_N_P$35") (pintype "bidirectional"))
    )
    (net (code "225") (name "unconnected-(FMC_LPCA-LA30_P-PadP$34)") (class "Default")
      (node (ref "FMC_LPC") (pin "P$34") (pinfunction "LA30_P_P$34") (pintype "bidirectional"))
    )
    (net (code "226") (name "unconnected-(FMC_LPCA-LA31_N-PadP$74)") (class "Default")
      (node (ref "FMC_LPC") (pin "P$74") (pinfunction "LA31_N_P$74") (pintype "bidirectional"))
    )
    (net (code "227") (name "unconnected-(FMC_LPCA-LA31_P-PadP$73)") (class "Default")
      (node (ref "FMC_LPC") (pin "P$73") (pinfunction "LA31_P_P$73") (pintype "bidirectional"))
    )
    (net (code "228") (name "unconnected-(FMC_LPCA-LA32_N-PadP$38)") (class "Default")
      (node (ref "FMC_LPC") (pin "P$38") (pinfunction "LA32_N_P$38") (pintype "bidirectional"))
    )
    (net (code "229") (name "unconnected-(FMC_LPCA-LA32_P-PadP$37)") (class "Default")
      (node (ref "FMC_LPC") (pin "P$37") (pinfunction "LA32_P_P$37") (pintype "bidirectional"))
    )
    (net (code "230") (name "unconnected-(FMC_LPCA-LA33_N-PadP$77)") (class "Default")
      (node (ref "FMC_LPC") (pin "P$77") (pinfunction "LA33_N_P$77") (pintype "bidirectional"))
    )
    (net (code "231") (name "unconnected-(FMC_LPCA-LA33_P-PadP$76)") (class "Default")
      (node (ref "FMC_LPC") (pin "P$76") (pinfunction "LA33_P_P$76") (pintype "bidirectional"))
    )
    (net (code "232") (name "unconnected-(FMC_LPCA-PG_C2M-PadP$81)") (class "Default")
      (node (ref "FMC_LPC") (pin "P$81") (pinfunction "PG_C2M_P$81") (pintype "bidirectional"))
    )
    (net (code "233") (name "unconnected-(FMC_LPCA-PRSNT_M2C_L-PadP$2)") (class "Default")
      (node (ref "FMC_LPC") (pin "P$2") (pinfunction "PRSNT_M2C_L_P$2") (pintype "bidirectional"))
    )
    (net (code "234") (name "unconnected-(FMC_LPCA-TCK-PadP$109)") (class "Default")
      (node (ref "FMC_LPC") (pin "P$109") (pinfunction "TCK_P$109") (pintype "bidirectional"))
    )
    (net (code "235") (name "unconnected-(FMC_LPCA-TMS-PadP$113)") (class "Default")
      (node (ref "FMC_LPC") (pin "P$113") (pinfunction "TMS_P$113") (pintype "bidirectional"))
    )
    (net (code "236") (name "unconnected-(FMC_LPCA-TRST_L-PadP$114)") (class "Default")
      (node (ref "FMC_LPC") (pin "P$114") (pinfunction "TRST_L_P$114") (pintype "bidirectional"))
    )
    (net (code "237") (name "unconnected-(FMC_LPCA-VADJ1-PadP$79)") (class "Default")
      (node (ref "FMC_LPC") (pin "P$79") (pinfunction "VADJ1_P$79") (pintype "bidirectional"))
    )
    (net (code "238") (name "unconnected-(FMC_LPCA-VADJ2-PadP$40)") (class "Default")
      (node (ref "FMC_LPC") (pin "P$40") (pinfunction "VADJ2_P$40") (pintype "bidirectional"))
    )
    (net (code "239") (name "unconnected-(FMC_LPCA-VREF_A_M2C-PadP$1)") (class "Default")
      (node (ref "FMC_LPC") (pin "P$1") (pinfunction "VREF_A_M2C_P$1") (pintype "bidirectional"))
    )
    (net (code "240") (name "unconnected-(U7-COMP1-PadE5)") (class "Default")
      (node (ref "U7") (pin "E5") (pinfunction "COMP1_E5") (pintype "bidirectional"))
    )
    (net (code "241") (name "unconnected-(U7-COMP2-PadA5)") (class "Default")
      (node (ref "U7") (pin "A5") (pinfunction "COMP2_A5") (pintype "bidirectional"))
    )
    (net (code "242") (name "unconnected-(U7-PGOOD2-PadB4)") (class "Default")
      (node (ref "U7") (pin "B4") (pinfunction "PGOOD2_B4") (pintype "open_collector"))
    )
    (net (code "243") (name "unconnected-(U12-RIN1+-Pad32)") (class "Default")
      (node (ref "U12") (pin "32") (pinfunction "RIN1+_32") (pintype "input"))
    )
    (net (code "244") (name "unconnected-(U12-RIN1--Pad33)") (class "Default")
      (node (ref "U12") (pin "33") (pinfunction "RIN1-_33") (pintype "input"))
    )
    (net (code "245") (name "unconnected-(U12-TEST+-Pad38)") (class "Default")
      (node (ref "U12") (pin "38") (pinfunction "TEST+_38") (pintype "output"))
    )
    (net (code "246") (name "unconnected-(U12-TEST--Pad39)") (class "Default")
      (node (ref "U12") (pin "39") (pinfunction "TEST-_39") (pintype "output"))
    )
  )
)
